# Controller_Mainboard.net
KiCad netlist of a schematic drawn in Altium Designer
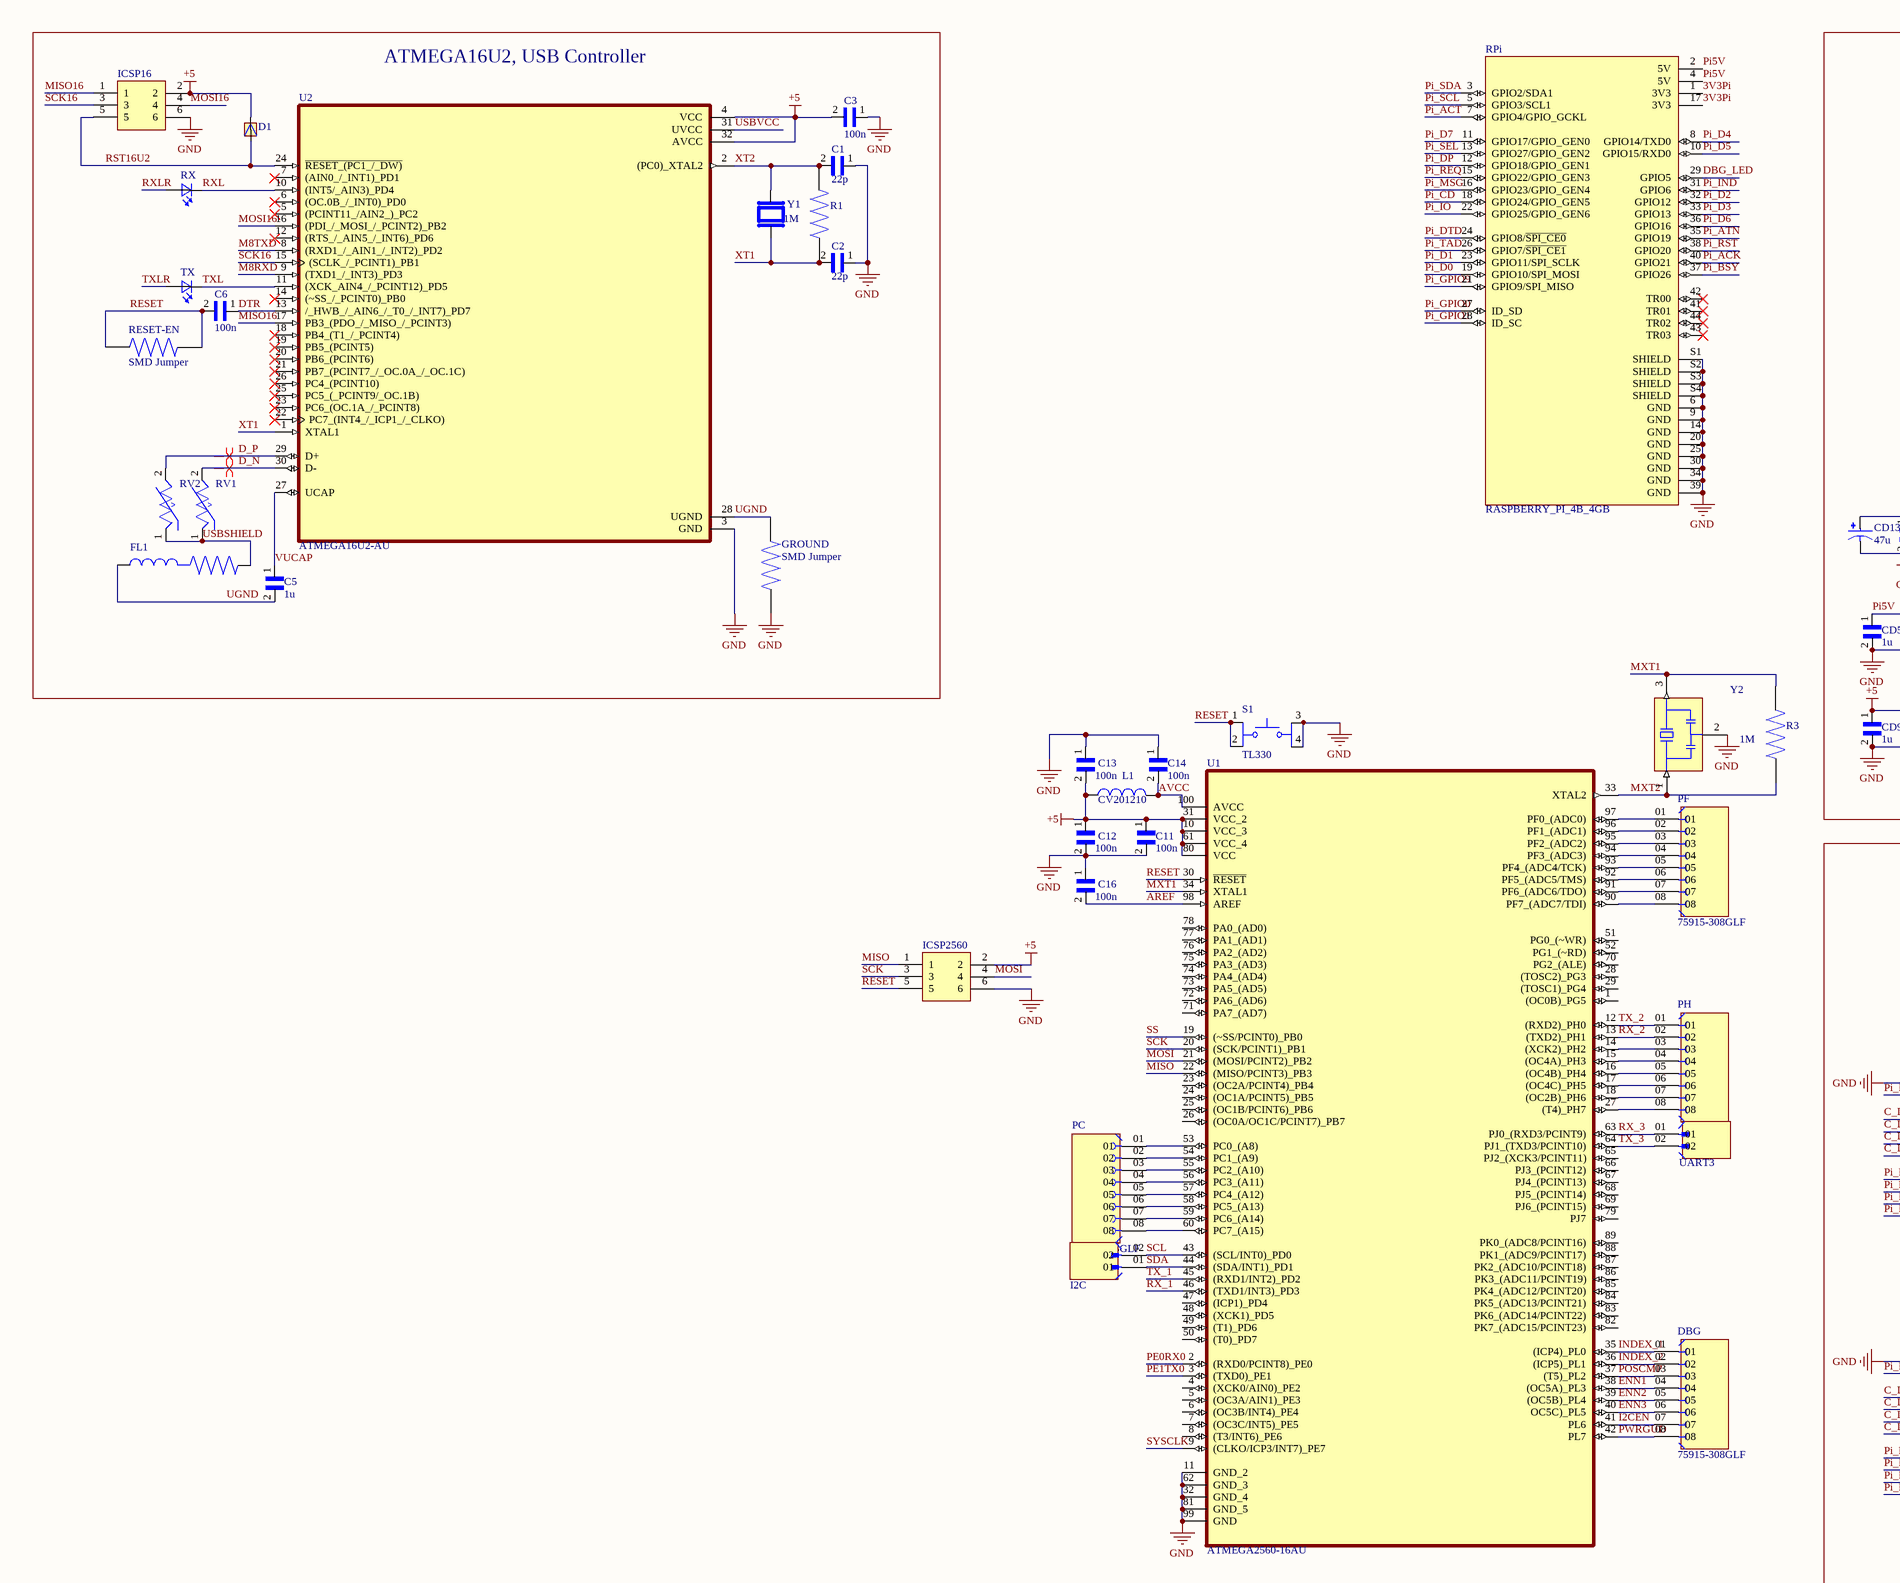
[diagram p0: Controller Mainboard.SchDoc, top left]
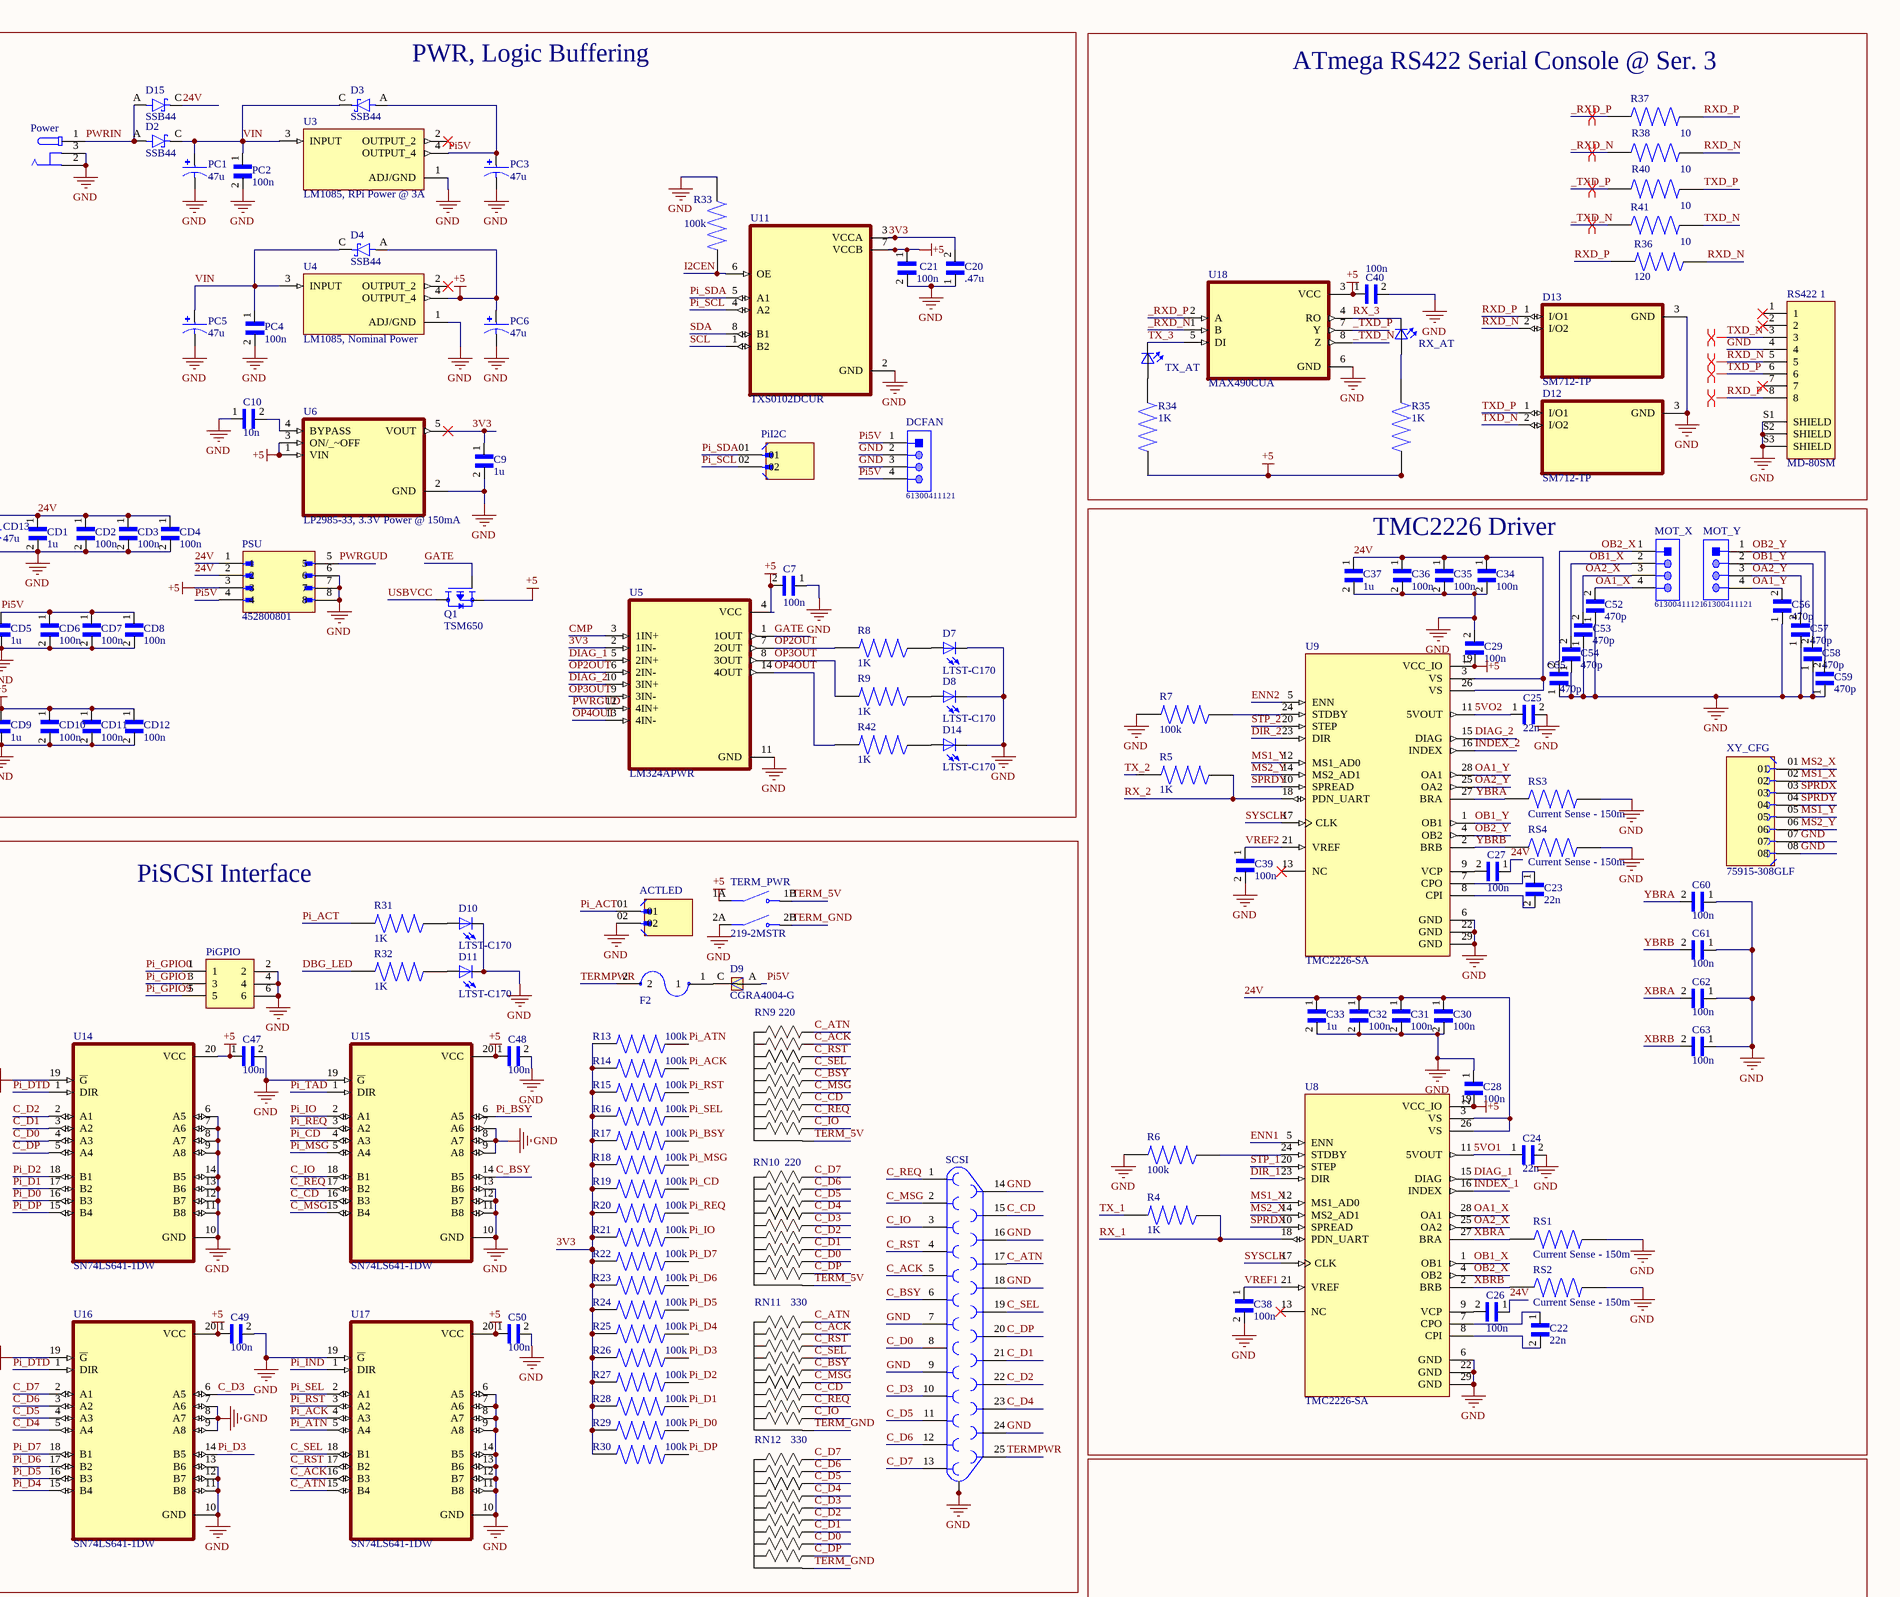
[diagram p1: Controller Mainboard.SchDoc, top right]
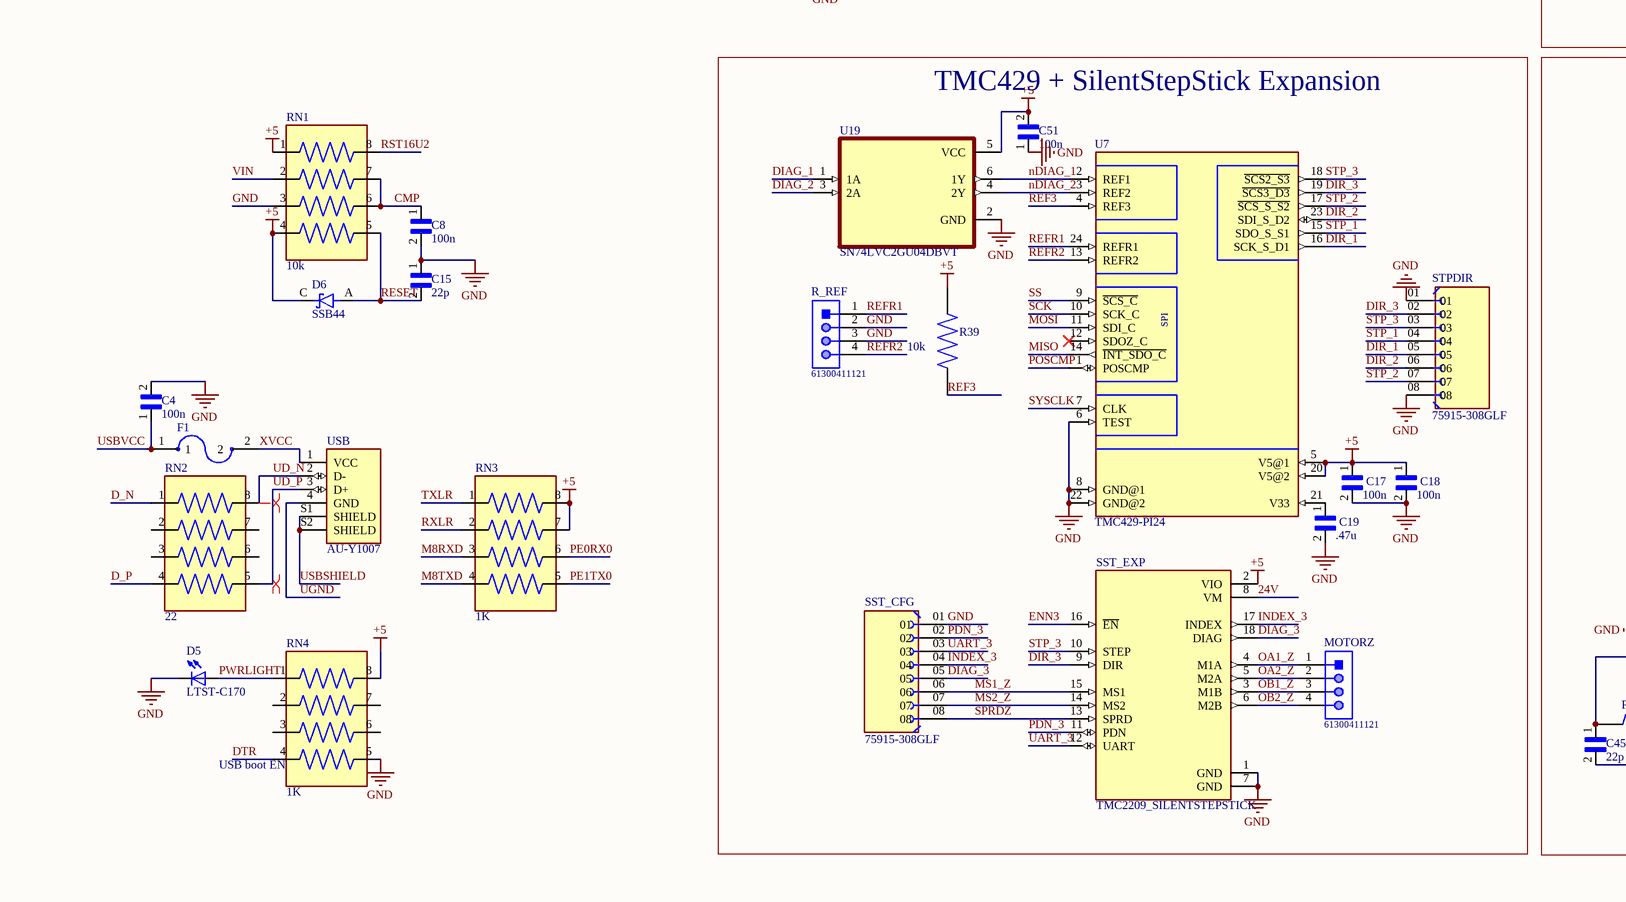
[diagram p2: Controller Mainboard.SchDoc, bottom left]
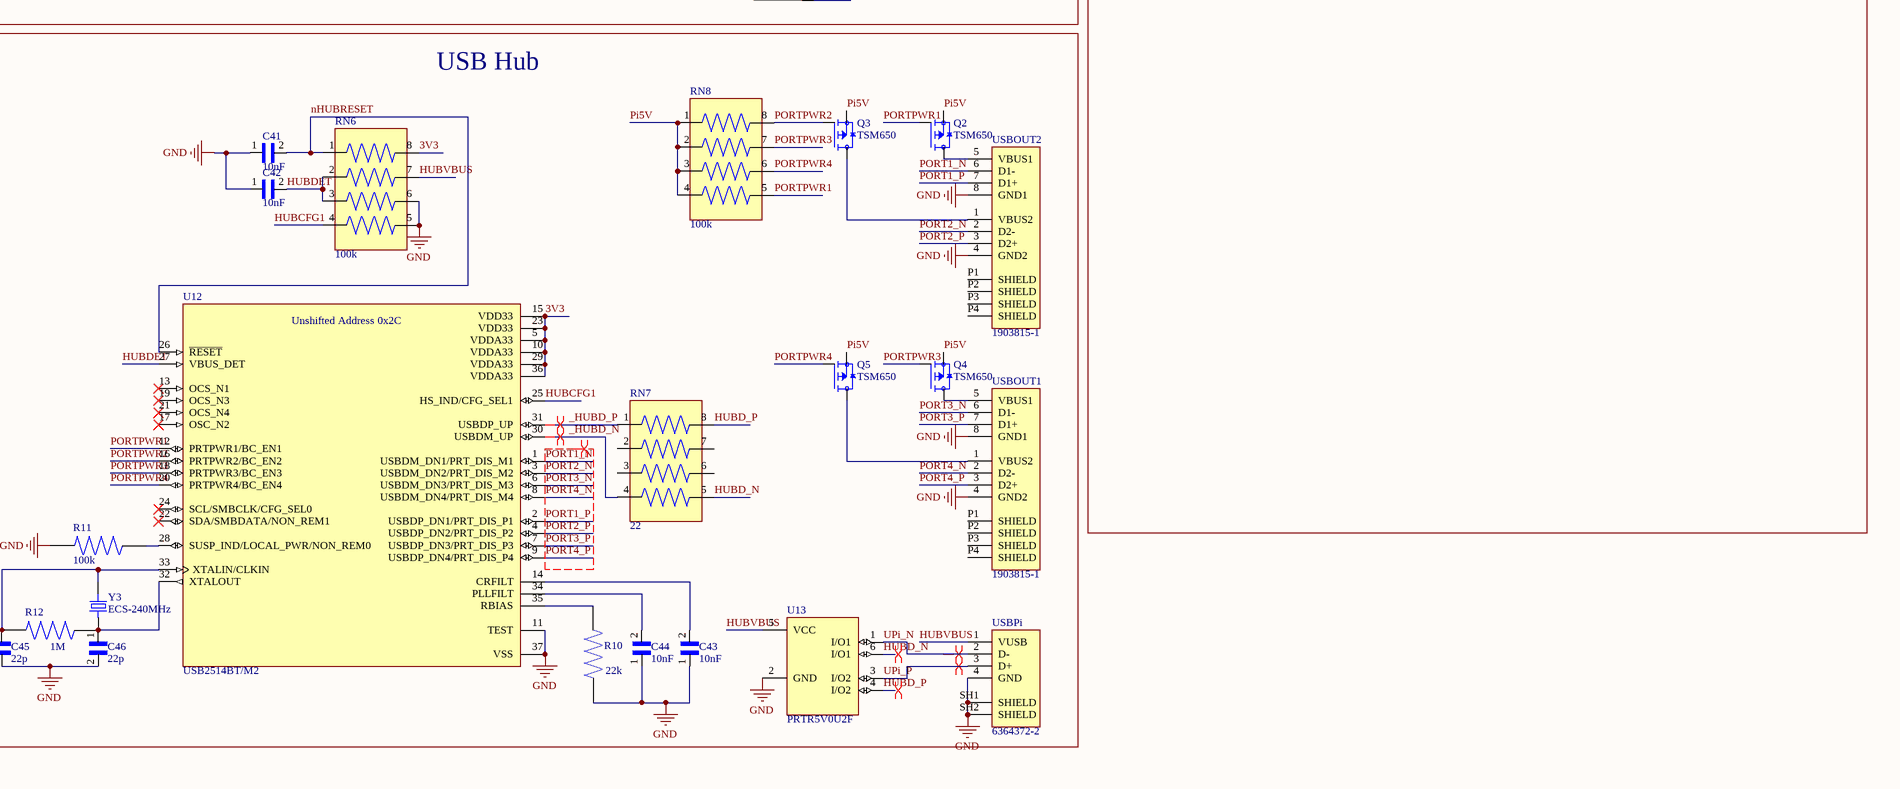
[diagram p3: Controller Mainboard.SchDoc, bottom right]

(export (version "E")
  (design (tool "Eeschema 10.0.6"))
  (components
    (comp (ref "ACTLED")
      (value "77311-118-02LF")
      (footprint "AMPHENOL_77311-118-02LF")
      (fields (field (name "MF") "{'manufacturer': u'Amphenol ICC'}"))
      (libsource (lib "Stepper_Controller") (part "77311-118-02LF"))
    )
    (comp (ref "C1")
      (value "22p")
      (footprint "CAPC1608X90")
      (description "Cap Ceramic 0.0022uF 4V X7R 10% SMD 0603 125Â°C T/R")
      (fields (field (name "MP") "LD034C222KAB2A") (field (name "MF") "{'manufacturer': u'AVX'}"))
      (libsource (lib "") (part "LD034C222KAB2A_3"))
    )
    (comp (ref "C2")
      (value "22p")
      (footprint "CAPC1608X90")
      (description "Cap Ceramic 0.0022uF 4V X7R 10% SMD 0603 125Â°C T/R")
      (fields (field (name "MP") "LD034C222KAB2A") (field (name "MF") "{'manufacturer': u'AVX'}"))
      (libsource (lib "") (part "LD034C222KAB2A_3"))
    )
    (comp (ref "C3")
      (value "100n")
      (footprint "CAPC1608X90")
      (description "Cap Ceramic 0.0022uF 4V X7R 10% SMD 0603 125Â°C T/R")
      (fields (field (name "MP") "LD034C222KAB2A") (field (name "MF") "{'manufacturer': u'AVX'}"))
      (libsource (lib "") (part "LD034C222KAB2A_3"))
    )
    (comp (ref "C4")
      (value "100n")
      (footprint "CAPC1608X90")
      (description "Cap Ceramic 0.0022uF 4V X7R 10% SMD 0603 125Â°C T/R")
      (fields (field (name "MP") "LD034C222KAB2A") (field (name "MF") "{'manufacturer': u'AVX'}"))
      (libsource (lib "") (part "LD034C222KAB2A_2"))
    )
    (comp (ref "C5")
      (value "1u")
      (footprint "CAPC1608X90")
      (description "Cap Ceramic 0.0022uF 4V X7R 10% SMD 0603 125Â°C T/R")
      (fields (field (name "MP") "LD034C222KAB2A") (field (name "MF") "{'manufacturer': u'AVX'}"))
      (libsource (lib "Stepper_Controller") (part "LD034C222KAB2A"))
    )
    (comp (ref "C6")
      (value "100n")
      (footprint "CAPC1608X90")
      (description "Cap Ceramic 0.0022uF 4V X7R 10% SMD 0603 125Â°C T/R")
      (fields (field (name "MP") "LD034C222KAB2A") (field (name "MF") "{'manufacturer': u'AVX'}"))
      (libsource (lib "") (part "LD034C222KAB2A_3"))
    )
    (comp (ref "C7")
      (value "100n")
      (footprint "CAPC1608X90")
      (description "Cap Ceramic 0.0022uF 4V X7R 10% SMD 0603 125Â°C T/R")
      (fields (field (name "MP") "LD034C222KAB2A") (field (name "MF") "{'manufacturer': u'AVX'}"))
      (libsource (lib "") (part "LD034C222KAB2A_3"))
    )
    (comp (ref "C8")
      (value "100n")
      (footprint "CAPC1608X90")
      (description "Cap Ceramic 0.0022uF 4V X7R 10% SMD 0603 125Â°C T/R")
      (fields (field (name "MP") "LD034C222KAB2A") (field (name "MF") "{'manufacturer': u'AVX'}"))
      (libsource (lib "Stepper_Controller") (part "LD034C222KAB2A"))
    )
    (comp (ref "C9")
      (value "1u")
      (footprint "CAPC1608X90")
      (description "Cap Ceramic 0.0022uF 4V X7R 10% SMD 0603 125Â°C T/R")
      (fields (field (name "MP") "LD034C222KAB2A") (field (name "MF") "{'manufacturer': u'AVX'}"))
      (libsource (lib "Stepper_Controller") (part "LD034C222KAB2A"))
    )
    (comp (ref "C10")
      (value "10n")
      (footprint "CAPC1608X90")
      (description "Cap Ceramic 0.0022uF 4V X7R 10% SMD 0603 125Â°C T/R")
      (fields (field (name "MP") "LD034C222KAB2A") (field (name "MF") "{'manufacturer': u'AVX'}"))
      (libsource (lib "") (part "LD034C222KAB2A_1"))
    )
    (comp (ref "C11")
      (value "100n")
      (footprint "CAPC1608X90")
      (description "Cap Ceramic 0.0022uF 4V X7R 10% SMD 0603 125Â°C T/R")
      (fields (field (name "MP") "LD034C222KAB2A") (field (name "MF") "{'manufacturer': u'AVX'}"))
      (libsource (lib "Stepper_Controller") (part "LD034C222KAB2A"))
    )
    (comp (ref "C12")
      (value "100n")
      (footprint "CAPC1608X90")
      (description "Cap Ceramic 0.0022uF 4V X7R 10% SMD 0603 125Â°C T/R")
      (fields (field (name "MP") "LD034C222KAB2A") (field (name "MF") "{'manufacturer': u'AVX'}"))
      (libsource (lib "Stepper_Controller") (part "LD034C222KAB2A"))
    )
    (comp (ref "C13")
      (value "100n")
      (footprint "CAPC1608X90")
      (description "Cap Ceramic 0.0022uF 4V X7R 10% SMD 0603 125Â°C T/R")
      (fields (field (name "MP") "LD034C222KAB2A") (field (name "MF") "{'manufacturer': u'AVX'}"))
      (libsource (lib "Stepper_Controller") (part "LD034C222KAB2A"))
    )
    (comp (ref "C14")
      (value "100n")
      (footprint "CAPC1608X90")
      (description "Cap Ceramic 0.0022uF 4V X7R 10% SMD 0603 125Â°C T/R")
      (fields (field (name "MP") "LD034C222KAB2A") (field (name "MF") "{'manufacturer': u'AVX'}"))
      (libsource (lib "Stepper_Controller") (part "LD034C222KAB2A"))
    )
    (comp (ref "C15")
      (value "22p")
      (footprint "CAPC1608X90")
      (description "Cap Ceramic 0.0022uF 4V X7R 10% SMD 0603 125Â°C T/R")
      (fields (field (name "MP") "LD034C222KAB2A") (field (name "MF") "{'manufacturer': u'AVX'}"))
      (libsource (lib "Stepper_Controller") (part "LD034C222KAB2A"))
    )
    (comp (ref "C16")
      (value "100n")
      (footprint "CAPC1608X90")
      (description "Cap Ceramic 0.0022uF 4V X7R 10% SMD 0603 125Â°C T/R")
      (fields (field (name "MP") "LD034C222KAB2A") (field (name "MF") "{'manufacturer': u'AVX'}"))
      (libsource (lib "Stepper_Controller") (part "LD034C222KAB2A"))
    )
    (comp (ref "C17")
      (value "100n")
      (footprint "CAPC1608X90")
      (description "Cap Ceramic 0.0022uF 4V X7R 10% SMD 0603 125Â°C T/R")
      (fields (field (name "MP") "LD034C222KAB2A") (field (name "MF") "{'manufacturer': u'AVX'}"))
      (libsource (lib "Stepper_Controller") (part "LD034C222KAB2A"))
    )
    (comp (ref "C18")
      (value "100n")
      (footprint "CAPC1608X90")
      (description "Cap Ceramic 0.0022uF 4V X7R 10% SMD 0603 125Â°C T/R")
      (fields (field (name "MP") "LD034C222KAB2A") (field (name "MF") "{'manufacturer': u'AVX'}"))
      (libsource (lib "Stepper_Controller") (part "LD034C222KAB2A"))
    )
    (comp (ref "C19")
      (value ".47u")
      (footprint "CAPC1608X90")
      (description "Cap Ceramic 0.0022uF 4V X7R 10% SMD 0603 125Â°C T/R")
      (fields (field (name "MP") "LD034C222KAB2A") (field (name "MF") "{'manufacturer': u'AVX'}"))
      (libsource (lib "Stepper_Controller") (part "LD034C222KAB2A"))
    )
    (comp (ref "C20")
      (value ".47u")
      (footprint "CAPC1608X90")
      (description "Cap Ceramic 0.0022uF 4V X7R 10% SMD 0603 125Â°C T/R")
      (fields (field (name "MP") "LD034C222KAB2A") (field (name "MF") "{'manufacturer': u'AVX'}"))
      (libsource (lib "") (part "LD034C222KAB2A_2"))
    )
    (comp (ref "C21")
      (value "100n")
      (footprint "CAPC1608X90")
      (description "Cap Ceramic 0.0022uF 4V X7R 10% SMD 0603 125Â°C T/R")
      (fields (field (name "MP") "LD034C222KAB2A") (field (name "MF") "{'manufacturer': u'AVX'}"))
      (libsource (lib "Stepper_Controller") (part "LD034C222KAB2A"))
    )
    (comp (ref "C22")
      (value "22n")
      (footprint "CAPC1608X90")
      (description "Cap Ceramic 0.0022uF 4V X7R 10% SMD 0603 125Â°C T/R")
      (fields (field (name "MP") "LD034C222KAB2A") (field (name "MF") "{'manufacturer': u'AVX'}"))
      (libsource (lib "Stepper_Controller") (part "LD034C222KAB2A"))
    )
    (comp (ref "C23")
      (value "22n")
      (footprint "CAPC1608X90")
      (description "Cap Ceramic 0.0022uF 4V X7R 10% SMD 0603 125Â°C T/R")
      (fields (field (name "MP") "LD034C222KAB2A") (field (name "MF") "{'manufacturer': u'AVX'}"))
      (libsource (lib "Stepper_Controller") (part "LD034C222KAB2A"))
    )
    (comp (ref "C24")
      (value "22n")
      (footprint "CAPC1608X90")
      (description "Cap Ceramic 0.0022uF 4V X7R 10% SMD 0603 125Â°C T/R")
      (fields (field (name "MP") "LD034C222KAB2A") (field (name "MF") "{'manufacturer': u'AVX'}"))
      (libsource (lib "") (part "LD034C222KAB2A_1"))
    )
    (comp (ref "C25")
      (value "22n")
      (footprint "CAPC1608X90")
      (description "Cap Ceramic 0.0022uF 4V X7R 10% SMD 0603 125Â°C T/R")
      (fields (field (name "MP") "LD034C222KAB2A") (field (name "MF") "{'manufacturer': u'AVX'}"))
      (libsource (lib "") (part "LD034C222KAB2A_1"))
    )
    (comp (ref "C26")
      (value "100n")
      (footprint "CAPC1608X90")
      (description "Cap Ceramic 0.0022uF 4V X7R 10% SMD 0603 125Â°C T/R")
      (fields (field (name "MP") "LD034C222KAB2A") (field (name "MF") "{'manufacturer': u'AVX'}"))
      (libsource (lib "") (part "LD034C222KAB2A_3"))
    )
    (comp (ref "C27")
      (value "100n")
      (footprint "CAPC1608X90")
      (description "Cap Ceramic 0.0022uF 4V X7R 10% SMD 0603 125Â°C T/R")
      (fields (field (name "MP") "LD034C222KAB2A") (field (name "MF") "{'manufacturer': u'AVX'}"))
      (libsource (lib "") (part "LD034C222KAB2A_3"))
    )
    (comp (ref "C28")
      (value "100n")
      (footprint "CAPC1608X90")
      (description "Cap Ceramic 0.0022uF 4V X7R 10% SMD 0603 125Â°C T/R")
      (fields (field (name "MP") "LD034C222KAB2A") (field (name "MF") "{'manufacturer': u'AVX'}"))
      (libsource (lib "Stepper_Controller") (part "LD034C222KAB2A"))
    )
    (comp (ref "C29")
      (value "100n")
      (footprint "CAPC1608X90")
      (description "Cap Ceramic 0.0022uF 4V X7R 10% SMD 0603 125Â°C T/R")
      (fields (field (name "MP") "LD034C222KAB2A") (field (name "MF") "{'manufacturer': u'AVX'}"))
      (libsource (lib "") (part "LD034C222KAB2A_2"))
    )
    (comp (ref "C30")
      (value "100n")
      (footprint "CAPC1608X90")
      (description "Cap Ceramic 0.0022uF 4V X7R 10% SMD 0603 125Â°C T/R")
      (fields (field (name "MP") "LD034C222KAB2A") (field (name "MF") "{'manufacturer': u'AVX'}"))
      (libsource (lib "Stepper_Controller") (part "LD034C222KAB2A"))
    )
    (comp (ref "C31")
      (value "100n")
      (footprint "CAPC1608X90")
      (description "Cap Ceramic 0.0022uF 4V X7R 10% SMD 0603 125Â°C T/R")
      (fields (field (name "MP") "LD034C222KAB2A") (field (name "MF") "{'manufacturer': u'AVX'}"))
      (libsource (lib "Stepper_Controller") (part "LD034C222KAB2A"))
    )
    (comp (ref "C32")
      (value "100n")
      (footprint "CAPC1608X90")
      (description "Cap Ceramic 0.0022uF 4V X7R 10% SMD 0603 125Â°C T/R")
      (fields (field (name "MP") "LD034C222KAB2A") (field (name "MF") "{'manufacturer': u'AVX'}"))
      (libsource (lib "Stepper_Controller") (part "LD034C222KAB2A"))
    )
    (comp (ref "C33")
      (value "1u")
      (footprint "CAPC1608X90")
      (description "Cap Ceramic 0.0022uF 4V X7R 10% SMD 0603 125Â°C T/R")
      (fields (field (name "MP") "LD034C222KAB2A") (field (name "MF") "{'manufacturer': u'AVX'}"))
      (libsource (lib "Stepper_Controller") (part "LD034C222KAB2A"))
    )
    (comp (ref "C34")
      (value "100n")
      (footprint "CAPC1608X90")
      (description "Cap Ceramic 0.0022uF 4V X7R 10% SMD 0603 125Â°C T/R")
      (fields (field (name "MP") "LD034C222KAB2A") (field (name "MF") "{'manufacturer': u'AVX'}"))
      (libsource (lib "Stepper_Controller") (part "LD034C222KAB2A"))
    )
    (comp (ref "C35")
      (value "100n")
      (footprint "CAPC1608X90")
      (description "Cap Ceramic 0.0022uF 4V X7R 10% SMD 0603 125Â°C T/R")
      (fields (field (name "MP") "LD034C222KAB2A") (field (name "MF") "{'manufacturer': u'AVX'}"))
      (libsource (lib "Stepper_Controller") (part "LD034C222KAB2A"))
    )
    (comp (ref "C36")
      (value "100n")
      (footprint "CAPC1608X90")
      (description "Cap Ceramic 0.0022uF 4V X7R 10% SMD 0603 125Â°C T/R")
      (fields (field (name "MP") "LD034C222KAB2A") (field (name "MF") "{'manufacturer': u'AVX'}"))
      (libsource (lib "Stepper_Controller") (part "LD034C222KAB2A"))
    )
    (comp (ref "C37")
      (value "1u")
      (footprint "CAPC1608X90")
      (description "Cap Ceramic 0.0022uF 4V X7R 10% SMD 0603 125Â°C T/R")
      (fields (field (name "MP") "LD034C222KAB2A") (field (name "MF") "{'manufacturer': u'AVX'}"))
      (libsource (lib "Stepper_Controller") (part "LD034C222KAB2A"))
    )
    (comp (ref "C38")
      (value "100n")
      (footprint "CAPC1608X90")
      (description "Cap Ceramic 0.0022uF 4V X7R 10% SMD 0603 125Â°C T/R")
      (fields (field (name "MP") "LD034C222KAB2A") (field (name "MF") "{'manufacturer': u'AVX'}"))
      (libsource (lib "Stepper_Controller") (part "LD034C222KAB2A"))
    )
    (comp (ref "C39")
      (value "100n")
      (footprint "CAPC1608X90")
      (description "Cap Ceramic 0.0022uF 4V X7R 10% SMD 0603 125Â°C T/R")
      (fields (field (name "MP") "LD034C222KAB2A") (field (name "MF") "{'manufacturer': u'AVX'}"))
      (libsource (lib "Stepper_Controller") (part "LD034C222KAB2A"))
    )
    (comp (ref "C40")
      (value "100n")
      (footprint "CAPC1608X90")
      (description "Cap Ceramic 0.0022uF 4V X7R 10% SMD 0603 125Â°C T/R")
      (fields (field (name "MP") "LD034C222KAB2A") (field (name "MF") "{'manufacturer': u'AVX'}"))
      (libsource (lib "") (part "LD034C222KAB2A_1"))
    )
    (comp (ref "C41")
      (value "10nF")
      (footprint "CAPC1608X90")
      (description "Cap Ceramic 0.0022uF 4V X7R 10% SMD 0603 125Â°C T/R")
      (fields (field (name "MP") "LD034C222KAB2A") (field (name "MF") "{'manufacturer': u'AVX'}"))
      (libsource (lib "") (part "LD034C222KAB2A_1"))
    )
    (comp (ref "C42")
      (value "10nF")
      (footprint "CAPC1608X90")
      (description "Cap Ceramic 0.0022uF 4V X7R 10% SMD 0603 125Â°C T/R")
      (fields (field (name "MP") "LD034C222KAB2A") (field (name "MF") "{'manufacturer': u'AVX'}"))
      (libsource (lib "") (part "LD034C222KAB2A_1"))
    )
    (comp (ref "C43")
      (value "10nF")
      (footprint "CAPC1608X90")
      (description "Cap Ceramic 0.0022uF 4V X7R 10% SMD 0603 125Â°C T/R")
      (fields (field (name "MP") "LD034C222KAB2A") (field (name "MF") "{'manufacturer': u'AVX'}"))
      (libsource (lib "") (part "LD034C222KAB2A_2"))
    )
    (comp (ref "C44")
      (value "10nF")
      (footprint "CAPC1608X90")
      (description "Cap Ceramic 0.0022uF 4V X7R 10% SMD 0603 125Â°C T/R")
      (fields (field (name "MP") "LD034C222KAB2A") (field (name "MF") "{'manufacturer': u'AVX'}"))
      (libsource (lib "") (part "LD034C222KAB2A_2"))
    )
    (comp (ref "C45")
      (value "22p")
      (footprint "CAPC1608X90")
      (description "Cap Ceramic 0.0022uF 4V X7R 10% SMD 0603 125Â°C T/R")
      (fields (field (name "MP") "LD034C222KAB2A") (field (name "MF") "{'manufacturer': u'AVX'}"))
      (libsource (lib "Stepper_Controller") (part "LD034C222KAB2A"))
    )
    (comp (ref "C46")
      (value "22p")
      (footprint "CAPC1608X90")
      (description "Cap Ceramic 0.0022uF 4V X7R 10% SMD 0603 125Â°C T/R")
      (fields (field (name "MP") "LD034C222KAB2A") (field (name "MF") "{'manufacturer': u'AVX'}"))
      (libsource (lib "Stepper_Controller") (part "LD034C222KAB2A"))
    )
    (comp (ref "C47")
      (value "100n")
      (footprint "CAPC1608X90")
      (description "Cap Ceramic 0.0022uF 4V X7R 10% SMD 0603 125Â°C T/R")
      (fields (field (name "MP") "LD034C222KAB2A") (field (name "MF") "{'manufacturer': u'AVX'}"))
      (libsource (lib "") (part "LD034C222KAB2A_1"))
    )
    (comp (ref "C48")
      (value "100n")
      (footprint "CAPC1608X90")
      (description "Cap Ceramic 0.0022uF 4V X7R 10% SMD 0603 125Â°C T/R")
      (fields (field (name "MP") "LD034C222KAB2A") (field (name "MF") "{'manufacturer': u'AVX'}"))
      (libsource (lib "") (part "LD034C222KAB2A_1"))
    )
    (comp (ref "C49")
      (value "100n")
      (footprint "CAPC1608X90")
      (description "Cap Ceramic 0.0022uF 4V X7R 10% SMD 0603 125Â°C T/R")
      (fields (field (name "MP") "LD034C222KAB2A") (field (name "MF") "{'manufacturer': u'AVX'}"))
      (libsource (lib "") (part "LD034C222KAB2A_1"))
    )
    (comp (ref "C50")
      (value "100n")
      (footprint "CAPC1608X90")
      (description "Cap Ceramic 0.0022uF 4V X7R 10% SMD 0603 125Â°C T/R")
      (fields (field (name "MP") "LD034C222KAB2A") (field (name "MF") "{'manufacturer': u'AVX'}"))
      (libsource (lib "") (part "LD034C222KAB2A_1"))
    )
    (comp (ref "C51")
      (value "100n")
      (footprint "CAPC1608X90")
      (description "Cap Ceramic 0.0022uF 4V X7R 10% SMD 0603 125Â°C T/R")
      (fields (field (name "MP") "LD034C222KAB2A") (field (name "MF") "{'manufacturer': u'AVX'}"))
      (libsource (lib "") (part "LD034C222KAB2A_2"))
    )
    (comp (ref "C52")
      (value "470p")
      (footprint "CAPC1608X90")
      (description "Cap Ceramic 0.0022uF 4V X7R 10% SMD 0603 125Â°C T/R")
      (fields (field (name "MP") "LD034C222KAB2A") (field (name "MF") "{'manufacturer': u'AVX'}"))
      (libsource (lib "") (part "LD034C222KAB2A_2"))
    )
    (comp (ref "C53")
      (value "470p")
      (footprint "CAPC1608X90")
      (description "Cap Ceramic 0.0022uF 4V X7R 10% SMD 0603 125Â°C T/R")
      (fields (field (name "MP") "LD034C222KAB2A") (field (name "MF") "{'manufacturer': u'AVX'}"))
      (libsource (lib "") (part "LD034C222KAB2A_2"))
    )
    (comp (ref "C54")
      (value "470p")
      (footprint "CAPC1608X90")
      (description "Cap Ceramic 0.0022uF 4V X7R 10% SMD 0603 125Â°C T/R")
      (fields (field (name "MP") "LD034C222KAB2A") (field (name "MF") "{'manufacturer': u'AVX'}"))
      (libsource (lib "") (part "LD034C222KAB2A_2"))
    )
    (comp (ref "C55")
      (value "470p")
      (footprint "CAPC1608X90")
      (description "Cap Ceramic 0.0022uF 4V X7R 10% SMD 0603 125Â°C T/R")
      (fields (field (name "MP") "LD034C222KAB2A") (field (name "MF") "{'manufacturer': u'AVX'}"))
      (libsource (lib "") (part "LD034C222KAB2A_2"))
    )
    (comp (ref "C56")
      (value "470p")
      (footprint "CAPC1608X90")
      (description "Cap Ceramic 0.0022uF 4V X7R 10% SMD 0603 125Â°C T/R")
      (fields (field (name "MP") "LD034C222KAB2A") (field (name "MF") "{'manufacturer': u'AVX'}"))
      (libsource (lib "") (part "LD034C222KAB2A_2"))
    )
    (comp (ref "C57")
      (value "470p")
      (footprint "CAPC1608X90")
      (description "Cap Ceramic 0.0022uF 4V X7R 10% SMD 0603 125Â°C T/R")
      (fields (field (name "MP") "LD034C222KAB2A") (field (name "MF") "{'manufacturer': u'AVX'}"))
      (libsource (lib "") (part "LD034C222KAB2A_2"))
    )
    (comp (ref "C58")
      (value "470p")
      (footprint "CAPC1608X90")
      (description "Cap Ceramic 0.0022uF 4V X7R 10% SMD 0603 125Â°C T/R")
      (fields (field (name "MP") "LD034C222KAB2A") (field (name "MF") "{'manufacturer': u'AVX'}"))
      (libsource (lib "") (part "LD034C222KAB2A_2"))
    )
    (comp (ref "C59")
      (value "470p")
      (footprint "CAPC1608X90")
      (description "Cap Ceramic 0.0022uF 4V X7R 10% SMD 0603 125Â°C T/R")
      (fields (field (name "MP") "LD034C222KAB2A") (field (name "MF") "{'manufacturer': u'AVX'}"))
      (libsource (lib "") (part "LD034C222KAB2A_2"))
    )
    (comp (ref "C60")
      (value "100n")
      (footprint "CAPC1608X90")
      (description "Cap Ceramic 0.0022uF 4V X7R 10% SMD 0603 125Â°C T/R")
      (fields (field (name "MP") "LD034C222KAB2A") (field (name "MF") "{'manufacturer': u'AVX'}"))
      (libsource (lib "") (part "LD034C222KAB2A_3"))
    )
    (comp (ref "C61")
      (value "100n")
      (footprint "CAPC1608X90")
      (description "Cap Ceramic 0.0022uF 4V X7R 10% SMD 0603 125Â°C T/R")
      (fields (field (name "MP") "LD034C222KAB2A") (field (name "MF") "{'manufacturer': u'AVX'}"))
      (libsource (lib "") (part "LD034C222KAB2A_3"))
    )
    (comp (ref "C62")
      (value "100n")
      (footprint "CAPC1608X90")
      (description "Cap Ceramic 0.0022uF 4V X7R 10% SMD 0603 125Â°C T/R")
      (fields (field (name "MP") "LD034C222KAB2A") (field (name "MF") "{'manufacturer': u'AVX'}"))
      (libsource (lib "") (part "LD034C222KAB2A_3"))
    )
    (comp (ref "C63")
      (value "100n")
      (footprint "CAPC1608X90")
      (description "Cap Ceramic 0.0022uF 4V X7R 10% SMD 0603 125Â°C T/R")
      (fields (field (name "MP") "LD034C222KAB2A") (field (name "MF") "{'manufacturer': u'AVX'}"))
      (libsource (lib "") (part "LD034C222KAB2A_3"))
    )
    (comp (ref "CD1")
      (value "1u")
      (footprint "CAPC1608X90")
      (description "Cap Ceramic 0.0022uF 4V X7R 10% SMD 0603 125Â°C T/R")
      (fields (field (name "MP") "LD034C222KAB2A") (field (name "MF") "{'manufacturer': u'AVX'}"))
      (libsource (lib "Stepper_Controller") (part "LD034C222KAB2A"))
    )
    (comp (ref "CD2")
      (value "100n")
      (footprint "CAPC1608X90")
      (description "Cap Ceramic 0.0022uF 4V X7R 10% SMD 0603 125Â°C T/R")
      (fields (field (name "MP") "LD034C222KAB2A") (field (name "MF") "{'manufacturer': u'AVX'}"))
      (libsource (lib "Stepper_Controller") (part "LD034C222KAB2A"))
    )
    (comp (ref "CD3")
      (value "100n")
      (footprint "CAPC1608X90")
      (description "Cap Ceramic 0.0022uF 4V X7R 10% SMD 0603 125Â°C T/R")
      (fields (field (name "MP") "LD034C222KAB2A") (field (name "MF") "{'manufacturer': u'AVX'}"))
      (libsource (lib "Stepper_Controller") (part "LD034C222KAB2A"))
    )
    (comp (ref "CD4")
      (value "100n")
      (footprint "CAPC1608X90")
      (description "Cap Ceramic 0.0022uF 4V X7R 10% SMD 0603 125Â°C T/R")
      (fields (field (name "MP") "LD034C222KAB2A") (field (name "MF") "{'manufacturer': u'AVX'}"))
      (libsource (lib "Stepper_Controller") (part "LD034C222KAB2A"))
    )
    (comp (ref "CD5")
      (value "1u")
      (footprint "CAPC1608X90")
      (description "Cap Ceramic 0.0022uF 4V X7R 10% SMD 0603 125Â°C T/R")
      (fields (field (name "MP") "LD034C222KAB2A") (field (name "MF") "{'manufacturer': u'AVX'}"))
      (libsource (lib "Stepper_Controller") (part "LD034C222KAB2A"))
    )
    (comp (ref "CD6")
      (value "100n")
      (footprint "CAPC1608X90")
      (description "Cap Ceramic 0.0022uF 4V X7R 10% SMD 0603 125Â°C T/R")
      (fields (field (name "MP") "LD034C222KAB2A") (field (name "MF") "{'manufacturer': u'AVX'}"))
      (libsource (lib "Stepper_Controller") (part "LD034C222KAB2A"))
    )
    (comp (ref "CD7")
      (value "100n")
      (footprint "CAPC1608X90")
      (description "Cap Ceramic 0.0022uF 4V X7R 10% SMD 0603 125Â°C T/R")
      (fields (field (name "MP") "LD034C222KAB2A") (field (name "MF") "{'manufacturer': u'AVX'}"))
      (libsource (lib "Stepper_Controller") (part "LD034C222KAB2A"))
    )
    (comp (ref "CD8")
      (value "100n")
      (footprint "CAPC1608X90")
      (description "Cap Ceramic 0.0022uF 4V X7R 10% SMD 0603 125Â°C T/R")
      (fields (field (name "MP") "LD034C222KAB2A") (field (name "MF") "{'manufacturer': u'AVX'}"))
      (libsource (lib "Stepper_Controller") (part "LD034C222KAB2A"))
    )
    (comp (ref "CD9")
      (value "1u")
      (footprint "CAPC1608X90")
      (description "Cap Ceramic 0.0022uF 4V X7R 10% SMD 0603 125Â°C T/R")
      (fields (field (name "MP") "LD034C222KAB2A") (field (name "MF") "{'manufacturer': u'AVX'}"))
      (libsource (lib "Stepper_Controller") (part "LD034C222KAB2A"))
    )
    (comp (ref "CD10")
      (value "100n")
      (footprint "CAPC1608X90")
      (description "Cap Ceramic 0.0022uF 4V X7R 10% SMD 0603 125Â°C T/R")
      (fields (field (name "MP") "LD034C222KAB2A") (field (name "MF") "{'manufacturer': u'AVX'}"))
      (libsource (lib "Stepper_Controller") (part "LD034C222KAB2A"))
    )
    (comp (ref "CD11")
      (value "100n")
      (footprint "CAPC1608X90")
      (description "Cap Ceramic 0.0022uF 4V X7R 10% SMD 0603 125Â°C T/R")
      (fields (field (name "MP") "LD034C222KAB2A") (field (name "MF") "{'manufacturer': u'AVX'}"))
      (libsource (lib "Stepper_Controller") (part "LD034C222KAB2A"))
    )
    (comp (ref "CD12")
      (value "100n")
      (footprint "CAPC1608X90")
      (description "Cap Ceramic 0.0022uF 4V X7R 10% SMD 0603 125Â°C T/R")
      (fields (field (name "MP") "LD034C222KAB2A") (field (name "MF") "{'manufacturer': u'AVX'}"))
      (libsource (lib "Stepper_Controller") (part "LD034C222KAB2A"))
    )
    (comp (ref "CD13")
      (value "47u")
      (footprint "CAP_EEHZA1V470P")
      (fields
        (field (name "MF") "{'manufacturer': u'Panasonic Electronic'}")
        (field (name "MP") "EEHZA1V470P")
      )
      (libsource (lib "Stepper_Controller") (part "EEHZA1V470P"))
    )
    (comp (ref "D1")
      (value "CD1206-S01575")
      (footprint "1206(DIODE)")
      (description "Diode, Io=150mA, Vr=75V")
      (fields (field (name "MF") "{'manufacturer': u'Bourns'}"))
      (libsource (lib "Stepper_Controller") (part "CD1206-S01575"))
    )
    (comp (ref "D2")
      (value "SSB44")
      (footprint "DIOM5336X265N")
      (description "Diode Schottky 40V 2A Surface Mount DO-214AA (SMB)")
      (fields (field (name "MP") "SS24") (field (name "MF") "{'manufacturer': u'ON Semiconductor'}"))
      (libsource (lib "Stepper_Controller") (part "SS24"))
    )
    (comp (ref "D3")
      (value "SSB44")
      (footprint "DIOM5336X265N")
      (description "Diode Schottky 40V 2A Surface Mount DO-214AA (SMB)")
      (fields (field (name "MP") "SS24") (field (name "MF") "{'manufacturer': u'ON Semiconductor'}"))
      (libsource (lib "Stepper_Controller") (part "SS24"))
    )
    (comp (ref "D4")
      (value "SSB44")
      (footprint "DIOM5336X265N")
      (description "Diode Schottky 40V 2A Surface Mount DO-214AA (SMB)")
      (fields (field (name "MP") "SS24") (field (name "MF") "{'manufacturer': u'ON Semiconductor'}"))
      (libsource (lib "Stepper_Controller") (part "SS24"))
    )
    (comp (ref "D5")
      (value "LTST-C170")
      (footprint "DIOC200X125X110")
      (description "Green 2 x 1.25 x 1.1 mm 130Â° Water Clear 35 mcd 2 V Surface Mount LED")
      (fields (field (name "MP") "LTST-C170KGKT") (field (name "MF") "{'manufacturer': u'Lite-On Inc.'}"))
      (libsource (lib "Stepper_Controller") (part "LTST-C170KGKT"))
    )
    (comp (ref "D6")
      (value "SSB44")
      (footprint "DIOM5336X265N")
      (description "Diode Schottky 40V 2A Surface Mount DO-214AA (SMB)")
      (fields (field (name "MP") "SS24") (field (name "MF") "{'manufacturer': u'ON Semiconductor'}"))
      (libsource (lib "Stepper_Controller") (part "SS24"))
    )
    (comp (ref "D7")
      (value "LTST-C170")
      (footprint "DIOC200X125X110")
      (description "Green 2 x 1.25 x 1.1 mm 130Â° Water Clear 35 mcd 2 V Surface Mount LED")
      (fields (field (name "MP") "LTST-C170KGKT") (field (name "MF") "{'manufacturer': u'Lite-On Inc.'}"))
      (libsource (lib "Stepper_Controller") (part "LTST-C170KGKT"))
    )
    (comp (ref "D8")
      (value "LTST-C170")
      (footprint "DIOC200X125X110")
      (description "Green 2 x 1.25 x 1.1 mm 130Â° Water Clear 35 mcd 2 V Surface Mount LED")
      (fields (field (name "MP") "LTST-C170KGKT") (field (name "MF") "{'manufacturer': u'Lite-On Inc.'}"))
      (libsource (lib "Stepper_Controller") (part "LTST-C170KGKT"))
    )
    (comp (ref "D9")
      (value "CGRA4004-G")
      (footprint "DIOM5127X229N")
      (description "Comchip Cgra4004-g / Diode Gen Purpose 400v 1a Sma Comchip")
      (fields (field (name "MF") "{'manufacturer': u'Comchip Technology'}"))
      (libsource (lib "Stepper_Controller") (part "CGRA4004-G"))
    )
    (comp (ref "D10")
      (value "LTST-C170")
      (footprint "DIOC200X125X110")
      (description "Green 2 x 1.25 x 1.1 mm 130Â° Water Clear 35 mcd 2 V Surface Mount LED")
      (fields (field (name "MP") "LTST-C170KGKT") (field (name "MF") "{'manufacturer': u'Lite-On Inc.'}"))
      (libsource (lib "Stepper_Controller") (part "LTST-C170KGKT"))
    )
    (comp (ref "D11")
      (value "LTST-C170")
      (footprint "DIOC200X125X110")
      (description "Green 2 x 1.25 x 1.1 mm 130Â° Water Clear 35 mcd 2 V Surface Mount LED")
      (fields (field (name "MP") "LTST-C170KGKT") (field (name "MF") "{'manufacturer': u'Lite-On Inc.'}"))
      (libsource (lib "Stepper_Controller") (part "LTST-C170KGKT"))
    )
    (comp (ref "D12")
      (value "SM712-TP")
      (footprint "SOT23-3P96_237X112L42X44")
      (fields (field (name "MF") "{'manufacturer': u'Micro Commercial'}"))
      (libsource (lib "Stepper_Controller") (part "SM712-TP"))
    )
    (comp (ref "D13")
      (value "SM712-TP")
      (footprint "SOT23-3P96_237X112L42X44")
      (fields (field (name "MF") "{'manufacturer': u'Micro Commercial'}"))
      (libsource (lib "Stepper_Controller") (part "SM712-TP"))
    )
    (comp (ref "D14")
      (value "LTST-C170")
      (footprint "DIOC200X125X110")
      (description "Green 2 x 1.25 x 1.1 mm 130Â° Water Clear 35 mcd 2 V Surface Mount LED")
      (fields (field (name "MP") "LTST-C170KGKT") (field (name "MF") "{'manufacturer': u'Lite-On Inc.'}"))
      (libsource (lib "Stepper_Controller") (part "LTST-C170KGKT"))
    )
    (comp (ref "D15")
      (value "SSB44")
      (footprint "DIOM5336X265N")
      (description "Diode Schottky 40V 2A Surface Mount DO-214AA (SMB)")
      (fields (field (name "MP") "SS24") (field (name "MF") "{'manufacturer': u'ON Semiconductor'}"))
      (libsource (lib "Stepper_Controller") (part "SS24"))
    )
    (comp (ref "DBG")
      (value "75915-308GLF")
      (footprint "AMPHENOL_75915-308GLF")
      (fields (field (name "MF") "{'manufacturer': u'Amphenol ICC (FCI)'}"))
      (libsource (lib "Stepper_Controller") (part "75915-308GLF"))
    )
    (comp (ref "DCFAN")
      (value "61300411121")
      (footprint "61300411121")
      (description "THT Vertical Pin Header WR-PHD, Pitch 2.54 mm, Single Row, 4 pins")
      (fields (field (name "MANUFACTURER") "Wurth Elektronik") (field (name "PUBLISHER") "WurthElektronik"))
      (libsource (lib "Altium Content Vault") (part "WE-CN-1P-M-R4"))
    )
    (comp (ref "F1")
      (value "MF-MSMF050-2")
      (footprint "FUSM4632X85")
      (description "PTC Resettable Fuse 0.5A(hold) 1A(trip) 15V 100A 0.8W 0.15s 0.15Ohm SMD Solder Pad 1812 T/R")
      (fields (field (name "MF") "{'manufacturer': u'Bourns'}"))
      (libsource (lib "Stepper_Controller") (part "MF-MSMF050-2"))
    )
    (comp (ref "F2")
      (value "MF-MSMF050-2")
      (footprint "FUSM4632X85")
      (description "PTC Resettable Fuse 0.5A(hold) 1A(trip) 15V 100A 0.8W 0.15s 0.15Ohm SMD Solder Pad 1812 T/R")
      (fields (field (name "MF") "{'manufacturer': u'Bourns'}"))
      (libsource (lib "Stepper_Controller") (part "MF-MSMF050-2"))
    )
    (comp (ref "FL1")
      (value "BLM21PG300SN1D")
      (footprint "BEADC2012X105N")
      (description "Ferrite Beads Multi-Layer 30Ohm 100MHz 4A 14mOhm DCR 0805 T/R")
      (fields (field (name "MF") "{'manufacturer': u'Murata'}"))
      (libsource (lib "Stepper_Controller") (part "BLM21PG300SN1D"))
    )
    (comp (ref "GROUND")
      (value "SMD Jumper")
      (footprint "RESC1608X60N")
      (fields (field (name "MF") "{'manufacturer': u'Yageo'}") (field (name "MP") "PA0603-R-070RL"))
      (libsource (lib "Stepper_Controller") (part "PA0603-R-070RL"))
    )
    (comp (ref "I2C")
      (value "77311-118-02LF")
      (footprint "AMPHENOL_77311-118-02LF")
      (fields (field (name "MF") "{'manufacturer': u'Amphenol ICC'}"))
      (libsource (lib "") (part "77311-118-02LF_1"))
    )
    (comp (ref "ICSP16")
      (value "67997-206HLF")
      (footprint "FRAMATOME_67997-206HLF")
      (description "Conn; Rect; UnshroudedHdr; 6Cnts; ThruHole; BergStik; 2.54mmPin-Spng; Vert; DblRow")
      (fields (field (name "MF") "{'manufacturer': u'Amphenol ICC'}"))
      (libsource (lib "Stepper_Controller") (part "67997-206HLF"))
    )
    (comp (ref "ICSP2560")
      (value "67997-206HLF")
      (footprint "FRAMATOME_67997-206HLF")
      (description "Conn; Rect; UnshroudedHdr; 6Cnts; ThruHole; BergStik; 2.54mmPin-Spng; Vert; DblRow")
      (fields (field (name "MF") "{'manufacturer': u'Amphenol ICC'}"))
      (libsource (lib "Stepper_Controller") (part "67997-206HLF"))
    )
    (comp (ref "L1")
      (value "CV201210")
      (footprint "INDC2012X145N")
      (description "Ind Chip Shielded Multi-Layer 10uH 10% 2MHz 45Q-Factor Ferrite 15mA 2.0 x 1.2 mm T/R")
      (fields (field (name "MP") "CV201210-100K") (field (name "MF") "{'manufacturer': u'Bourns'}"))
      (libsource (lib "Stepper_Controller") (part "CV201210-100K"))
    )
    (comp (ref "MOTORZ")
      (value "61300411121")
      (footprint "61300411121")
      (description "THT Vertical Pin Header WR-PHD, Pitch 2.54 mm, Single Row, 4 pins")
      (fields (field (name "MANUFACTURER") "Wurth Elektronik") (field (name "PUBLISHER") "WurthElektronik"))
      (libsource (lib "Altium Content Vault") (part "WE-CN-1P-M-R4"))
    )
    (comp (ref "MOT_X")
      (value "61300411121")
      (footprint "61300411121")
      (description "THT Vertical Pin Header WR-PHD, Pitch 2.54 mm, Single Row, 4 pins")
      (fields (field (name "MANUFACTURER") "Wurth Elektronik") (field (name "PUBLISHER") "WurthElektronik"))
      (libsource (lib "Altium Content Vault") (part "WE-CN-1P-M-R4"))
    )
    (comp (ref "MOT_Y")
      (value "61300411121")
      (footprint "61300411121")
      (description "THT Vertical Pin Header WR-PHD, Pitch 2.54 mm, Single Row, 4 pins")
      (fields (field (name "MANUFACTURER") "Wurth Elektronik") (field (name "PUBLISHER") "WurthElektronik"))
      (libsource (lib "") (part "WE-CN-1P-M-R4_1"))
    )
    (comp (ref "PC")
      (value "75915-308GLF")
      (footprint "AMPHENOL_75915-308GLF")
      (fields (field (name "MF") "{'manufacturer': u'Amphenol ICC (FCI)'}"))
      (libsource (lib "") (part "75915-308GLF_1"))
    )
    (comp (ref "PC1")
      (value "47u")
      (footprint "CAP_EEHZA1V470P")
      (fields
        (field (name "MF") "{'manufacturer': u'Panasonic Electronic'}")
        (field (name "MP") "EEHZA1V470P")
      )
      (libsource (lib "Stepper_Controller") (part "EEHZA1V470P"))
    )
    (comp (ref "PC2")
      (value "100n")
      (footprint "CAPC1608X90")
      (description "Cap Ceramic 0.0022uF 4V X7R 10% SMD 0603 125Â°C T/R")
      (fields (field (name "MP") "LD034C222KAB2A") (field (name "MF") "{'manufacturer': u'AVX'}"))
      (libsource (lib "Stepper_Controller") (part "LD034C222KAB2A"))
    )
    (comp (ref "PC3")
      (value "47u")
      (footprint "CAP_EEHZA1V470P")
      (fields
        (field (name "MF") "{'manufacturer': u'Panasonic Electronic'}")
        (field (name "MP") "EEHZA1V470P")
      )
      (libsource (lib "Stepper_Controller") (part "EEHZA1V470P"))
    )
    (comp (ref "PC4")
      (value "100n")
      (footprint "CAPC1608X90")
      (description "Cap Ceramic 0.0022uF 4V X7R 10% SMD 0603 125Â°C T/R")
      (fields (field (name "MP") "LD034C222KAB2A") (field (name "MF") "{'manufacturer': u'AVX'}"))
      (libsource (lib "Stepper_Controller") (part "LD034C222KAB2A"))
    )
    (comp (ref "PC5")
      (value "47u")
      (footprint "CAP_EEHZA1V470P")
      (fields
        (field (name "MF") "{'manufacturer': u'Panasonic Electronic'}")
        (field (name "MP") "EEHZA1V470P")
      )
      (libsource (lib "Stepper_Controller") (part "EEHZA1V470P"))
    )
    (comp (ref "PC6")
      (value "47u")
      (footprint "CAP_EEHZA1V470P")
      (fields
        (field (name "MF") "{'manufacturer': u'Panasonic Electronic'}")
        (field (name "MP") "EEHZA1V470P")
      )
      (libsource (lib "Stepper_Controller") (part "EEHZA1V470P"))
    )
    (comp (ref "PF")
      (value "75915-308GLF")
      (footprint "AMPHENOL_75915-308GLF")
      (fields (field (name "MF") "{'manufacturer': u'Amphenol ICC (FCI)'}"))
      (libsource (lib "Stepper_Controller") (part "75915-308GLF"))
    )
    (comp (ref "PH")
      (value "75915-308GLF")
      (footprint "AMPHENOL_75915-308GLF")
      (fields (field (name "MF") "{'manufacturer': u'Amphenol ICC (FCI)'}"))
      (libsource (lib "Stepper_Controller") (part "75915-308GLF"))
    )
    (comp (ref "PiGPIO")
      (value "67997-206HLF")
      (footprint "FRAMATOME_67997-206HLF")
      (description "Conn; Rect; UnshroudedHdr; 6Cnts; ThruHole; BergStik; 2.54mmPin-Spng; Vert; DblRow")
      (fields (field (name "MF") "{'manufacturer': u'Amphenol ICC'}"))
      (libsource (lib "Stepper_Controller") (part "67997-206HLF"))
    )
    (comp (ref "PiI2C")
      (value "77311-118-02LF")
      (footprint "AMPHENOL_77311-118-02LF")
      (fields (field (name "MF") "{'manufacturer': u'Amphenol ICC'}"))
      (libsource (lib "") (part "77311-118-02LF_2"))
    )
    (comp (ref "Power")
      (value "EJ508A")
      (footprint "MPD_EJ508A")
      (description "DC JACK - PCB MOUNTING 2.1 ID X 5.5 OD")
      (fields (field (name "MF") "{'manufacturer': u'MPD (Memory Protection Devices)'}"))
      (libsource (lib "Stepper_Controller") (part "EJ508A"))
    )
    (comp (ref "PSU")
      (value "452800801")
      (footprint "MOLEX_452800801")
      (fields (field (name "MF") "{'manufacturer': u'Molex'}"))
      (libsource (lib "Stepper_Controller") (part "452800801"))
    )
    (comp (ref "Q1")
      (value "TSM650")
      (footprint "TRANS_TSM650P02CX_RFG")
      (fields
        (field (name "MF") "{'manufacturer': u'Taiwan Semiconductor Corporation'}")
        (field (name "MP") "TSM650P02CX_RFG")
      )
      (libsource (lib "Stepper_Controller") (part "TSM650P02CX_RFG"))
    )
    (comp (ref "Q2")
      (value "TSM650")
      (footprint "TRANS_TSM650P02CX_RFG")
      (fields
        (field (name "MF") "{'manufacturer': u'Taiwan Semiconductor Corporation'}")
        (field (name "MP") "TSM650P02CX_RFG")
      )
      (libsource (lib "Stepper_Controller") (part "TSM650P02CX_RFG"))
    )
    (comp (ref "Q3")
      (value "TSM650")
      (footprint "TRANS_TSM650P02CX_RFG")
      (fields
        (field (name "MF") "{'manufacturer': u'Taiwan Semiconductor Corporation'}")
        (field (name "MP") "TSM650P02CX_RFG")
      )
      (libsource (lib "Stepper_Controller") (part "TSM650P02CX_RFG"))
    )
    (comp (ref "Q4")
      (value "TSM650")
      (footprint "TRANS_TSM650P02CX_RFG")
      (fields
        (field (name "MF") "{'manufacturer': u'Taiwan Semiconductor Corporation'}")
        (field (name "MP") "TSM650P02CX_RFG")
      )
      (libsource (lib "Stepper_Controller") (part "TSM650P02CX_RFG"))
    )
    (comp (ref "Q5")
      (value "TSM650")
      (footprint "TRANS_TSM650P02CX_RFG")
      (fields
        (field (name "MF") "{'manufacturer': u'Taiwan Semiconductor Corporation'}")
        (field (name "MP") "TSM650P02CX_RFG")
      )
      (libsource (lib "Stepper_Controller") (part "TSM650P02CX_RFG"))
    )
    (comp (ref "R1")
      (value "1M")
      (footprint "RESC1608X55N")
      (fields (field (name "MP") "CRCW06031M00JNEAC") (field (name "MF") "{'manufacturer': u'Vishay'}"))
      (libsource (lib "Stepper_Controller") (part "CRCW06031M00JNEAC"))
    )
    (comp (ref "R3")
      (value "1M")
      (footprint "RESC1608X55N")
      (fields (field (name "MP") "CRCW06031M00JNEAC") (field (name "MF") "{'manufacturer': u'Vishay'}"))
      (libsource (lib "Stepper_Controller") (part "CRCW06031M00JNEAC"))
    )
    (comp (ref "R4")
      (value "1K")
      (footprint "RESC1608X55N")
      (fields (field (name "MP") "CRCW06031M00JNEAC") (field (name "MF") "{'manufacturer': u'Vishay'}"))
      (libsource (lib "Stepper_Controller") (part "CRCW06031M00JNEAC"))
    )
    (comp (ref "R5")
      (value "1K")
      (footprint "RESC1608X55N")
      (fields (field (name "MP") "CRCW06031M00JNEAC") (field (name "MF") "{'manufacturer': u'Vishay'}"))
      (libsource (lib "Stepper_Controller") (part "CRCW06031M00JNEAC"))
    )
    (comp (ref "R6")
      (value "100k")
      (footprint "RESC1608X55N")
      (fields (field (name "MP") "CRCW06031M00JNEAC") (field (name "MF") "{'manufacturer': u'Vishay'}"))
      (libsource (lib "Stepper_Controller") (part "CRCW06031M00JNEAC"))
    )
    (comp (ref "R7")
      (value "100k")
      (footprint "RESC1608X55N")
      (fields (field (name "MP") "CRCW06031M00JNEAC") (field (name "MF") "{'manufacturer': u'Vishay'}"))
      (libsource (lib "Stepper_Controller") (part "CRCW06031M00JNEAC"))
    )
    (comp (ref "R8")
      (value "1K")
      (footprint "RESC1608X55N")
      (fields (field (name "MP") "CRCW06031M00JNEAC") (field (name "MF") "{'manufacturer': u'Vishay'}"))
      (libsource (lib "Stepper_Controller") (part "CRCW06031M00JNEAC"))
    )
    (comp (ref "R9")
      (value "1K")
      (footprint "RESC1608X55N")
      (fields (field (name "MP") "CRCW06031M00JNEAC") (field (name "MF") "{'manufacturer': u'Vishay'}"))
      (libsource (lib "Stepper_Controller") (part "CRCW06031M00JNEAC"))
    )
    (comp (ref "R10")
      (value "22k")
      (footprint "RESC1608X55N")
      (fields (field (name "MP") "CRCW06031M00JNEAC") (field (name "MF") "{'manufacturer': u'Vishay'}"))
      (libsource (lib "Stepper_Controller") (part "CRCW06031M00JNEAC"))
    )
    (comp (ref "R11")
      (value "100k")
      (footprint "RESC1608X55N")
      (fields (field (name "MP") "CRCW06031M00JNEAC") (field (name "MF") "{'manufacturer': u'Vishay'}"))
      (libsource (lib "Stepper_Controller") (part "CRCW06031M00JNEAC"))
    )
    (comp (ref "R12")
      (value "1M")
      (footprint "RESC1608X55N")
      (fields (field (name "MP") "CRCW06031M00JNEAC") (field (name "MF") "{'manufacturer': u'Vishay'}"))
      (libsource (lib "Stepper_Controller") (part "CRCW06031M00JNEAC"))
    )
    (comp (ref "R13")
      (value "100k")
      (footprint "RESC1608X55N")
      (fields (field (name "MP") "CRCW06031M00JNEAC") (field (name "MF") "{'manufacturer': u'Vishay'}"))
      (libsource (lib "Stepper_Controller") (part "CRCW06031M00JNEAC"))
    )
    (comp (ref "R14")
      (value "100k")
      (footprint "RESC1608X55N")
      (fields (field (name "MP") "CRCW06031M00JNEAC") (field (name "MF") "{'manufacturer': u'Vishay'}"))
      (libsource (lib "Stepper_Controller") (part "CRCW06031M00JNEAC"))
    )
    (comp (ref "R15")
      (value "100k")
      (footprint "RESC1608X55N")
      (fields (field (name "MP") "CRCW06031M00JNEAC") (field (name "MF") "{'manufacturer': u'Vishay'}"))
      (libsource (lib "Stepper_Controller") (part "CRCW06031M00JNEAC"))
    )
    (comp (ref "R16")
      (value "100k")
      (footprint "RESC1608X55N")
      (fields (field (name "MP") "CRCW06031M00JNEAC") (field (name "MF") "{'manufacturer': u'Vishay'}"))
      (libsource (lib "Stepper_Controller") (part "CRCW06031M00JNEAC"))
    )
    (comp (ref "R17")
      (value "100k")
      (footprint "RESC1608X55N")
      (fields (field (name "MP") "CRCW06031M00JNEAC") (field (name "MF") "{'manufacturer': u'Vishay'}"))
      (libsource (lib "Stepper_Controller") (part "CRCW06031M00JNEAC"))
    )
    (comp (ref "R18")
      (value "100k")
      (footprint "RESC1608X55N")
      (fields (field (name "MP") "CRCW06031M00JNEAC") (field (name "MF") "{'manufacturer': u'Vishay'}"))
      (libsource (lib "Stepper_Controller") (part "CRCW06031M00JNEAC"))
    )
    (comp (ref "R19")
      (value "100k")
      (footprint "RESC1608X55N")
      (fields (field (name "MP") "CRCW06031M00JNEAC") (field (name "MF") "{'manufacturer': u'Vishay'}"))
      (libsource (lib "Stepper_Controller") (part "CRCW06031M00JNEAC"))
    )
    (comp (ref "R20")
      (value "100k")
      (footprint "RESC1608X55N")
      (fields (field (name "MP") "CRCW06031M00JNEAC") (field (name "MF") "{'manufacturer': u'Vishay'}"))
      (libsource (lib "Stepper_Controller") (part "CRCW06031M00JNEAC"))
    )
    (comp (ref "R21")
      (value "100k")
      (footprint "RESC1608X55N")
      (fields (field (name "MP") "CRCW06031M00JNEAC") (field (name "MF") "{'manufacturer': u'Vishay'}"))
      (libsource (lib "Stepper_Controller") (part "CRCW06031M00JNEAC"))
    )
    (comp (ref "R22")
      (value "100k")
      (footprint "RESC1608X55N")
      (fields (field (name "MP") "CRCW06031M00JNEAC") (field (name "MF") "{'manufacturer': u'Vishay'}"))
      (libsource (lib "Stepper_Controller") (part "CRCW06031M00JNEAC"))
    )
    (comp (ref "R23")
      (value "100k")
      (footprint "RESC1608X55N")
      (fields (field (name "MP") "CRCW06031M00JNEAC") (field (name "MF") "{'manufacturer': u'Vishay'}"))
      (libsource (lib "Stepper_Controller") (part "CRCW06031M00JNEAC"))
    )
    (comp (ref "R24")
      (value "100k")
      (footprint "RESC1608X55N")
      (fields (field (name "MP") "CRCW06031M00JNEAC") (field (name "MF") "{'manufacturer': u'Vishay'}"))
      (libsource (lib "Stepper_Controller") (part "CRCW06031M00JNEAC"))
    )
    (comp (ref "R25")
      (value "100k")
      (footprint "RESC1608X55N")
      (fields (field (name "MP") "CRCW06031M00JNEAC") (field (name "MF") "{'manufacturer': u'Vishay'}"))
      (libsource (lib "Stepper_Controller") (part "CRCW06031M00JNEAC"))
    )
    (comp (ref "R26")
      (value "100k")
      (footprint "RESC1608X55N")
      (fields (field (name "MP") "CRCW06031M00JNEAC") (field (name "MF") "{'manufacturer': u'Vishay'}"))
      (libsource (lib "Stepper_Controller") (part "CRCW06031M00JNEAC"))
    )
    (comp (ref "R27")
      (value "100k")
      (footprint "RESC1608X55N")
      (fields (field (name "MP") "CRCW06031M00JNEAC") (field (name "MF") "{'manufacturer': u'Vishay'}"))
      (libsource (lib "Stepper_Controller") (part "CRCW06031M00JNEAC"))
    )
    (comp (ref "R28")
      (value "100k")
      (footprint "RESC1608X55N")
      (fields (field (name "MP") "CRCW06031M00JNEAC") (field (name "MF") "{'manufacturer': u'Vishay'}"))
      (libsource (lib "Stepper_Controller") (part "CRCW06031M00JNEAC"))
    )
    (comp (ref "R29")
      (value "100k")
      (footprint "RESC1608X55N")
      (fields (field (name "MP") "CRCW06031M00JNEAC") (field (name "MF") "{'manufacturer': u'Vishay'}"))
      (libsource (lib "Stepper_Controller") (part "CRCW06031M00JNEAC"))
    )
    (comp (ref "R30")
      (value "100k")
      (footprint "RESC1608X55N")
      (fields (field (name "MP") "CRCW06031M00JNEAC") (field (name "MF") "{'manufacturer': u'Vishay'}"))
      (libsource (lib "Stepper_Controller") (part "CRCW06031M00JNEAC"))
    )
    (comp (ref "R31")
      (value "1K")
      (footprint "RESC1608X55N")
      (fields (field (name "MP") "CRCW06031M00JNEAC") (field (name "MF") "{'manufacturer': u'Vishay'}"))
      (libsource (lib "Stepper_Controller") (part "CRCW06031M00JNEAC"))
    )
    (comp (ref "R32")
      (value "1K")
      (footprint "RESC1608X55N")
      (fields (field (name "MP") "CRCW06031M00JNEAC") (field (name "MF") "{'manufacturer': u'Vishay'}"))
      (libsource (lib "Stepper_Controller") (part "CRCW06031M00JNEAC"))
    )
    (comp (ref "R33")
      (value "100k")
      (footprint "RESC1608X55N")
      (fields (field (name "MP") "CRCW06031M00JNEAC") (field (name "MF") "{'manufacturer': u'Vishay'}"))
      (libsource (lib "Stepper_Controller") (part "CRCW06031M00JNEAC"))
    )
    (comp (ref "R34")
      (value "1K")
      (footprint "RESC1608X55N")
      (fields (field (name "MP") "CRCW06031M00JNEAC") (field (name "MF") "{'manufacturer': u'Vishay'}"))
      (libsource (lib "Stepper_Controller") (part "CRCW06031M00JNEAC"))
    )
    (comp (ref "R35")
      (value "1K")
      (footprint "RESC1608X55N")
      (fields (field (name "MP") "CRCW06031M00JNEAC") (field (name "MF") "{'manufacturer': u'Vishay'}"))
      (libsource (lib "Stepper_Controller") (part "CRCW06031M00JNEAC"))
    )
    (comp (ref "R36")
      (value "120")
      (footprint "RESC1608X55N")
      (fields (field (name "MP") "CRCW06031M00JNEAC") (field (name "MF") "{'manufacturer': u'Vishay'}"))
      (libsource (lib "Stepper_Controller") (part "CRCW06031M00JNEAC"))
    )
    (comp (ref "R37")
      (value "10")
      (footprint "RESC1608X55N")
      (fields (field (name "MP") "CRCW06031M00JNEAC") (field (name "MF") "{'manufacturer': u'Vishay'}"))
      (libsource (lib "Stepper_Controller") (part "CRCW06031M00JNEAC"))
    )
    (comp (ref "R38")
      (value "10")
      (footprint "RESC1608X55N")
      (fields (field (name "MP") "CRCW06031M00JNEAC") (field (name "MF") "{'manufacturer': u'Vishay'}"))
      (libsource (lib "Stepper_Controller") (part "CRCW06031M00JNEAC"))
    )
    (comp (ref "R39")
      (value "10k")
      (footprint "RESC1608X55N")
      (fields (field (name "MP") "CRCW06031M00JNEAC") (field (name "MF") "{'manufacturer': u'Vishay'}"))
      (libsource (lib "Stepper_Controller") (part "CRCW06031M00JNEAC"))
    )
    (comp (ref "R40")
      (value "10")
      (footprint "RESC1608X55N")
      (fields (field (name "MP") "CRCW06031M00JNEAC") (field (name "MF") "{'manufacturer': u'Vishay'}"))
      (libsource (lib "Stepper_Controller") (part "CRCW06031M00JNEAC"))
    )
    (comp (ref "R41")
      (value "10")
      (footprint "RESC1608X55N")
      (fields (field (name "MP") "CRCW06031M00JNEAC") (field (name "MF") "{'manufacturer': u'Vishay'}"))
      (libsource (lib "Stepper_Controller") (part "CRCW06031M00JNEAC"))
    )
    (comp (ref "R42")
      (value "1K")
      (footprint "RESC1608X55N")
      (fields (field (name "MP") "CRCW06031M00JNEAC") (field (name "MF") "{'manufacturer': u'Vishay'}"))
      (libsource (lib "Stepper_Controller") (part "CRCW06031M00JNEAC"))
    )
    (comp (ref "RESET-EN")
      (value "SMD Jumper")
      (footprint "RESC1608X60N")
      (fields (field (name "MF") "{'manufacturer': u'Yageo'}") (field (name "MP") "PA0603-R-070RL"))
      (libsource (lib "Stepper_Controller") (part "PA0603-R-070RL"))
    )
    (comp (ref "RN1")
      (value "10k")
      (footprint "RESCAF80P320X160X60-8N")
      (fields (field (name "MP") "CAY16-220J4LF") (field (name "MF") "{'manufacturer': u'Bourns'}"))
      (libsource (lib "Stepper_Controller") (part "CAY16-220J4LF"))
    )
    (comp (ref "RN2")
      (value "22")
      (footprint "RESCAF80P320X160X60-8N")
      (fields (field (name "MP") "CAY16-220J4LF") (field (name "MF") "{'manufacturer': u'Bourns'}"))
      (libsource (lib "Stepper_Controller") (part "CAY16-220J4LF"))
    )
    (comp (ref "RN3")
      (value "1K")
      (footprint "RESCAF80P320X160X60-8N")
      (fields (field (name "MF") "{'manufacturer': u'Bourns'}") (field (name "MP") "CAY16-102J4LF"))
      (libsource (lib "Stepper_Controller") (part "CAY16-102J4LF"))
    )
    (comp (ref "RN4")
      (value "1K")
      (footprint "RESCAF80P320X160X60-8N")
      (fields (field (name "MF") "{'manufacturer': u'Bourns'}") (field (name "MP") "CAY16-102J4LF"))
      (libsource (lib "Stepper_Controller") (part "CAY16-102J4LF"))
    )
    (comp (ref "RN6")
      (value "100k")
      (footprint "RESCAF80P320X160X60-8N")
      (fields (field (name "MP") "CAY16-220J4LF") (field (name "MF") "{'manufacturer': u'Bourns'}"))
      (libsource (lib "Stepper_Controller") (part "CAY16-220J4LF"))
    )
    (comp (ref "RN7")
      (value "22")
      (footprint "RESCAF80P320X160X60-8N")
      (fields (field (name "MP") "CAY16-220J4LF") (field (name "MF") "{'manufacturer': u'Bourns'}"))
      (libsource (lib "Stepper_Controller") (part "CAY16-220J4LF"))
    )
    (comp (ref "RN8")
      (value "100k")
      (footprint "RESCAF80P320X160X60-8N")
      (fields (field (name "MP") "CAY16-220J4LF") (field (name "MF") "{'manufacturer': u'Bourns'}"))
      (libsource (lib "Stepper_Controller") (part "CAY16-220J4LF"))
    )
    (comp (ref "RN9")
      (value "220")
      (footprint "10SIP Res Array")
      (libsource (lib "Custom Library") (part "10SIP Res Array"))
    )
    (comp (ref "RN10")
      (value "220")
      (footprint "10SIP Res Array")
      (libsource (lib "Custom Library") (part "10SIP Res Array"))
    )
    (comp (ref "RN11")
      (value "330")
      (footprint "10SIP Res Array")
      (libsource (lib "Custom Library") (part "10SIP Res Array"))
    )
    (comp (ref "RN12")
      (value "330")
      (footprint "10SIP Res Array")
      (libsource (lib "Custom Library") (part "10SIP Res Array"))
    )
    (comp (ref "RPi")
      (value "RASPBERRY_PI_4B_4GB")
      (footprint "MODULE_RASPBERRY_PI_4B_4GB")
      (fields (field (name "MF") "{'manufacturer': u'Raspberry Pi'}"))
      (libsource (lib "Stepper_Controller") (part "RASPBERRY_PI_4B_4GB"))
    )
    (comp (ref "RS1")
      (value "Current Sense - 150m")
      (footprint "RESC6331X70N")
      (fields
        (field (name "MF") "{'manufacturer': u'Stackpole Electronics Inc'}")
        (field (name "MP") "CSRN2512FKR150")
      )
      (libsource (lib "Stepper_Controller") (part "CSRN2512FKR150"))
    )
    (comp (ref "RS2")
      (value "Current Sense - 150m")
      (footprint "RESC6331X70N")
      (fields
        (field (name "MF") "{'manufacturer': u'Stackpole Electronics Inc'}")
        (field (name "MP") "CSRN2512FKR150")
      )
      (libsource (lib "Stepper_Controller") (part "CSRN2512FKR150"))
    )
    (comp (ref "RS3")
      (value "Current Sense - 150m")
      (footprint "RESC6331X70N")
      (fields
        (field (name "MF") "{'manufacturer': u'Stackpole Electronics Inc'}")
        (field (name "MP") "CSRN2512FKR150")
      )
      (libsource (lib "Stepper_Controller") (part "CSRN2512FKR150"))
    )
    (comp (ref "RS4")
      (value "Current Sense - 150m")
      (footprint "RESC6331X70N")
      (fields
        (field (name "MF") "{'manufacturer': u'Stackpole Electronics Inc'}")
        (field (name "MP") "CSRN2512FKR150")
      )
      (libsource (lib "Stepper_Controller") (part "CSRN2512FKR150"))
    )
    (comp (ref "RS422 1")
      (value "MD-80SM")
      (footprint "CUI_MD-80SM")
      (fields (field (name "MF") "{'manufacturer': u'CUI Devices'}"))
      (libsource (lib "Stepper_Controller") (part "MD-80SM"))
    )
    (comp (ref "RV1")
      (value "CG0603MLC-05E")
      (footprint "VARC1608X56N")
      (description "Varistor 1 Circuit Surface Mount, MLCV 0603 (1608 Metric)")
      (fields (field (name "MF") "{'manufacturer': u'Bourns'}"))
      (libsource (lib "Stepper_Controller") (part "CG0603MLC-05E"))
    )
    (comp (ref "RV2")
      (value "CG0603MLC-05E")
      (footprint "VARC1608X56N")
      (description "Varistor 1 Circuit Surface Mount, MLCV 0603 (1608 Metric)")
      (fields (field (name "MF") "{'manufacturer': u'Bourns'}"))
      (libsource (lib "Stepper_Controller") (part "CG0603MLC-05E"))
    )
    (comp (ref "RX")
      (value "HSMA-C191")
      (footprint "0603")
      (description "http://octopart.com/hsma-c190-avago-550878")
      (fields (field (name "MF") "{'manufacturer': u'Broadcom Limited'}"))
      (libsource (lib "Stepper_Controller") (part "HSMA-C191"))
    )
    (comp (ref "RX_AT")
      (value "HSMA-C191")
      (footprint "0603")
      (description "http://octopart.com/hsma-c190-avago-550878")
      (fields (field (name "MF") "{'manufacturer': u'Broadcom Limited'}"))
      (libsource (lib "Stepper_Controller") (part "HSMA-C191"))
    )
    (comp (ref "R_REF")
      (value "61300411121")
      (footprint "61300411121")
      (description "THT Vertical Pin Header WR-PHD, Pitch 2.54 mm, Single Row, 4 pins")
      (fields (field (name "MANUFACTURER") "Wurth Elektronik") (field (name "PUBLISHER") "WurthElektronik"))
      (libsource (lib "") (part "WE-CN-1P-M-R4_1"))
    )
    (comp (ref "S1")
      (value "TL330")
      (footprint "SW_TL3301NF260QG")
      (fields (field (name "MP") "TL3301NF260QG") (field (name "MF") "{'manufacturer': u'E-Switch'}"))
      (libsource (lib "Stepper_Controller") (part "TL3301NF260QG"))
    )
    (comp (ref "SCSI")
      (value "10090099-S254VLF")
      (footprint "10090099-S254VLF")
      (description "<b>FCI 10090099-S254[VLX]LF DB-25 female connector, right angle PCB mount</b>")
      (fields (field (name "MF") "{'manufacturer': u'Amphenol ICC'}"))
      (libsource (lib "Stepper_Controller") (part "10090099-S254VLF"))
    )
    (comp (ref "SST_CFG")
      (value "75915-308GLF")
      (footprint "AMPHENOL_75915-308GLF")
      (fields (field (name "MF") "{'manufacturer': u'Amphenol ICC (FCI)'}"))
      (libsource (lib "") (part "75915-308GLF_1"))
    )
    (comp (ref "SST_EXP")
      (value "TMC2209_SILENTSTEPSTICK")
      (footprint "MODULE_TMC2209_SILENTSTEPSTICK")
      (fields (field (name "MF") "{'manufacturer': u'Trinamic Motion Control GmbH'}"))
      (libsource (lib "Stepper_Controller") (part "TMC2209_SILENTSTEPSTICK"))
    )
    (comp (ref "STPDIR")
      (value "75915-308GLF")
      (footprint "AMPHENOL_75915-308GLF")
      (fields (field (name "MF") "{'manufacturer': u'Amphenol ICC (FCI)'}"))
      (libsource (lib "Stepper_Controller") (part "75915-308GLF"))
    )
    (comp (ref "TERM_PWR")
      (value "219-2MSTR")
      (footprint "SW_219-2MSTR")
      (description "Dip Switch SPST 2 Position Surface Mount Slide (Standard) Actuator 100mA 20VDC")
      (fields (field (name "MF") "{'manufacturer': u'CTS CORP'}"))
      (libsource (lib "Stepper_Controller") (part "219-2MSTR"))
    )
    (comp (ref "TX")
      (value "HSMA-C191")
      (footprint "0603")
      (description "http://octopart.com/hsma-c190-avago-550878")
      (fields (field (name "MF") "{'manufacturer': u'Broadcom Limited'}"))
      (libsource (lib "Stepper_Controller") (part "HSMA-C191"))
    )
    (comp (ref "TX_AT")
      (value "HSMA-C191")
      (footprint "0603")
      (description "http://octopart.com/hsma-c190-avago-550878")
      (fields (field (name "MF") "{'manufacturer': u'Broadcom Limited'}"))
      (libsource (lib "Stepper_Controller") (part "HSMA-C191"))
    )
    (comp (ref "U1")
      (value "ATMEGA2560-16AU")
      (footprint "QFP50P1600X1600X120-100N")
      (fields (field (name "MF") "{'manufacturer': u'Microchip'}"))
      (libsource (lib "Stepper_Controller") (part "ATMEGA2560-16AU"))
    )
    (comp (ref "U2")
      (value "ATMEGA16U2-AU")
      (footprint "QFP80P900X900X120-32N")
      (fields (field (name "MF") "{'manufacturer': u'Microchip'}"))
      (libsource (lib "Stepper_Controller") (part "ATMEGA16U2-AU"))
    )
    (comp (ref "U3")
      (value "LM1085, RPi Power @ 3A")
      (footprint "TO254P1435X464-4N")
      (description "3A Fixed / Adjustable Output Linear Regulator")
      (fields
        (field (name "MF") "{'manufacturer': u'Texas Instruments'}")
        (field (name "MP") "LM1085ISX-5.0/NOPB")
      )
      (libsource (lib "Stepper_Controller") (part "LM1085ISX-5.0/NOPB"))
    )
    (comp (ref "U4")
      (value "LM1085, Nominal Power")
      (footprint "TO254P1435X464-4N")
      (description "3A Fixed / Adjustable Output Linear Regulator")
      (fields
        (field (name "MF") "{'manufacturer': u'Texas Instruments'}")
        (field (name "MP") "LM1085ISX-5.0/NOPB")
      )
      (libsource (lib "Stepper_Controller") (part "LM1085ISX-5.0/NOPB"))
    )
    (comp (ref "U5")
      (value "LM324APWR")
      (footprint "SOP65P640X120-14N")
      (fields (field (name "MF") "{'manufacturer': u'Texas Instruments'}"))
      (libsource (lib "Stepper_Controller") (part "LM324APWR"))
    )
    (comp (ref "U6")
      (value "LP2985-33, 3.3V Power @ 150mA")
      (footprint "SOT95P280X145-5N")
      (fields
        (field (name "MF") "{'manufacturer': u'Texas Instruments'}")
        (field (name "MP") "LP2985-33DBVRE4")
      )
      (libsource (lib "Stepper_Controller") (part "LP2985-33DBVRE4"))
    )
    (comp (ref "U7")
      (value "TMC429-PI24")
      (footprint "SOP24")
      (fields (field (name "MF") "{'manufacturer': u'Trinamic Motion'}"))
      (libsource (lib "Stepper_Controller") (part "TMC429-PI24"))
    )
    (comp (ref "U8")
      (value "TMC2226-SA")
      (footprint "SOP65P640X120-29N")
      (fields (field (name "MF") "{'manufacturer': u'Trinamic Motion Control GmbH'}"))
      (libsource (lib "Stepper_Controller") (part "TMC2226-SA"))
    )
    (comp (ref "U9")
      (value "TMC2226-SA")
      (footprint "SOP65P640X120-29N")
      (fields (field (name "MF") "{'manufacturer': u'Trinamic Motion Control GmbH'}"))
      (libsource (lib "Stepper_Controller") (part "TMC2226-SA"))
    )
    (comp (ref "U11")
      (value "TXS0102DCUR")
      (footprint "SOP50P310X90-8N")
      (fields (field (name "MF") "{'manufacturer': u'Texas Instruments'}"))
      (libsource (lib "Stepper_Controller") (part "TXS0102DCUR"))
    )
    (comp (ref "U12")
      (value "USB2514BT/M2")
      (footprint "QFN50P600X600X100-37N")
      (description "USB Hub Controller USB Interface 36-SQFN (6x6)")
      (fields (field (name "MF") "{'manufacturer': u'Microchip'}"))
      (libsource (lib "Stepper_Controller") (part "USB2514BT/M2"))
    )
    (comp (ref "U13")
      (value "PRTR5V0U2F")
      (footprint "PSON50P145X100X90-6N")
      (description "Clamp Ipp Tvs Diode Surface Mount 6-XSON, SOT886 (1.45x1)")
      (fields (field (name "MF") "{'manufacturer': u'Nexperia USA'}"))
      (libsource (lib "Stepper_Controller") (part "PRTR5V0U2F"))
    )
    (comp (ref "U14")
      (value "SN74LS641-1DW")
      (footprint "SOIC127P1030X265-20N")
      (fields (field (name "MF") "{'manufacturer': u'Texas Instruments'}"))
      (libsource (lib "Stepper_Controller") (part "SN74LS641-1DW"))
    )
    (comp (ref "U15")
      (value "SN74LS641-1DW")
      (footprint "SOIC127P1030X265-20N")
      (fields (field (name "MF") "{'manufacturer': u'Texas Instruments'}"))
      (libsource (lib "Stepper_Controller") (part "SN74LS641-1DW"))
    )
    (comp (ref "U16")
      (value "SN74LS641-1DW")
      (footprint "SOIC127P1030X265-20N")
      (fields (field (name "MF") "{'manufacturer': u'Texas Instruments'}"))
      (libsource (lib "Stepper_Controller") (part "SN74LS641-1DW"))
    )
    (comp (ref "U17")
      (value "SN74LS641-1DW")
      (footprint "SOIC127P1030X265-20N")
      (fields (field (name "MF") "{'manufacturer': u'Texas Instruments'}"))
      (libsource (lib "Stepper_Controller") (part "SN74LS641-1DW"))
    )
    (comp (ref "U18")
      (value "MAX490CUA")
      (footprint "SOP65P490X110-8N")
      (fields (field (name "MF") "{'manufacturer': u'Maxim Integrated'}"))
      (libsource (lib "Stepper_Controller") (part "MAX490CUA"))
    )
    (comp (ref "U19")
      (value "SN74LVC2GU04DBVT")
      (footprint "SOT95P280X145-6N")
      (fields (field (name "MF") "{'manufacturer': u'Texas Instruments'}"))
      (libsource (lib "Stepper_Controller") (part "SN74LVC2GU04DBVT"))
    )
    (comp (ref "UART3")
      (value "77311-118-02LF")
      (footprint "AMPHENOL_77311-118-02LF")
      (fields (field (name "MF") "{'manufacturer': u'Amphenol ICC'}"))
      (libsource (lib "") (part "77311-118-02LF_2"))
    )
    (comp (ref "USB")
      (value "AU-Y1007")
      (footprint "ASSMANN_AU-Y1007")
      (description "Conn Usb Rtang Female Type b Pcb")
      (fields (field (name "MF") "{'manufacturer': u'Assmann WSW'}"))
      (libsource (lib "Stepper_Controller") (part "AU-Y1007"))
    )
    (comp (ref "USBOUT1")
      (value "1903815-1")
      (footprint "TE_1903815-1")
      (description "Conn USB 2.0 Type A RCP 4/4 POS 2.5mm Solder RA Thru-Hole 8 Terminal 2 Port Tray")
      (fields (field (name "MF") "{'manufacturer': u'TE Connectivity'}"))
      (libsource (lib "Stepper_Controller") (part "1903815-1"))
    )
    (comp (ref "USBOUT2")
      (value "1903815-1")
      (footprint "TE_1903815-1")
      (description "Conn USB 2.0 Type A RCP 4/4 POS 2.5mm Solder RA Thru-Hole 8 Terminal 2 Port Tray")
      (fields (field (name "MF") "{'manufacturer': u'TE Connectivity'}"))
      (libsource (lib "Stepper_Controller") (part "1903815-1"))
    )
    (comp (ref "USBPi")
      (value "6364372-2")
      (footprint "TE_6364372-2")
      (description "Conn USB 2.0 Type A RCP 4 POS Solder RA Thru-Hole 4 Terminal 1 Port Box/Tube")
      (fields (field (name "MF") "{'manufacturer': u'TE Connectivity'}"))
      (libsource (lib "Stepper_Controller") (part "6364372-2"))
    )
    (comp (ref "XY_CFG")
      (value "75915-308GLF")
      (footprint "AMPHENOL_75915-308GLF")
      (fields (field (name "MF") "{'manufacturer': u'Amphenol ICC (FCI)'}"))
      (libsource (lib "") (part "75915-308GLF_1"))
    )
    (comp (ref "Y1")
      (value "ABLS-16.000MHZ-20-B-4-Y-T")
      (footprint "XTAL_ABLS-16.000MHZ-20-B-4-Y-T")
      (fields (field (name "MF") "{'manufacturer': u'Abracon LLC'}"))
      (libsource (lib "Stepper_Controller") (part "ABLS-16.000MHZ-20-B-4-Y-T"))
    )
    (comp (ref "Y2")
      (value "CSTNE16M0V530000R0")
      (footprint "OSC_CSTNE16M0V530000R0")
      (description "16MHz Ceramic Resonator Built in Capacitor 15pF Â±0.15% 40 Ohms -40Â°C ~ 125Â°C Surface Mount")
      (fields (field (name "MF") "{'manufacturer': u'Murata Electronics'}"))
      (libsource (lib "Stepper_Controller") (part "CSTNE16M0V530000R0"))
    )
    (comp (ref "Y3")
      (value "ECS-240MHz")
      (footprint "XTAL_ECS-240-18-5PXEN-TR")
      (description "CRYSTAL SMD")
      (fields (field (name "MF") "{'manufacturer': u'ECS Inc.'}") (field (name "MP") "ECS-240-18-5PXEN-TR"))
      (libsource (lib "Stepper_Controller") (part "ECS-240-18-5PXEN-TR"))
    )
  )
  (nets
    (net (code "1") (name "+5") (class "Default")
      (node (ref "C11") (pin "1") (pinfunction "1_1") (pintype "passive"))
      (node (ref "C12") (pin "1") (pinfunction "1_1") (pintype "passive"))
      (node (ref "C13") (pin "2") (pinfunction "2_2") (pintype "passive"))
      (node (ref "C17") (pin "1") (pinfunction "1_1") (pintype "passive"))
      (node (ref "C18") (pin "1") (pinfunction "1_1") (pintype "passive"))
      (node (ref "C21") (pin "1") (pinfunction "1_1") (pintype "passive"))
      (node (ref "C28") (pin "2") (pinfunction "2_2") (pintype "passive"))
      (node (ref "C29") (pin "1") (pinfunction "1_1") (pintype "passive"))
      (node (ref "C3") (pin "2") (pinfunction "2_2") (pintype "passive"))
      (node (ref "C40") (pin "1") (pinfunction "1_1") (pintype "passive"))
      (node (ref "C47") (pin "1") (pinfunction "1_1") (pintype "passive"))
      (node (ref "C48") (pin "1") (pinfunction "1_1") (pintype "passive"))
      (node (ref "C49") (pin "1") (pinfunction "1_1") (pintype "passive"))
      (node (ref "C50") (pin "1") (pinfunction "1_1") (pintype "passive"))
      (node (ref "C51") (pin "2") (pinfunction "2_2") (pintype "passive"))
      (node (ref "C7") (pin "2") (pinfunction "2_2") (pintype "passive"))
      (node (ref "CD10") (pin "1") (pinfunction "1_1") (pintype "passive"))
      (node (ref "CD11") (pin "1") (pinfunction "1_1") (pintype "passive"))
      (node (ref "CD12") (pin "1") (pinfunction "1_1") (pintype "passive"))
      (node (ref "CD9") (pin "1") (pinfunction "1_1") (pintype "passive"))
      (node (ref "D1") (pin "C") (pinfunction "C_C") (pintype "passive"))
      (node (ref "D4") (pin "A") (pinfunction "A_A") (pintype "passive"))
      (node (ref "D6") (pin "C") (pinfunction "K_C") (pintype "passive"))
      (node (ref "ICSP16") (pin "2") (pinfunction "2_2") (pintype "passive"))
      (node (ref "ICSP2560") (pin "2") (pinfunction "2_2") (pintype "passive"))
      (node (ref "L1") (pin "1") (pinfunction "1_1") (pintype "passive"))
      (node (ref "PC6") (pin "1") (pinfunction "1_1") (pintype "passive"))
      (node (ref "PSU") (pin "3") (pinfunction "3_3") (pintype "passive"))
      (node (ref "Q1") (pin "2") (pinfunction "S_2") (pintype "passive"))
      (node (ref "R34") (pin "2") (pinfunction "2_2") (pintype "passive"))
      (node (ref "R35") (pin "2") (pinfunction "2_2") (pintype "passive"))
      (node (ref "R39") (pin "2") (pinfunction "2_2") (pintype "passive"))
      (node (ref "RN1") (pin "1") (pinfunction "1_1") (pintype "passive"))
      (node (ref "RN1") (pin "4") (pinfunction "4_4") (pintype "passive"))
      (node (ref "RN3") (pin "7") (pinfunction "7_7") (pintype "passive"))
      (node (ref "RN3") (pin "8") (pinfunction "8_8") (pintype "passive"))
      (node (ref "RN4") (pin "8") (pinfunction "8_8") (pintype "passive"))
      (node (ref "SST_EXP") (pin "2") (pinfunction "VIO_2") (pintype "power_in"))
      (node (ref "TERM_PWR") (pin "1A") (pinfunction "COM1_1A") (pintype "passive"))
      (node (ref "U1") (pin "10") (pinfunction "VCC_3_10") (pintype "power_in"))
      (node (ref "U1") (pin "31") (pinfunction "VCC_2_31") (pintype "power_in"))
      (node (ref "U1") (pin "61") (pinfunction "VCC_4_61") (pintype "power_in"))
      (node (ref "U1") (pin "80") (pinfunction "VCC_80") (pintype "power_in"))
      (node (ref "U11") (pin "7") (pinfunction "VCCB_7") (pintype "power_in"))
      (node (ref "U14") (pin "20") (pinfunction "VCC_20") (pintype "power_in"))
      (node (ref "U15") (pin "20") (pinfunction "VCC_20") (pintype "power_in"))
      (node (ref "U16") (pin "20") (pinfunction "VCC_20") (pintype "power_in"))
      (node (ref "U17") (pin "20") (pinfunction "VCC_20") (pintype "power_in"))
      (node (ref "U18") (pin "3") (pinfunction "VCC_3") (pintype "power_in"))
      (node (ref "U19") (pin "5") (pinfunction "VCC_5") (pintype "power_in"))
      (node (ref "U2") (pin "32") (pinfunction "AVCC_32") (pintype "power_in"))
      (node (ref "U2") (pin "4") (pinfunction "VCC_4") (pintype "power_in"))
      (node (ref "U4") (pin "4") (pinfunction "OUTPUT_4_4") (pintype "output"))
      (node (ref "U5") (pin "4") (pinfunction "VCC_4") (pintype "power_in"))
      (node (ref "U6") (pin "1") (pinfunction "VIN_1") (pintype "input"))
      (node (ref "U6") (pin "3") (pinfunction "ON/_~OFF_3") (pintype "input"))
      (node (ref "U7") (pin "20") (pinfunction "V5@2_20") (pintype "input"))
      (node (ref "U7") (pin "5") (pinfunction "V5@1_5") (pintype "input"))
      (node (ref "U8") (pin "19") (pinfunction "VCC_IO_19") (pintype "power_in"))
      (node (ref "U9") (pin "19") (pinfunction "VCC_IO_19") (pintype "power_in"))
    )
    (net (code "2") (name "/3V3") (class "Default")
      (node (ref "C20") (pin "2") (pinfunction "2_2") (pintype "passive"))
      (node (ref "C9") (pin "1") (pinfunction "1_1") (pintype "passive"))
      (node (ref "R13") (pin "2") (pinfunction "2_2") (pintype "passive"))
      (node (ref "R14") (pin "2") (pinfunction "2_2") (pintype "passive"))
      (node (ref "R15") (pin "2") (pinfunction "2_2") (pintype "passive"))
      (node (ref "R16") (pin "2") (pinfunction "2_2") (pintype "passive"))
      (node (ref "R17") (pin "2") (pinfunction "2_2") (pintype "passive"))
      (node (ref "R18") (pin "2") (pinfunction "2_2") (pintype "passive"))
      (node (ref "R19") (pin "2") (pinfunction "2_2") (pintype "passive"))
      (node (ref "R20") (pin "2") (pinfunction "2_2") (pintype "passive"))
      (node (ref "R21") (pin "2") (pinfunction "2_2") (pintype "passive"))
      (node (ref "R22") (pin "2") (pinfunction "2_2") (pintype "passive"))
      (node (ref "R23") (pin "2") (pinfunction "2_2") (pintype "passive"))
      (node (ref "R24") (pin "2") (pinfunction "2_2") (pintype "passive"))
      (node (ref "R25") (pin "2") (pinfunction "2_2") (pintype "passive"))
      (node (ref "R26") (pin "2") (pinfunction "2_2") (pintype "passive"))
      (node (ref "R27") (pin "2") (pinfunction "2_2") (pintype "passive"))
      (node (ref "R28") (pin "2") (pinfunction "2_2") (pintype "passive"))
      (node (ref "R29") (pin "2") (pinfunction "2_2") (pintype "passive"))
      (node (ref "R30") (pin "2") (pinfunction "2_2") (pintype "passive"))
      (node (ref "RN6") (pin "8") (pinfunction "8_8") (pintype "passive"))
      (node (ref "U11") (pin "3") (pinfunction "VCCA_3") (pintype "power_in"))
      (node (ref "U12") (pin "10") (pinfunction "VDDA33_10") (pintype "power_in"))
      (node (ref "U12") (pin "15") (pinfunction "VDD33_15") (pintype "power_in"))
      (node (ref "U12") (pin "23") (pinfunction "VDD33_23") (pintype "power_in"))
      (node (ref "U12") (pin "29") (pinfunction "VDDA33_29") (pintype "power_in"))
      (node (ref "U12") (pin "36") (pinfunction "VDDA33_36") (pintype "power_in"))
      (node (ref "U12") (pin "5") (pinfunction "VDDA33_5") (pintype "power_in"))
      (node (ref "U5") (pin "2") (pinfunction "1IN-_2") (pintype "input"))
      (node (ref "U6") (pin "5") (pinfunction "VOUT_5") (pintype "output"))
    )
    (net (code "3") (name "/3V3Pi") (class "Default")
      (node (ref "RPi") (pin "1") (pinfunction "3V3_1") (pintype "power_in"))
      (node (ref "RPi") (pin "17") (pinfunction "3V3_17") (pintype "power_in"))
    )
    (net (code "4") (name "/5VO1") (class "Default")
      (node (ref "C24") (pin "1") (pinfunction "1_1") (pintype "passive"))
      (node (ref "U8") (pin "11") (pinfunction "5VOUT_11") (pintype "output"))
    )
    (net (code "5") (name "/5VO2") (class "Default")
      (node (ref "C25") (pin "1") (pinfunction "1_1") (pintype "passive"))
      (node (ref "U9") (pin "11") (pinfunction "5VOUT_11") (pintype "output"))
    )
    (net (code "6") (name "/24V") (class "Default")
      (node (ref "C26") (pin "1") (pinfunction "1_1") (pintype "passive"))
      (node (ref "C27") (pin "1") (pinfunction "1_1") (pintype "passive"))
      (node (ref "C30") (pin "1") (pinfunction "1_1") (pintype "passive"))
      (node (ref "C31") (pin "1") (pinfunction "1_1") (pintype "passive"))
      (node (ref "C32") (pin "1") (pinfunction "1_1") (pintype "passive"))
      (node (ref "C33") (pin "1") (pinfunction "1_1") (pintype "passive"))
      (node (ref "C34") (pin "1") (pinfunction "1_1") (pintype "passive"))
      (node (ref "C35") (pin "1") (pinfunction "1_1") (pintype "passive"))
      (node (ref "C36") (pin "1") (pinfunction "1_1") (pintype "passive"))
      (node (ref "C37") (pin "1") (pinfunction "1_1") (pintype "passive"))
      (node (ref "CD1") (pin "1") (pinfunction "1_1") (pintype "passive"))
      (node (ref "CD13") (pin "1") (pinfunction "1_1") (pintype "passive"))
      (node (ref "CD2") (pin "1") (pinfunction "1_1") (pintype "passive"))
      (node (ref "CD3") (pin "1") (pinfunction "1_1") (pintype "passive"))
      (node (ref "CD4") (pin "1") (pinfunction "1_1") (pintype "passive"))
      (node (ref "D15") (pin "C") (pinfunction "K_C") (pintype "passive"))
      (node (ref "PSU") (pin "1") (pinfunction "1_1") (pintype "passive"))
      (node (ref "PSU") (pin "2") (pinfunction "2_2") (pintype "passive"))
      (node (ref "SST_EXP") (pin "8") (pinfunction "VM_8") (pintype "power_in"))
      (node (ref "U8") (pin "26") (pinfunction "VS_26") (pintype "power_in"))
      (node (ref "U8") (pin "3") (pinfunction "VS_3") (pintype "power_in"))
      (node (ref "U9") (pin "26") (pinfunction "VS_26") (pintype "power_in"))
      (node (ref "U9") (pin "3") (pinfunction "VS_3") (pintype "power_in"))
    )
    (net (code "7") (name "/AREF") (class "Default")
      (node (ref "C16") (pin "2") (pinfunction "2_2") (pintype "passive"))
      (node (ref "U1") (pin "98") (pinfunction "AREF_98") (pintype "input"))
    )
    (net (code "8") (name "/AVCC") (class "Default")
      (node (ref "C14") (pin "2") (pinfunction "2_2") (pintype "passive"))
      (node (ref "L1") (pin "2") (pinfunction "2_2") (pintype "passive"))
      (node (ref "U1") (pin "100") (pinfunction "AVCC_100") (pintype "power_in"))
    )
    (net (code "9") (name "/CMP") (class "Default")
      (node (ref "C8") (pin "1") (pinfunction "1_1") (pintype "passive"))
      (node (ref "RN1") (pin "6") (pinfunction "6_6") (pintype "passive"))
      (node (ref "RN1") (pin "7") (pinfunction "7_7") (pintype "passive"))
      (node (ref "U5") (pin "3") (pinfunction "1IN+_3") (pintype "input"))
    )
    (net (code "10") (name "/C_ACK") (class "Default")
      (node (ref "RN11") (pin "9") (pinfunction "9_9") (pintype "passive"))
      (node (ref "RN9") (pin "9") (pinfunction "9_9") (pintype "passive"))
      (node (ref "SCSI") (pin "5") (pinfunction "5_5") (pintype "passive"))
      (node (ref "U17") (pin "16") (pinfunction "B3_16") (pintype "bidirectional"))
    )
    (net (code "11") (name "/C_ATN") (class "Default")
      (node (ref "RN11") (pin "10") (pinfunction "10_10") (pintype "passive"))
      (node (ref "RN9") (pin "10") (pinfunction "10_10") (pintype "passive"))
      (node (ref "SCSI") (pin "17") (pinfunction "17_17") (pintype "passive"))
      (node (ref "U17") (pin "15") (pinfunction "B4_15") (pintype "bidirectional"))
    )
    (net (code "12") (name "/C_BSY") (class "Default")
      (node (ref "RN11") (pin "6") (pinfunction "6_6") (pintype "passive"))
      (node (ref "RN9") (pin "6") (pinfunction "6_6") (pintype "passive"))
      (node (ref "SCSI") (pin "6") (pinfunction "6_6") (pintype "passive"))
      (node (ref "U15") (pin "14") (pinfunction "B5_14") (pintype "bidirectional"))
    )
    (net (code "13") (name "/C_CD") (class "Default")
      (node (ref "RN11") (pin "4") (pinfunction "4_4") (pintype "passive"))
      (node (ref "RN9") (pin "4") (pinfunction "4_4") (pintype "passive"))
      (node (ref "SCSI") (pin "15") (pinfunction "15_15") (pintype "passive"))
      (node (ref "U15") (pin "16") (pinfunction "B3_16") (pintype "bidirectional"))
    )
    (net (code "14") (name "/C_D0") (class "Default")
      (node (ref "RN10") (pin "3") (pinfunction "3_3") (pintype "passive"))
      (node (ref "RN12") (pin "3") (pinfunction "3_3") (pintype "passive"))
      (node (ref "SCSI") (pin "8") (pinfunction "8_8") (pintype "passive"))
      (node (ref "U14") (pin "4") (pinfunction "A3_4") (pintype "bidirectional"))
    )
    (net (code "15") (name "/C_D1") (class "Default")
      (node (ref "RN10") (pin "4") (pinfunction "4_4") (pintype "passive"))
      (node (ref "RN12") (pin "4") (pinfunction "4_4") (pintype "passive"))
      (node (ref "SCSI") (pin "21") (pinfunction "21_21") (pintype "passive"))
      (node (ref "U14") (pin "3") (pinfunction "A2_3") (pintype "bidirectional"))
    )
    (net (code "16") (name "/C_D2") (class "Default")
      (node (ref "RN10") (pin "5") (pinfunction "5_5") (pintype "passive"))
      (node (ref "RN12") (pin "5") (pinfunction "5_5") (pintype "passive"))
      (node (ref "SCSI") (pin "22") (pinfunction "22_22") (pintype "passive"))
      (node (ref "U14") (pin "2") (pinfunction "A1_2") (pintype "bidirectional"))
    )
    (net (code "17") (name "/C_D3") (class "Default")
      (node (ref "RN10") (pin "6") (pinfunction "6_6") (pintype "passive"))
      (node (ref "RN12") (pin "6") (pinfunction "6_6") (pintype "passive"))
      (node (ref "SCSI") (pin "10") (pinfunction "10_10") (pintype "passive"))
      (node (ref "U16") (pin "6") (pinfunction "A5_6") (pintype "bidirectional"))
    )
    (net (code "18") (name "/C_D4") (class "Default")
      (node (ref "RN10") (pin "7") (pinfunction "7_7") (pintype "passive"))
      (node (ref "RN12") (pin "7") (pinfunction "7_7") (pintype "passive"))
      (node (ref "SCSI") (pin "23") (pinfunction "23_23") (pintype "passive"))
      (node (ref "U16") (pin "5") (pinfunction "A4_5") (pintype "bidirectional"))
    )
    (net (code "19") (name "/C_D5") (class "Default")
      (node (ref "RN10") (pin "8") (pinfunction "8_8") (pintype "passive"))
      (node (ref "RN12") (pin "8") (pinfunction "8_8") (pintype "passive"))
      (node (ref "SCSI") (pin "11") (pinfunction "11_11") (pintype "passive"))
      (node (ref "U16") (pin "4") (pinfunction "A3_4") (pintype "bidirectional"))
    )
    (net (code "20") (name "/C_D6") (class "Default")
      (node (ref "RN10") (pin "9") (pinfunction "9_9") (pintype "passive"))
      (node (ref "RN12") (pin "9") (pinfunction "9_9") (pintype "passive"))
      (node (ref "SCSI") (pin "12") (pinfunction "12_12") (pintype "passive"))
      (node (ref "U16") (pin "3") (pinfunction "A2_3") (pintype "bidirectional"))
    )
    (net (code "21") (name "/C_D7") (class "Default")
      (node (ref "RN10") (pin "10") (pinfunction "10_10") (pintype "passive"))
      (node (ref "RN12") (pin "10") (pinfunction "10_10") (pintype "passive"))
      (node (ref "SCSI") (pin "13") (pinfunction "13_13") (pintype "passive"))
      (node (ref "U16") (pin "2") (pinfunction "A1_2") (pintype "bidirectional"))
    )
    (net (code "22") (name "/C_DP") (class "Default")
      (node (ref "RN10") (pin "2") (pinfunction "2_2") (pintype "passive"))
      (node (ref "RN12") (pin "2") (pinfunction "2_2") (pintype "passive"))
      (node (ref "SCSI") (pin "20") (pinfunction "20_20") (pintype "passive"))
      (node (ref "U14") (pin "5") (pinfunction "A4_5") (pintype "bidirectional"))
    )
    (net (code "23") (name "/C_IO") (class "Default")
      (node (ref "RN11") (pin "2") (pinfunction "2_2") (pintype "passive"))
      (node (ref "RN9") (pin "2") (pinfunction "2_2") (pintype "passive"))
      (node (ref "SCSI") (pin "3") (pinfunction "3_3") (pintype "passive"))
      (node (ref "U15") (pin "18") (pinfunction "B1_18") (pintype "bidirectional"))
    )
    (net (code "24") (name "/C_MSG") (class "Default")
      (node (ref "RN11") (pin "5") (pinfunction "5_5") (pintype "passive"))
      (node (ref "RN9") (pin "5") (pinfunction "5_5") (pintype "passive"))
      (node (ref "SCSI") (pin "2") (pinfunction "2_2") (pintype "passive"))
      (node (ref "U15") (pin "15") (pinfunction "B4_15") (pintype "bidirectional"))
    )
    (net (code "25") (name "/C_REQ") (class "Default")
      (node (ref "RN11") (pin "3") (pinfunction "3_3") (pintype "passive"))
      (node (ref "RN9") (pin "3") (pinfunction "3_3") (pintype "passive"))
      (node (ref "SCSI") (pin "1") (pinfunction "1_1") (pintype "passive"))
      (node (ref "U15") (pin "17") (pinfunction "B2_17") (pintype "bidirectional"))
    )
    (net (code "26") (name "/C_RST") (class "Default")
      (node (ref "RN11") (pin "8") (pinfunction "8_8") (pintype "passive"))
      (node (ref "RN9") (pin "8") (pinfunction "8_8") (pintype "passive"))
      (node (ref "SCSI") (pin "4") (pinfunction "4_4") (pintype "passive"))
      (node (ref "U17") (pin "17") (pinfunction "B2_17") (pintype "bidirectional"))
    )
    (net (code "27") (name "/C_SEL") (class "Default")
      (node (ref "RN11") (pin "7") (pinfunction "7_7") (pintype "passive"))
      (node (ref "RN9") (pin "7") (pinfunction "7_7") (pintype "passive"))
      (node (ref "SCSI") (pin "19") (pinfunction "19_19") (pintype "passive"))
      (node (ref "U17") (pin "18") (pinfunction "B1_18") (pintype "bidirectional"))
    )
    (net (code "28") (name "/DBG_LED") (class "Default")
      (node (ref "R32") (pin "2") (pinfunction "2_2") (pintype "passive"))
      (node (ref "RPi") (pin "29") (pinfunction "GPIO5_29") (pintype "bidirectional"))
    )
    (net (code "29") (name "/DIAG_1") (class "Default")
      (node (ref "U19") (pin "1") (pinfunction "1A_1") (pintype "input"))
      (node (ref "U5") (pin "5") (pinfunction "2IN+_5") (pintype "input"))
      (node (ref "U8") (pin "15") (pinfunction "DIAG_15") (pintype "output"))
    )
    (net (code "30") (name "/DIAG_2") (class "Default")
      (node (ref "U19") (pin "3") (pinfunction "2A_3") (pintype "input"))
      (node (ref "U5") (pin "10") (pinfunction "3IN+_10") (pintype "input"))
      (node (ref "U9") (pin "15") (pinfunction "DIAG_15") (pintype "output"))
    )
    (net (code "31") (name "/DIAG_3") (class "Default")
      (node (ref "SST_CFG") (pin "05") (pinfunction "05_05") (pintype "passive"))
      (node (ref "SST_EXP") (pin "18") (pinfunction "DIAG_18") (pintype "output"))
    )
    (net (code "32") (name "/DIR_1") (class "Default")
      (node (ref "STPDIR") (pin "05") (pinfunction "05_05") (pintype "passive"))
      (node (ref "U7") (pin "16") (pinfunction "SCK_S_D1_16") (pintype "output"))
      (node (ref "U8") (pin "23") (pinfunction "DIR_23") (pintype "input"))
    )
    (net (code "33") (name "/DIR_2") (class "Default")
      (node (ref "STPDIR") (pin "06") (pinfunction "06_06") (pintype "passive"))
      (node (ref "U7") (pin "23") (pinfunction "SDI_S_D2_23") (pintype "bidirectional"))
      (node (ref "U9") (pin "23") (pinfunction "DIR_23") (pintype "input"))
    )
    (net (code "34") (name "/DIR_3") (class "Default")
      (node (ref "SST_EXP") (pin "9") (pinfunction "DIR_9") (pintype "input"))
      (node (ref "STPDIR") (pin "02") (pinfunction "02_02") (pintype "passive"))
      (node (ref "U7") (pin "19") (pinfunction "~{SCS3_D3}_19") (pintype "output"))
    )
    (net (code "35") (name "/DTR") (class "Default")
      (node (ref "C6") (pin "1") (pinfunction "1_1") (pintype "passive"))
      (node (ref "RN4") (pin "4") (pinfunction "4_4") (pintype "passive"))
      (node (ref "U2") (pin "13") (pinfunction "/_HWB_/_AIN6_/_T0_/_INT7)_PD7_13") (pintype "input"))
    )
    (net (code "36") (name "/D_N") (class "Default")
      (node (ref "RN2") (pin "1") (pinfunction "1_1") (pintype "passive"))
      (node (ref "RV1") (pin "2") (pinfunction "2_2") (pintype "passive"))
      (node (ref "U2") (pin "30") (pinfunction "D-_30") (pintype "bidirectional"))
    )
    (net (code "37") (name "/D_P") (class "Default")
      (node (ref "RN2") (pin "4") (pinfunction "4_4") (pintype "passive"))
      (node (ref "RV2") (pin "2") (pinfunction "2_2") (pintype "passive"))
      (node (ref "U2") (pin "29") (pinfunction "D+_29") (pintype "bidirectional"))
    )
    (net (code "38") (name "/ENN1") (class "Default")
      (node (ref "DBG") (pin "04") (pinfunction "04_04") (pintype "passive"))
      (node (ref "U1") (pin "38") (pinfunction "(OC5A)_PL3_38") (pintype "bidirectional"))
      (node (ref "U8") (pin "5") (pinfunction "ENN_5") (pintype "input"))
    )
    (net (code "39") (name "/ENN2") (class "Default")
      (node (ref "DBG") (pin "05") (pinfunction "05_05") (pintype "passive"))
      (node (ref "U1") (pin "39") (pinfunction "(OC5B)_PL4_39") (pintype "bidirectional"))
      (node (ref "U9") (pin "5") (pinfunction "ENN_5") (pintype "input"))
    )
    (net (code "40") (name "/ENN3") (class "Default")
      (node (ref "DBG") (pin "06") (pinfunction "06_06") (pintype "passive"))
      (node (ref "SST_EXP") (pin "16") (pinfunction "~{EN}_16") (pintype "input"))
      (node (ref "U1") (pin "40") (pinfunction "OC5C)_PL5_40") (pintype "bidirectional"))
    )
    (net (code "41") (name "/GATE") (class "Default")
      (node (ref "Q1") (pin "1") (pinfunction "G_1") (pintype "passive"))
      (node (ref "U5") (pin "1") (pinfunction "1OUT_1") (pintype "output"))
    )
    (net (code "42") (name "/HUBCFG1") (class "Default")
      (node (ref "RN6") (pin "4") (pinfunction "4_4") (pintype "passive"))
      (node (ref "U12") (pin "25") (pinfunction "HS_IND/CFG_SEL1_25") (pintype "bidirectional"))
    )
    (net (code "43") (name "/HUBDET") (class "Default")
      (node (ref "C42") (pin "2") (pinfunction "2_2") (pintype "passive"))
      (node (ref "RN6") (pin "2") (pinfunction "2_2") (pintype "passive"))
      (node (ref "RN6") (pin "3") (pinfunction "3_3") (pintype "passive"))
      (node (ref "U12") (pin "27") (pinfunction "VBUS_DET_27") (pintype "input"))
    )
    (net (code "44") (name "/HUBD_N") (class "Default")
      (node (ref "RN7") (pin "5") (pinfunction "5_5") (pintype "passive"))
      (node (ref "U13") (pin "6") (pinfunction "I/O1_6") (pintype "bidirectional"))
    )
    (net (code "45") (name "/HUBD_P") (class "Default")
      (node (ref "RN7") (pin "8") (pinfunction "8_8") (pintype "passive"))
      (node (ref "U13") (pin "4") (pinfunction "I/O2_4") (pintype "bidirectional"))
    )
    (net (code "46") (name "/HUBVBUS") (class "Default")
      (node (ref "RN6") (pin "7") (pinfunction "7_7") (pintype "passive"))
      (node (ref "U13") (pin "5") (pinfunction "VCC_5") (pintype "power_in"))
      (node (ref "USBPi") (pin "1") (pinfunction "VUSB_1") (pintype "passive"))
    )
    (net (code "47") (name "/I2CEN") (class "Default")
      (node (ref "DBG") (pin "07") (pinfunction "07_07") (pintype "passive"))
      (node (ref "R33") (pin "2") (pinfunction "2_2") (pintype "passive"))
      (node (ref "U1") (pin "41") (pinfunction "PL6_41") (pintype "bidirectional"))
      (node (ref "U11") (pin "6") (pinfunction "OE_6") (pintype "input"))
    )
    (net (code "48") (name "/INDEX_1") (class "Default")
      (node (ref "DBG") (pin "01") (pinfunction "01_01") (pintype "passive"))
      (node (ref "U1") (pin "35") (pinfunction "(ICP4)_PL0_35") (pintype "bidirectional"))
      (node (ref "U8") (pin "16") (pinfunction "INDEX_16") (pintype "output"))
    )
    (net (code "49") (name "/INDEX_2") (class "Default")
      (node (ref "DBG") (pin "02") (pinfunction "02_02") (pintype "passive"))
      (node (ref "U1") (pin "36") (pinfunction "(ICP5)_PL1_36") (pintype "bidirectional"))
      (node (ref "U9") (pin "16") (pinfunction "INDEX_16") (pintype "output"))
    )
    (net (code "50") (name "/INDEX_3") (class "Default")
      (node (ref "SST_CFG") (pin "04") (pinfunction "04_04") (pintype "passive"))
      (node (ref "SST_EXP") (pin "17") (pinfunction "INDEX_17") (pintype "output"))
    )
    (net (code "51") (name "/M8RXD") (class "Default")
      (node (ref "RN3") (pin "3") (pinfunction "3_3") (pintype "passive"))
      (node (ref "U2") (pin "9") (pinfunction "(TXD1_/_INT3)_PD3_9") (pintype "input"))
    )
    (net (code "52") (name "/M8TXD") (class "Default")
      (node (ref "RN3") (pin "4") (pinfunction "4_4") (pintype "passive"))
      (node (ref "U2") (pin "8") (pinfunction "(RXD1_/_AIN1_/_INT2)_PD2_8") (pintype "input"))
    )
    (net (code "53") (name "/MISO") (class "Default")
      (node (ref "ICSP2560") (pin "1") (pinfunction "1_1") (pintype "passive"))
      (node (ref "U1") (pin "22") (pinfunction "(MISO/PCINT3)_PB3_22") (pintype "bidirectional"))
      (node (ref "U7") (pin "14") (pinfunction "~{INT_SDO_C}_14") (pintype "output"))
    )
    (net (code "54") (name "/MISO16") (class "Default")
      (node (ref "ICSP16") (pin "1") (pinfunction "1_1") (pintype "passive"))
      (node (ref "U2") (pin "17") (pinfunction "PB3_(PDO_/_MISO_/_PCINT3)_17") (pintype "input"))
    )
    (net (code "55") (name "/MOSI") (class "Default")
      (node (ref "ICSP2560") (pin "4") (pinfunction "4_4") (pintype "passive"))
      (node (ref "U1") (pin "21") (pinfunction "(MOSI/PCINT2)_PB2_21") (pintype "bidirectional"))
      (node (ref "U7") (pin "11") (pinfunction "SDI_C_11") (pintype "input"))
    )
    (net (code "56") (name "/MOSI16") (class "Default")
      (node (ref "ICSP16") (pin "4") (pinfunction "4_4") (pintype "passive"))
      (node (ref "U2") (pin "16") (pinfunction "(PDI_/_MOSI_/_PCINT2)_PB2_16") (pintype "input"))
    )
    (net (code "57") (name "/MS1_X") (class "Default")
      (node (ref "U8") (pin "12") (pinfunction "MS1_AD0_12") (pintype "input"))
      (node (ref "XY_CFG") (pin "02") (pinfunction "02_02") (pintype "passive"))
    )
    (net (code "58") (name "/MS1_Y") (class "Default")
      (node (ref "U9") (pin "12") (pinfunction "MS1_AD0_12") (pintype "input"))
      (node (ref "XY_CFG") (pin "05") (pinfunction "05_05") (pintype "passive"))
    )
    (net (code "59") (name "/MS1_Z") (class "Default")
      (node (ref "SST_CFG") (pin "06") (pinfunction "06_06") (pintype "passive"))
      (node (ref "SST_EXP") (pin "15") (pinfunction "MS1_15") (pintype "input"))
    )
    (net (code "60") (name "/MS2_X") (class "Default")
      (node (ref "U8") (pin "14") (pinfunction "MS2_AD1_14") (pintype "input"))
      (node (ref "XY_CFG") (pin "01") (pinfunction "01_01") (pintype "passive"))
    )
    (net (code "61") (name "/MS2_Y") (class "Default")
      (node (ref "U9") (pin "14") (pinfunction "MS2_AD1_14") (pintype "input"))
      (node (ref "XY_CFG") (pin "06") (pinfunction "06_06") (pintype "passive"))
    )
    (net (code "62") (name "/MS2_Z") (class "Default")
      (node (ref "SST_CFG") (pin "07") (pinfunction "07_07") (pintype "passive"))
      (node (ref "SST_EXP") (pin "14") (pinfunction "MS2_14") (pintype "input"))
    )
    (net (code "63") (name "/MXT1") (class "Default")
      (node (ref "R3") (pin "2") (pinfunction "2_2") (pintype "passive"))
      (node (ref "U1") (pin "34") (pinfunction "XTAL1_34") (pintype "input"))
      (node (ref "Y2") (pin "3") (pinfunction "OUT_3") (pintype "output"))
    )
    (net (code "64") (name "/MXT2") (class "Default")
      (node (ref "R3") (pin "1") (pinfunction "1_1") (pintype "passive"))
      (node (ref "U1") (pin "33") (pinfunction "XTAL2_33") (pintype "output"))
      (node (ref "Y2") (pin "1") (pinfunction "IN_1") (pintype "input"))
    )
    (net (code "65") (name "/OA1_X") (class "Default")
      (node (ref "C52") (pin "2") (pinfunction "2_2") (pintype "passive"))
      (node (ref "MOT_X") (pin "4") (pinfunction "4_4") (pintype "passive"))
      (node (ref "U8") (pin "28") (pinfunction "OA1_28") (pintype "output"))
    )
    (net (code "66") (name "/OA1_Y") (class "Default")
      (node (ref "C56") (pin "2") (pinfunction "2_2") (pintype "passive"))
      (node (ref "MOT_Y") (pin "4") (pinfunction "4_4") (pintype "passive"))
      (node (ref "U9") (pin "28") (pinfunction "OA1_28") (pintype "output"))
    )
    (net (code "67") (name "/OA1_Z") (class "Default")
      (node (ref "MOTORZ") (pin "1") (pinfunction "1_1") (pintype "passive"))
      (node (ref "SST_EXP") (pin "4") (pinfunction "M1A_4") (pintype "output"))
    )
    (net (code "68") (name "/OA2_X") (class "Default")
      (node (ref "C53") (pin "2") (pinfunction "2_2") (pintype "passive"))
      (node (ref "MOT_X") (pin "3") (pinfunction "3_3") (pintype "passive"))
      (node (ref "U8") (pin "25") (pinfunction "OA2_25") (pintype "output"))
    )
    (net (code "69") (name "/OA2_Y") (class "Default")
      (node (ref "C57") (pin "2") (pinfunction "2_2") (pintype "passive"))
      (node (ref "MOT_Y") (pin "3") (pinfunction "3_3") (pintype "passive"))
      (node (ref "U9") (pin "25") (pinfunction "OA2_25") (pintype "output"))
    )
    (net (code "70") (name "/OA2_Z") (class "Default")
      (node (ref "MOTORZ") (pin "2") (pinfunction "2_2") (pintype "passive"))
      (node (ref "SST_EXP") (pin "5") (pinfunction "M2A_5") (pintype "output"))
    )
    (net (code "71") (name "/OB1_X") (class "Default")
      (node (ref "C54") (pin "2") (pinfunction "2_2") (pintype "passive"))
      (node (ref "MOT_X") (pin "2") (pinfunction "2_2") (pintype "passive"))
      (node (ref "U8") (pin "1") (pinfunction "OB1_1") (pintype "output"))
    )
    (net (code "72") (name "/OB1_Y") (class "Default")
      (node (ref "C58") (pin "2") (pinfunction "2_2") (pintype "passive"))
      (node (ref "MOT_Y") (pin "2") (pinfunction "2_2") (pintype "passive"))
      (node (ref "U9") (pin "1") (pinfunction "OB1_1") (pintype "output"))
    )
    (net (code "73") (name "/OB1_Z") (class "Default")
      (node (ref "MOTORZ") (pin "3") (pinfunction "3_3") (pintype "passive"))
      (node (ref "SST_EXP") (pin "3") (pinfunction "M1B_3") (pintype "output"))
    )
    (net (code "74") (name "/OB2_X") (class "Default")
      (node (ref "C55") (pin "2") (pinfunction "2_2") (pintype "passive"))
      (node (ref "MOT_X") (pin "1") (pinfunction "1_1") (pintype "passive"))
      (node (ref "U8") (pin "4") (pinfunction "OB2_4") (pintype "output"))
    )
    (net (code "75") (name "/OB2_Y") (class "Default")
      (node (ref "C59") (pin "2") (pinfunction "2_2") (pintype "passive"))
      (node (ref "MOT_Y") (pin "1") (pinfunction "1_1") (pintype "passive"))
      (node (ref "U9") (pin "4") (pinfunction "OB2_4") (pintype "output"))
    )
    (net (code "76") (name "/OB2_Z") (class "Default")
      (node (ref "MOTORZ") (pin "4") (pinfunction "4_4") (pintype "passive"))
      (node (ref "SST_EXP") (pin "6") (pinfunction "M2B_6") (pintype "output"))
    )
    (net (code "77") (name "/OP2OUT") (class "Default")
      (node (ref "R8") (pin "2") (pinfunction "2_2") (pintype "passive"))
      (node (ref "U5") (pin "6") (pinfunction "2IN-_6") (pintype "input"))
      (node (ref "U5") (pin "7") (pinfunction "2OUT_7") (pintype "output"))
    )
    (net (code "78") (name "/OP3OUT") (class "Default")
      (node (ref "R9") (pin "2") (pinfunction "2_2") (pintype "passive"))
      (node (ref "U5") (pin "8") (pinfunction "3OUT_8") (pintype "output"))
      (node (ref "U5") (pin "9") (pinfunction "3IN-_9") (pintype "input"))
    )
    (net (code "79") (name "/OP4OUT") (class "Default")
      (node (ref "R42") (pin "2") (pinfunction "2_2") (pintype "passive"))
      (node (ref "U5") (pin "13") (pinfunction "4IN-_13") (pintype "input"))
      (node (ref "U5") (pin "14") (pinfunction "4OUT_14") (pintype "output"))
    )
    (net (code "80") (name "/PDN_3") (class "Default")
      (node (ref "SST_CFG") (pin "02") (pinfunction "02_02") (pintype "passive"))
      (node (ref "SST_EXP") (pin "11") (pinfunction "PDN_11") (pintype "bidirectional"))
    )
    (net (code "81") (name "/PE0RX0") (class "Default")
      (node (ref "RN3") (pin "6") (pinfunction "6_6") (pintype "passive"))
      (node (ref "U1") (pin "2") (pinfunction "(RXD0/PCINT8)_PE0_2") (pintype "bidirectional"))
    )
    (net (code "82") (name "/PE1TX0") (class "Default")
      (node (ref "RN3") (pin "5") (pinfunction "5_5") (pintype "passive"))
      (node (ref "U1") (pin "3") (pinfunction "(TXD0)_PE1_3") (pintype "bidirectional"))
    )
    (net (code "83") (name "/PORT1_N") (class "Default")
      (node (ref "U12") (pin "1") (pinfunction "USBDM_DN1/PRT_DIS_M1_1") (pintype "bidirectional"))
      (node (ref "USBOUT2") (pin "6") (pinfunction "D1-_6") (pintype "passive"))
    )
    (net (code "84") (name "/PORT1_P") (class "Default")
      (node (ref "U12") (pin "2") (pinfunction "USBDP_DN1/PRT_DIS_P1_2") (pintype "bidirectional"))
      (node (ref "USBOUT2") (pin "7") (pinfunction "D1+_7") (pintype "passive"))
    )
    (net (code "85") (name "/PORT2_N") (class "Default")
      (node (ref "U12") (pin "3") (pinfunction "USBDM_DN2/PRT_DIS_M2_3") (pintype "bidirectional"))
      (node (ref "USBOUT2") (pin "2") (pinfunction "D2-_2") (pintype "passive"))
    )
    (net (code "86") (name "/PORT2_P") (class "Default")
      (node (ref "U12") (pin "4") (pinfunction "USBDP_DN2/PRT_DIS_P2_4") (pintype "bidirectional"))
      (node (ref "USBOUT2") (pin "3") (pinfunction "D2+_3") (pintype "passive"))
    )
    (net (code "87") (name "/PORT3_N") (class "Default")
      (node (ref "U12") (pin "6") (pinfunction "USBDM_DN3/PRT_DIS_M3_6") (pintype "bidirectional"))
      (node (ref "USBOUT1") (pin "6") (pinfunction "D1-_6") (pintype "passive"))
    )
    (net (code "88") (name "/PORT3_P") (class "Default")
      (node (ref "U12") (pin "7") (pinfunction "USBDP_DN3/PRT_DIS_P3_7") (pintype "bidirectional"))
      (node (ref "USBOUT1") (pin "7") (pinfunction "D1+_7") (pintype "passive"))
    )
    (net (code "89") (name "/PORT4_N") (class "Default")
      (node (ref "U12") (pin "8") (pinfunction "USBDM_DN4/PRT_DIS_M4_8") (pintype "bidirectional"))
      (node (ref "USBOUT1") (pin "2") (pinfunction "D2-_2") (pintype "passive"))
    )
    (net (code "90") (name "/PORT4_P") (class "Default")
      (node (ref "U12") (pin "9") (pinfunction "USBDP_DN4/PRT_DIS_P4_9") (pintype "bidirectional"))
      (node (ref "USBOUT1") (pin "3") (pinfunction "D2+_3") (pintype "passive"))
    )
    (net (code "91") (name "/PORTPWR1") (class "Default")
      (node (ref "Q2") (pin "1") (pinfunction "G_1") (pintype "passive"))
      (node (ref "RN8") (pin "5") (pinfunction "5_5") (pintype "passive"))
      (node (ref "U12") (pin "12") (pinfunction "PRTPWR1/BC_EN1_12") (pintype "bidirectional"))
    )
    (net (code "92") (name "/PORTPWR2") (class "Default")
      (node (ref "Q3") (pin "1") (pinfunction "G_1") (pintype "passive"))
      (node (ref "RN8") (pin "8") (pinfunction "8_8") (pintype "passive"))
      (node (ref "U12") (pin "16") (pinfunction "PRTPWR2/BC_EN2_16") (pintype "bidirectional"))
    )
    (net (code "93") (name "/PORTPWR3") (class "Default")
      (node (ref "Q4") (pin "1") (pinfunction "G_1") (pintype "passive"))
      (node (ref "RN8") (pin "7") (pinfunction "7_7") (pintype "passive"))
      (node (ref "U12") (pin "18") (pinfunction "PRTPWR3/BC_EN3_18") (pintype "bidirectional"))
    )
    (net (code "94") (name "/PORTPWR4") (class "Default")
      (node (ref "Q5") (pin "1") (pinfunction "G_1") (pintype "passive"))
      (node (ref "RN8") (pin "6") (pinfunction "6_6") (pintype "passive"))
      (node (ref "U12") (pin "20") (pinfunction "PRTPWR4/BC_EN4_20") (pintype "bidirectional"))
    )
    (net (code "95") (name "/POSCMP") (class "Default")
      (node (ref "DBG") (pin "03") (pinfunction "03_03") (pintype "passive"))
      (node (ref "U1") (pin "37") (pinfunction "(T5)_PL2_37") (pintype "bidirectional"))
      (node (ref "U7") (pin "1") (pinfunction "POSCMP_1") (pintype "bidirectional"))
    )
    (net (code "96") (name "/PWRGUD") (class "Default")
      (node (ref "DBG") (pin "08") (pinfunction "08_08") (pintype "passive"))
      (node (ref "PSU") (pin "5") (pinfunction "5_5") (pintype "passive"))
      (node (ref "U1") (pin "42") (pinfunction "PL7_42") (pintype "bidirectional"))
      (node (ref "U5") (pin "12") (pinfunction "4IN+_12") (pintype "input"))
    )
    (net (code "97") (name "/PWRIN") (class "Default")
      (node (ref "D15") (pin "A") (pinfunction "A_A") (pintype "passive"))
      (node (ref "D2") (pin "A") (pinfunction "A_A") (pintype "passive"))
      (node (ref "Power") (pin "1") (pinfunction "1_1") (pintype "passive"))
    )
    (net (code "98") (name "/PWRLIGHT") (class "Default")
      (node (ref "D5") (pin "POS") (pinfunction "POS_POS") (pintype "passive"))
      (node (ref "RN4") (pin "1") (pinfunction "1_1") (pintype "passive"))
    )
    (net (code "99") (name "/Pi5V") (class "Default")
      (node (ref "CD5") (pin "1") (pinfunction "1_1") (pintype "passive"))
      (node (ref "CD6") (pin "1") (pinfunction "1_1") (pintype "passive"))
      (node (ref "CD7") (pin "1") (pinfunction "1_1") (pintype "passive"))
      (node (ref "CD8") (pin "1") (pinfunction "1_1") (pintype "passive"))
      (node (ref "D3") (pin "A") (pinfunction "A_A") (pintype "passive"))
      (node (ref "D9") (pin "A") (pinfunction "A_A") (pintype "passive"))
      (node (ref "DCFAN") (pin "1") (pinfunction "1_1") (pintype "passive"))
      (node (ref "DCFAN") (pin "4") (pinfunction "4_4") (pintype "passive"))
      (node (ref "PC3") (pin "1") (pinfunction "1_1") (pintype "passive"))
      (node (ref "PSU") (pin "4") (pinfunction "4_4") (pintype "passive"))
      (node (ref "Q2") (pin "2") (pinfunction "S_2") (pintype "passive"))
      (node (ref "Q3") (pin "2") (pinfunction "S_2") (pintype "passive"))
      (node (ref "Q4") (pin "2") (pinfunction "S_2") (pintype "passive"))
      (node (ref "Q5") (pin "2") (pinfunction "S_2") (pintype "passive"))
      (node (ref "RN8") (pin "1") (pinfunction "1_1") (pintype "passive"))
      (node (ref "RN8") (pin "2") (pinfunction "2_2") (pintype "passive"))
      (node (ref "RN8") (pin "3") (pinfunction "3_3") (pintype "passive"))
      (node (ref "RN8") (pin "4") (pinfunction "4_4") (pintype "passive"))
      (node (ref "RPi") (pin "2") (pinfunction "5V_2") (pintype "power_in"))
      (node (ref "RPi") (pin "4") (pinfunction "5V_4") (pintype "power_in"))
      (node (ref "U3") (pin "4") (pinfunction "OUTPUT_4_4") (pintype "output"))
    )
    (net (code "100") (name "/Pi_ACK") (class "Default")
      (node (ref "R14") (pin "1") (pinfunction "1_1") (pintype "passive"))
      (node (ref "RPi") (pin "40") (pinfunction "GPIO21_40") (pintype "bidirectional"))
      (node (ref "U17") (pin "4") (pinfunction "A3_4") (pintype "bidirectional"))
    )
    (net (code "101") (name "/Pi_ACT") (class "Default")
      (node (ref "ACTLED") (pin "01") (pinfunction "01_01") (pintype "passive"))
      (node (ref "R31") (pin "2") (pinfunction "2_2") (pintype "passive"))
      (node (ref "RPi") (pin "7") (pinfunction "GPIO4/GPIO_GCKL_7") (pintype "bidirectional"))
    )
    (net (code "102") (name "/Pi_ATN") (class "Default")
      (node (ref "R13") (pin "1") (pinfunction "1_1") (pintype "passive"))
      (node (ref "RPi") (pin "35") (pinfunction "GPIO19_35") (pintype "bidirectional"))
      (node (ref "U17") (pin "5") (pinfunction "A4_5") (pintype "bidirectional"))
    )
    (net (code "103") (name "/Pi_BSY") (class "Default")
      (node (ref "R17") (pin "1") (pinfunction "1_1") (pintype "passive"))
      (node (ref "RPi") (pin "37") (pinfunction "GPIO26_37") (pintype "bidirectional"))
      (node (ref "U15") (pin "6") (pinfunction "A5_6") (pintype "bidirectional"))
    )
    (net (code "104") (name "/Pi_CD") (class "Default")
      (node (ref "R19") (pin "1") (pinfunction "1_1") (pintype "passive"))
      (node (ref "RPi") (pin "18") (pinfunction "GPIO24/GPIO_GEN5_18") (pintype "bidirectional"))
      (node (ref "U15") (pin "4") (pinfunction "A3_4") (pintype "bidirectional"))
    )
    (net (code "105") (name "/Pi_D0") (class "Default")
      (node (ref "R29") (pin "1") (pinfunction "1_1") (pintype "passive"))
      (node (ref "RPi") (pin "19") (pinfunction "GPIO10/SPI_MOSI_19") (pintype "bidirectional"))
      (node (ref "U14") (pin "16") (pinfunction "B3_16") (pintype "bidirectional"))
    )
    (net (code "106") (name "/Pi_D1") (class "Default")
      (node (ref "R28") (pin "1") (pinfunction "1_1") (pintype "passive"))
      (node (ref "RPi") (pin "23") (pinfunction "GPIO11/SPI_SCLK_23") (pintype "bidirectional"))
      (node (ref "U14") (pin "17") (pinfunction "B2_17") (pintype "bidirectional"))
    )
    (net (code "107") (name "/Pi_D2") (class "Default")
      (node (ref "R27") (pin "1") (pinfunction "1_1") (pintype "passive"))
      (node (ref "RPi") (pin "32") (pinfunction "GPIO12_32") (pintype "bidirectional"))
      (node (ref "U14") (pin "18") (pinfunction "B1_18") (pintype "bidirectional"))
    )
    (net (code "108") (name "/Pi_D3") (class "Default")
      (node (ref "R26") (pin "1") (pinfunction "1_1") (pintype "passive"))
      (node (ref "RPi") (pin "33") (pinfunction "GPIO13_33") (pintype "bidirectional"))
      (node (ref "U16") (pin "14") (pinfunction "B5_14") (pintype "bidirectional"))
    )
    (net (code "109") (name "/Pi_D4") (class "Default")
      (node (ref "R25") (pin "1") (pinfunction "1_1") (pintype "passive"))
      (node (ref "RPi") (pin "8") (pinfunction "GPIO14/TXD0_8") (pintype "bidirectional"))
      (node (ref "U16") (pin "15") (pinfunction "B4_15") (pintype "bidirectional"))
    )
    (net (code "110") (name "/Pi_D5") (class "Default")
      (node (ref "R24") (pin "1") (pinfunction "1_1") (pintype "passive"))
      (node (ref "RPi") (pin "10") (pinfunction "GPIO15/RXD0_10") (pintype "bidirectional"))
      (node (ref "U16") (pin "16") (pinfunction "B3_16") (pintype "bidirectional"))
    )
    (net (code "111") (name "/Pi_D6") (class "Default")
      (node (ref "R23") (pin "1") (pinfunction "1_1") (pintype "passive"))
      (node (ref "RPi") (pin "36") (pinfunction "GPIO16_36") (pintype "bidirectional"))
      (node (ref "U16") (pin "17") (pinfunction "B2_17") (pintype "bidirectional"))
    )
    (net (code "112") (name "/Pi_D7") (class "Default")
      (node (ref "R22") (pin "1") (pinfunction "1_1") (pintype "passive"))
      (node (ref "RPi") (pin "11") (pinfunction "GPIO17/GPIO_GEN0_11") (pintype "bidirectional"))
      (node (ref "U16") (pin "18") (pinfunction "B1_18") (pintype "bidirectional"))
    )
    (net (code "113") (name "/Pi_DP") (class "Default")
      (node (ref "R30") (pin "1") (pinfunction "1_1") (pintype "passive"))
      (node (ref "RPi") (pin "12") (pinfunction "GPIO18/GPIO_GEN1_12") (pintype "bidirectional"))
      (node (ref "U14") (pin "15") (pinfunction "B4_15") (pintype "bidirectional"))
    )
    (net (code "114") (name "/Pi_DTD") (class "Default")
      (node (ref "RPi") (pin "24") (pinfunction "GPIO8/~{SPI_CE0}_24") (pintype "bidirectional"))
      (node (ref "U14") (pin "1") (pinfunction "DIR_1") (pintype "input"))
      (node (ref "U16") (pin "1") (pinfunction "DIR_1") (pintype "input"))
    )
    (net (code "115") (name "/Pi_GPIO0") (class "Default")
      (node (ref "PiGPIO") (pin "1") (pinfunction "1_1") (pintype "passive"))
      (node (ref "RPi") (pin "27") (pinfunction "ID_SD_27") (pintype "bidirectional"))
    )
    (net (code "116") (name "/Pi_GPIO1") (class "Default")
      (node (ref "PiGPIO") (pin "3") (pinfunction "3_3") (pintype "passive"))
      (node (ref "RPi") (pin "28") (pinfunction "ID_SC_28") (pintype "bidirectional"))
    )
    (net (code "117") (name "/Pi_GPIO9") (class "Default")
      (node (ref "PiGPIO") (pin "5") (pinfunction "5_5") (pintype "passive"))
      (node (ref "RPi") (pin "21") (pinfunction "GPIO9/SPI_MISO_21") (pintype "bidirectional"))
    )
    (net (code "118") (name "/Pi_IND") (class "Default")
      (node (ref "RPi") (pin "31") (pinfunction "GPIO6_31") (pintype "bidirectional"))
      (node (ref "U17") (pin "1") (pinfunction "DIR_1") (pintype "input"))
    )
    (net (code "119") (name "/Pi_IO") (class "Default")
      (node (ref "R21") (pin "1") (pinfunction "1_1") (pintype "passive"))
      (node (ref "RPi") (pin "22") (pinfunction "GPIO25/GPIO_GEN6_22") (pintype "bidirectional"))
      (node (ref "U15") (pin "2") (pinfunction "A1_2") (pintype "bidirectional"))
    )
    (net (code "120") (name "/Pi_MSG") (class "Default")
      (node (ref "R18") (pin "1") (pinfunction "1_1") (pintype "passive"))
      (node (ref "RPi") (pin "16") (pinfunction "GPIO23/GPIO_GEN4_16") (pintype "bidirectional"))
      (node (ref "U15") (pin "5") (pinfunction "A4_5") (pintype "bidirectional"))
    )
    (net (code "121") (name "/Pi_REQ") (class "Default")
      (node (ref "R20") (pin "1") (pinfunction "1_1") (pintype "passive"))
      (node (ref "RPi") (pin "15") (pinfunction "GPIO22/GPIO_GEN3_15") (pintype "bidirectional"))
      (node (ref "U15") (pin "3") (pinfunction "A2_3") (pintype "bidirectional"))
    )
    (net (code "122") (name "/Pi_RST") (class "Default")
      (node (ref "R15") (pin "1") (pinfunction "1_1") (pintype "passive"))
      (node (ref "RPi") (pin "38") (pinfunction "GPIO20_38") (pintype "bidirectional"))
      (node (ref "U17") (pin "3") (pinfunction "A2_3") (pintype "bidirectional"))
    )
    (net (code "123") (name "/Pi_SCL") (class "Default")
      (node (ref "PiI2C") (pin "02") (pinfunction "02_02") (pintype "passive"))
      (node (ref "RPi") (pin "5") (pinfunction "GPIO3/SCL1_5") (pintype "bidirectional"))
      (node (ref "U11") (pin "4") (pinfunction "A2_4") (pintype "bidirectional"))
    )
    (net (code "124") (name "/Pi_SDA") (class "Default")
      (node (ref "PiI2C") (pin "01") (pinfunction "01_01") (pintype "passive"))
      (node (ref "RPi") (pin "3") (pinfunction "GPIO2/SDA1_3") (pintype "bidirectional"))
      (node (ref "U11") (pin "5") (pinfunction "A1_5") (pintype "bidirectional"))
    )
    (net (code "125") (name "/Pi_SEL") (class "Default")
      (node (ref "R16") (pin "1") (pinfunction "1_1") (pintype "passive"))
      (node (ref "RPi") (pin "13") (pinfunction "GPIO27/GPIO_GEN2_13") (pintype "bidirectional"))
      (node (ref "U17") (pin "2") (pinfunction "A1_2") (pintype "bidirectional"))
    )
    (net (code "126") (name "/Pi_TAD") (class "Default")
      (node (ref "RPi") (pin "26") (pinfunction "GPIO7/~{SPI_CE1}_26") (pintype "bidirectional"))
      (node (ref "U15") (pin "1") (pinfunction "DIR_1") (pintype "input"))
    )
    (net (code "127") (name "/REF3") (class "Default")
      (node (ref "R39") (pin "1") (pinfunction "1_1") (pintype "passive"))
      (node (ref "U7") (pin "4") (pinfunction "REF3_4") (pintype "input"))
    )
    (net (code "128") (name "/REFR1") (class "Default")
      (node (ref "R_REF") (pin "1") (pinfunction "1_1") (pintype "passive"))
      (node (ref "U7") (pin "24") (pinfunction "REFR1_24") (pintype "input"))
    )
    (net (code "129") (name "/REFR2") (class "Default")
      (node (ref "R_REF") (pin "4") (pinfunction "4_4") (pintype "passive"))
      (node (ref "U7") (pin "13") (pinfunction "REFR2_13") (pintype "input"))
    )
    (net (code "130") (name "/RESET") (class "Default")
      (node (ref "C15") (pin "2") (pinfunction "2_2") (pintype "passive"))
      (node (ref "C6") (pin "2") (pinfunction "2_2") (pintype "passive"))
      (node (ref "D6") (pin "A") (pinfunction "A_A") (pintype "passive"))
      (node (ref "ICSP2560") (pin "5") (pinfunction "5_5") (pintype "passive"))
      (node (ref "RESET-EN") (pin "1") (pinfunction "1_1") (pintype "passive"))
      (node (ref "RESET-EN") (pin "2") (pinfunction "2_2") (pintype "passive"))
      (node (ref "RN1") (pin "5") (pinfunction "5_5") (pintype "passive"))
      (node (ref "S1") (pin "1") (pinfunction "1_1") (pintype "passive"))
      (node (ref "S1") (pin "2") (pinfunction "2_2") (pintype "passive"))
      (node (ref "U1") (pin "30") (pinfunction "~{RESET}_30") (pintype "input"))
    )
    (net (code "131") (name "/RST16U2") (class "Default")
      (node (ref "D1") (pin "A") (pinfunction "A_A") (pintype "passive"))
      (node (ref "ICSP16") (pin "5") (pinfunction "5_5") (pintype "passive"))
      (node (ref "RN1") (pin "8") (pinfunction "8_8") (pintype "passive"))
      (node (ref "U2") (pin "24") (pinfunction "~{RESET_(PC1_/_DW)}_24") (pintype "input"))
    )
    (net (code "132") (name "/RXD_N") (class "Default")
      (node (ref "D13") (pin "2") (pinfunction "I/O2_2") (pintype "bidirectional"))
      (node (ref "R36") (pin "1") (pinfunction "1_1") (pintype "passive"))
      (node (ref "R38") (pin "2") (pinfunction "2_2") (pintype "passive"))
      (node (ref "RS422 1") (pin "5") (pinfunction "5_5") (pintype "passive"))
    )
    (net (code "133") (name "/RXD_P") (class "Default")
      (node (ref "D13") (pin "1") (pinfunction "I/O1_1") (pintype "bidirectional"))
      (node (ref "R36") (pin "2") (pinfunction "2_2") (pintype "passive"))
      (node (ref "R37") (pin "2") (pinfunction "2_2") (pintype "passive"))
      (node (ref "RS422 1") (pin "8") (pinfunction "8_8") (pintype "passive"))
    )
    (net (code "134") (name "/RXL") (class "Default")
      (node (ref "RX") (pin "1") (pinfunction "K2_1") (pintype "passive"))
      (node (ref "U2") (pin "10") (pinfunction "(INT5/_AIN3)_PD4_10") (pintype "input"))
    )
    (net (code "135") (name "/RXLR") (class "Default")
      (node (ref "RN3") (pin "2") (pinfunction "2_2") (pintype "passive"))
      (node (ref "RX") (pin "2") (pinfunction "A2_2") (pintype "passive"))
    )
    (net (code "136") (name "/RX_1") (class "Default")
      (node (ref "R4") (pin "1") (pinfunction "1_1") (pintype "passive"))
      (node (ref "U1") (pin "46") (pinfunction "(TXD1/INT3)_PD3_46") (pintype "bidirectional"))
      (node (ref "U8") (pin "18") (pinfunction "PDN_UART_18") (pintype "bidirectional"))
    )
    (net (code "137") (name "/RX_2") (class "Default")
      (node (ref "PH") (pin "02") (pinfunction "02_02") (pintype "passive"))
      (node (ref "R5") (pin "1") (pinfunction "1_1") (pintype "passive"))
      (node (ref "U1") (pin "13") (pinfunction "(TXD2)_PH1_13") (pintype "bidirectional"))
      (node (ref "U9") (pin "18") (pinfunction "PDN_UART_18") (pintype "bidirectional"))
    )
    (net (code "138") (name "/RX_3") (class "Default")
      (node (ref "RX_AT") (pin "1") (pinfunction "K2_1") (pintype "passive"))
      (node (ref "U1") (pin "63") (pinfunction "PJ0_(RXD3/PCINT9)_63") (pintype "bidirectional"))
      (node (ref "U18") (pin "4") (pinfunction "RO_4") (pintype "output"))
      (node (ref "UART3") (pin "01") (pinfunction "01_01") (pintype "passive"))
    )
    (net (code "139") (name "/SCK") (class "Default")
      (node (ref "ICSP2560") (pin "3") (pinfunction "3_3") (pintype "passive"))
      (node (ref "U1") (pin "20") (pinfunction "(SCK/PCINT1)_PB1_20") (pintype "bidirectional"))
      (node (ref "U7") (pin "10") (pinfunction "SCK_C_10") (pintype "input"))
    )
    (net (code "140") (name "/SCK16") (class "Default")
      (node (ref "ICSP16") (pin "3") (pinfunction "3_3") (pintype "passive"))
      (node (ref "U2") (pin "15") (pinfunction "(SCLK_/_PCINT1)_PB1_15") (pintype "input"))
    )
    (net (code "141") (name "/SCL") (class "Default")
      (node (ref "I2C") (pin "02") (pinfunction "02_02") (pintype "passive"))
      (node (ref "U1") (pin "43") (pinfunction "(SCL/INT0)_PD0_43") (pintype "bidirectional"))
      (node (ref "U11") (pin "1") (pinfunction "B2_1") (pintype "bidirectional"))
    )
    (net (code "142") (name "/SDA") (class "Default")
      (node (ref "I2C") (pin "01") (pinfunction "01_01") (pintype "passive"))
      (node (ref "U1") (pin "44") (pinfunction "(SDA/INT1)_PD1_44") (pintype "bidirectional"))
      (node (ref "U11") (pin "8") (pinfunction "B1_8") (pintype "bidirectional"))
    )
    (net (code "143") (name "/SPRDX") (class "Default")
      (node (ref "U8") (pin "10") (pinfunction "SPREAD_10") (pintype "input"))
      (node (ref "XY_CFG") (pin "03") (pinfunction "03_03") (pintype "passive"))
    )
    (net (code "144") (name "/SPRDY") (class "Default")
      (node (ref "U9") (pin "10") (pinfunction "SPREAD_10") (pintype "input"))
      (node (ref "XY_CFG") (pin "04") (pinfunction "04_04") (pintype "passive"))
    )
    (net (code "145") (name "/SPRDZ") (class "Default")
      (node (ref "SST_CFG") (pin "08") (pinfunction "08_08") (pintype "passive"))
      (node (ref "SST_EXP") (pin "13") (pinfunction "SPRD_13") (pintype "input"))
    )
    (net (code "146") (name "/SS") (class "Default")
      (node (ref "U1") (pin "19") (pinfunction "(~SS/PCINT0)_PB0_19") (pintype "bidirectional"))
      (node (ref "U7") (pin "9") (pinfunction "~{SCS_C}_9") (pintype "input"))
    )
    (net (code "147") (name "/STP_1") (class "Default")
      (node (ref "STPDIR") (pin "04") (pinfunction "04_04") (pintype "passive"))
      (node (ref "U7") (pin "15") (pinfunction "SDO_S_S1_15") (pintype "output"))
      (node (ref "U8") (pin "20") (pinfunction "STEP_20") (pintype "input"))
    )
    (net (code "148") (name "/STP_2") (class "Default")
      (node (ref "STPDIR") (pin "07") (pinfunction "07_07") (pintype "passive"))
      (node (ref "U7") (pin "17") (pinfunction "~{SCS_S_S2}_17") (pintype "output"))
      (node (ref "U9") (pin "20") (pinfunction "STEP_20") (pintype "input"))
    )
    (net (code "149") (name "/STP_3") (class "Default")
      (node (ref "SST_EXP") (pin "10") (pinfunction "STEP_10") (pintype "input"))
      (node (ref "STPDIR") (pin "03") (pinfunction "03_03") (pintype "passive"))
      (node (ref "U7") (pin "18") (pinfunction "~{SCS2_S3}_18") (pintype "output"))
    )
    (net (code "150") (name "/SYSCLK") (class "Default")
      (node (ref "U1") (pin "9") (pinfunction "(CLKO/ICP3/INT7)_PE7_9") (pintype "bidirectional"))
      (node (ref "U7") (pin "7") (pinfunction "CLK_7") (pintype "input"))
      (node (ref "U8") (pin "17") (pinfunction "CLK_17") (pintype "input"))
      (node (ref "U9") (pin "17") (pinfunction "CLK_17") (pintype "input"))
    )
    (net (code "151") (name "/TERMPWR") (class "Default")
      (node (ref "F2") (pin "2") (pinfunction "2_2") (pintype "passive"))
      (node (ref "SCSI") (pin "25") (pinfunction "25_25") (pintype "passive"))
    )
    (net (code "152") (name "/TERM_5V") (class "Default")
      (node (ref "RN10") (pin "1") (pinfunction "1_1") (pintype "passive"))
      (node (ref "RN9") (pin "1") (pinfunction "1_1") (pintype "passive"))
      (node (ref "TERM_PWR") (pin "1B") (pinfunction "NO1_1B") (pintype "passive"))
    )
    (net (code "153") (name "/TERM_GND") (class "Default")
      (node (ref "RN11") (pin "1") (pinfunction "1_1") (pintype "passive"))
      (node (ref "RN12") (pin "1") (pinfunction "1_1") (pintype "passive"))
      (node (ref "TERM_PWR") (pin "2B") (pinfunction "NO2_2B") (pintype "passive"))
    )
    (net (code "154") (name "/TXD_N") (class "Default")
      (node (ref "D12") (pin "2") (pinfunction "I/O2_2") (pintype "bidirectional"))
      (node (ref "R41") (pin "2") (pinfunction "2_2") (pintype "passive"))
      (node (ref "RS422 1") (pin "3") (pinfunction "3_3") (pintype "passive"))
    )
    (net (code "155") (name "/TXD_P") (class "Default")
      (node (ref "D12") (pin "1") (pinfunction "I/O1_1") (pintype "bidirectional"))
      (node (ref "R40") (pin "2") (pinfunction "2_2") (pintype "passive"))
      (node (ref "RS422 1") (pin "6") (pinfunction "6_6") (pintype "passive"))
    )
    (net (code "156") (name "/TXL") (class "Default")
      (node (ref "TX") (pin "1") (pinfunction "K2_1") (pintype "passive"))
      (node (ref "U2") (pin "11") (pinfunction "(XCK_AIN4_/_PCINT12)_PD5_11") (pintype "input"))
    )
    (net (code "157") (name "/TXLR") (class "Default")
      (node (ref "RN3") (pin "1") (pinfunction "1_1") (pintype "passive"))
      (node (ref "TX") (pin "2") (pinfunction "A2_2") (pintype "passive"))
    )
    (net (code "158") (name "/TX_1") (class "Default")
      (node (ref "R4") (pin "2") (pinfunction "2_2") (pintype "passive"))
      (node (ref "U1") (pin "45") (pinfunction "(RXD1/INT2)_PD2_45") (pintype "bidirectional"))
    )
    (net (code "159") (name "/TX_2") (class "Default")
      (node (ref "PH") (pin "01") (pinfunction "01_01") (pintype "passive"))
      (node (ref "R5") (pin "2") (pinfunction "2_2") (pintype "passive"))
      (node (ref "U1") (pin "12") (pinfunction "(RXD2)_PH0_12") (pintype "bidirectional"))
    )
    (net (code "160") (name "/TX_3") (class "Default")
      (node (ref "TX_AT") (pin "1") (pinfunction "K2_1") (pintype "passive"))
      (node (ref "U1") (pin "64") (pinfunction "PJ1_(TXD3/PCINT10)_64") (pintype "bidirectional"))
      (node (ref "U18") (pin "5") (pinfunction "DI_5") (pintype "input"))
      (node (ref "UART3") (pin "02") (pinfunction "02_02") (pintype "passive"))
    )
    (net (code "161") (name "/UART_3") (class "Default")
      (node (ref "SST_CFG") (pin "03") (pinfunction "03_03") (pintype "passive"))
      (node (ref "SST_EXP") (pin "12") (pinfunction "UART_12") (pintype "bidirectional"))
    )
    (net (code "162") (name "/UD_N") (class "Default")
      (node (ref "RN2") (pin "8") (pinfunction "8_8") (pintype "passive"))
      (node (ref "USB") (pin "2") (pinfunction "D-_2") (pintype "bidirectional"))
    )
    (net (code "163") (name "/UD_P") (class "Default")
      (node (ref "RN2") (pin "5") (pinfunction "5_5") (pintype "passive"))
      (node (ref "USB") (pin "3") (pinfunction "D+_3") (pintype "bidirectional"))
    )
    (net (code "164") (name "/UGND") (class "Default")
      (node (ref "C5") (pin "2") (pinfunction "2_2") (pintype "passive"))
      (node (ref "FL1") (pin "1") (pinfunction "1_1") (pintype "passive"))
      (node (ref "GROUND") (pin "1") (pinfunction "1_1") (pintype "passive"))
      (node (ref "U2") (pin "28") (pinfunction "UGND_28") (pintype "power_in"))
      (node (ref "USB") (pin "4") (pinfunction "GND_4") (pintype "power_in"))
    )
    (net (code "165") (name "/UPi_N") (class "Default")
      (node (ref "U13") (pin "1") (pinfunction "I/O1_1") (pintype "bidirectional"))
      (node (ref "USBPi") (pin "2") (pinfunction "D-_2") (pintype "passive"))
    )
    (net (code "166") (name "/UPi_P") (class "Default")
      (node (ref "U13") (pin "3") (pinfunction "I/O2_3") (pintype "bidirectional"))
      (node (ref "USBPi") (pin "3") (pinfunction "D+_3") (pintype "passive"))
    )
    (net (code "167") (name "/USBSHIELD") (class "Default")
      (node (ref "FL1") (pin "2") (pinfunction "2_2") (pintype "passive"))
      (node (ref "RV1") (pin "1") (pinfunction "1_1") (pintype "passive"))
      (node (ref "RV2") (pin "1") (pinfunction "1_1") (pintype "passive"))
      (node (ref "USB") (pin "S1") (pinfunction "SHIELD_S1") (pintype "power_in"))
      (node (ref "USB") (pin "S2") (pinfunction "SHIELD_S2") (pintype "power_in"))
    )
    (net (code "168") (name "/USBVCC") (class "Default")
      (node (ref "C4") (pin "1") (pinfunction "1_1") (pintype "passive"))
      (node (ref "F1") (pin "1") (pinfunction "1_1") (pintype "passive"))
      (node (ref "Q1") (pin "3") (pinfunction "D_3") (pintype "passive"))
      (node (ref "U2") (pin "31") (pinfunction "UVCC_31") (pintype "power_in"))
    )
    (net (code "169") (name "/VIN") (class "Default")
      (node (ref "D2") (pin "C") (pinfunction "K_C") (pintype "passive"))
      (node (ref "D3") (pin "C") (pinfunction "K_C") (pintype "passive"))
      (node (ref "D4") (pin "C") (pinfunction "K_C") (pintype "passive"))
      (node (ref "PC1") (pin "1") (pinfunction "1_1") (pintype "passive"))
      (node (ref "PC2") (pin "1") (pinfunction "1_1") (pintype "passive"))
      (node (ref "PC4") (pin "1") (pinfunction "1_1") (pintype "passive"))
      (node (ref "PC5") (pin "1") (pinfunction "1_1") (pintype "passive"))
      (node (ref "RN1") (pin "2") (pinfunction "2_2") (pintype "passive"))
      (node (ref "U3") (pin "3") (pinfunction "INPUT_3") (pintype "input"))
      (node (ref "U4") (pin "3") (pinfunction "INPUT_3") (pintype "input"))
    )
    (net (code "170") (name "/VREF1") (class "Default")
      (node (ref "C38") (pin "1") (pinfunction "1_1") (pintype "passive"))
      (node (ref "U8") (pin "21") (pinfunction "VREF_21") (pintype "input"))
    )
    (net (code "171") (name "/VREF2") (class "Default")
      (node (ref "C39") (pin "1") (pinfunction "1_1") (pintype "passive"))
      (node (ref "U9") (pin "21") (pinfunction "VREF_21") (pintype "input"))
    )
    (net (code "172") (name "/VUCAP") (class "Default")
      (node (ref "C5") (pin "1") (pinfunction "1_1") (pintype "passive"))
      (node (ref "U2") (pin "27") (pinfunction "UCAP_27") (pintype "bidirectional"))
    )
    (net (code "173") (name "/XBRA") (class "Default")
      (node (ref "C62") (pin "2") (pinfunction "2_2") (pintype "passive"))
      (node (ref "RS1") (pin "1") (pinfunction "1_1") (pintype "passive"))
      (node (ref "U8") (pin "27") (pinfunction "BRA_27") (pintype "passive"))
    )
    (net (code "174") (name "/XBRB") (class "Default")
      (node (ref "C63") (pin "2") (pinfunction "2_2") (pintype "passive"))
      (node (ref "RS2") (pin "1") (pinfunction "1_1") (pintype "passive"))
      (node (ref "U8") (pin "2") (pinfunction "BRB_2") (pintype "passive"))
    )
    (net (code "175") (name "/XT1") (class "Default")
      (node (ref "C2") (pin "2") (pinfunction "2_2") (pintype "passive"))
      (node (ref "R1") (pin "1") (pinfunction "1_1") (pintype "passive"))
      (node (ref "U2") (pin "1") (pinfunction "XTAL1_1") (pintype "input"))
      (node (ref "Y1") (pin "1") (pinfunction "1_1") (pintype "passive"))
    )
    (net (code "176") (name "/XT2") (class "Default")
      (node (ref "C1") (pin "2") (pinfunction "2_2") (pintype "passive"))
      (node (ref "R1") (pin "2") (pinfunction "2_2") (pintype "passive"))
      (node (ref "U2") (pin "2") (pinfunction "(PC0)_XTAL2_2") (pintype "output"))
      (node (ref "Y1") (pin "2") (pinfunction "2_2") (pintype "passive"))
    )
    (net (code "177") (name "/XVCC") (class "Default")
      (node (ref "F1") (pin "2") (pinfunction "2_2") (pintype "passive"))
      (node (ref "USB") (pin "1") (pinfunction "VCC_1") (pintype "power_in"))
    )
    (net (code "178") (name "/YBRA") (class "Default")
      (node (ref "C60") (pin "2") (pinfunction "2_2") (pintype "passive"))
      (node (ref "RS3") (pin "1") (pinfunction "1_1") (pintype "passive"))
      (node (ref "U9") (pin "27") (pinfunction "BRA_27") (pintype "passive"))
    )
    (net (code "179") (name "/YBRB") (class "Default")
      (node (ref "C61") (pin "2") (pinfunction "2_2") (pintype "passive"))
      (node (ref "RS4") (pin "1") (pinfunction "1_1") (pintype "passive"))
      (node (ref "U9") (pin "2") (pinfunction "BRB_2") (pintype "passive"))
    )
    (net (code "180") (name "/_HUBD_N") (class "Default")
      (node (ref "RN7") (pin "4") (pinfunction "4_4") (pintype "passive"))
      (node (ref "U12") (pin "30") (pinfunction "USBDM_UP_30") (pintype "bidirectional"))
    )
    (net (code "181") (name "/_HUBD_P") (class "Default")
      (node (ref "RN7") (pin "1") (pinfunction "1_1") (pintype "passive"))
      (node (ref "U12") (pin "31") (pinfunction "USBDP_UP_31") (pintype "bidirectional"))
    )
    (net (code "182") (name "/_RXD_N") (class "Default")
      (node (ref "R38") (pin "1") (pinfunction "1_1") (pintype "passive"))
      (node (ref "U18") (pin "1") (pinfunction "B_1") (pintype "input"))
    )
    (net (code "183") (name "/_RXD_P") (class "Default")
      (node (ref "R37") (pin "1") (pinfunction "1_1") (pintype "passive"))
      (node (ref "U18") (pin "2") (pinfunction "A_2") (pintype "input"))
    )
    (net (code "184") (name "/_TXD_N") (class "Default")
      (node (ref "R41") (pin "1") (pinfunction "1_1") (pintype "passive"))
      (node (ref "U18") (pin "8") (pinfunction "Z_8") (pintype "output"))
    )
    (net (code "185") (name "/_TXD_P") (class "Default")
      (node (ref "R40") (pin "1") (pinfunction "1_1") (pintype "passive"))
      (node (ref "U18") (pin "7") (pinfunction "Y_7") (pintype "output"))
    )
    (net (code "186") (name "/nDIAG_1") (class "Default")
      (node (ref "U19") (pin "6") (pinfunction "1Y_6") (pintype "output"))
      (node (ref "U7") (pin "2") (pinfunction "REF1_2") (pintype "input"))
    )
    (net (code "187") (name "/nDIAG_2") (class "Default")
      (node (ref "U19") (pin "4") (pinfunction "2Y_4") (pintype "output"))
      (node (ref "U7") (pin "3") (pinfunction "REF2_3") (pintype "input"))
    )
    (net (code "188") (name "/nHUBRESET") (class "Default")
      (node (ref "C41") (pin "2") (pinfunction "2_2") (pintype "passive"))
      (node (ref "RN6") (pin "1") (pinfunction "1_1") (pintype "passive"))
      (node (ref "U12") (pin "26") (pinfunction "~{RESET}_26") (pintype "input"))
    )
    (net (code "189") (name "GND") (class "Default")
      (node (ref "ACTLED") (pin "02") (pinfunction "02_02") (pintype "passive"))
      (node (ref "C1") (pin "1") (pinfunction "1_1") (pintype "passive"))
      (node (ref "C10") (pin "1") (pinfunction "1_1") (pintype "passive"))
      (node (ref "C11") (pin "2") (pinfunction "2_2") (pintype "passive"))
      (node (ref "C12") (pin "2") (pinfunction "2_2") (pintype "passive"))
      (node (ref "C13") (pin "1") (pinfunction "1_1") (pintype "passive"))
      (node (ref "C14") (pin "1") (pinfunction "1_1") (pintype "passive"))
      (node (ref "C15") (pin "1") (pinfunction "1_1") (pintype "passive"))
      (node (ref "C16") (pin "1") (pinfunction "1_1") (pintype "passive"))
      (node (ref "C17") (pin "2") (pinfunction "2_2") (pintype "passive"))
      (node (ref "C18") (pin "2") (pinfunction "2_2") (pintype "passive"))
      (node (ref "C19") (pin "2") (pinfunction "2_2") (pintype "passive"))
      (node (ref "C2") (pin "1") (pinfunction "1_1") (pintype "passive"))
      (node (ref "C20") (pin "1") (pinfunction "1_1") (pintype "passive"))
      (node (ref "C21") (pin "2") (pinfunction "2_2") (pintype "passive"))
      (node (ref "C24") (pin "2") (pinfunction "2_2") (pintype "passive"))
      (node (ref "C25") (pin "2") (pinfunction "2_2") (pintype "passive"))
      (node (ref "C28") (pin "1") (pinfunction "1_1") (pintype "passive"))
      (node (ref "C29") (pin "2") (pinfunction "2_2") (pintype "passive"))
      (node (ref "C3") (pin "1") (pinfunction "1_1") (pintype "passive"))
      (node (ref "C30") (pin "2") (pinfunction "2_2") (pintype "passive"))
      (node (ref "C31") (pin "2") (pinfunction "2_2") (pintype "passive"))
      (node (ref "C32") (pin "2") (pinfunction "2_2") (pintype "passive"))
      (node (ref "C33") (pin "2") (pinfunction "2_2") (pintype "passive"))
      (node (ref "C34") (pin "2") (pinfunction "2_2") (pintype "passive"))
      (node (ref "C35") (pin "2") (pinfunction "2_2") (pintype "passive"))
      (node (ref "C36") (pin "2") (pinfunction "2_2") (pintype "passive"))
      (node (ref "C37") (pin "2") (pinfunction "2_2") (pintype "passive"))
      (node (ref "C38") (pin "2") (pinfunction "2_2") (pintype "passive"))
      (node (ref "C39") (pin "2") (pinfunction "2_2") (pintype "passive"))
      (node (ref "C4") (pin "2") (pinfunction "2_2") (pintype "passive"))
      (node (ref "C40") (pin "2") (pinfunction "2_2") (pintype "passive"))
      (node (ref "C41") (pin "1") (pinfunction "1_1") (pintype "passive"))
      (node (ref "C42") (pin "1") (pinfunction "1_1") (pintype "passive"))
      (node (ref "C43") (pin "1") (pinfunction "1_1") (pintype "passive"))
      (node (ref "C44") (pin "1") (pinfunction "1_1") (pintype "passive"))
      (node (ref "C45") (pin "2") (pinfunction "2_2") (pintype "passive"))
      (node (ref "C46") (pin "2") (pinfunction "2_2") (pintype "passive"))
      (node (ref "C47") (pin "2") (pinfunction "2_2") (pintype "passive"))
      (node (ref "C48") (pin "2") (pinfunction "2_2") (pintype "passive"))
      (node (ref "C49") (pin "2") (pinfunction "2_2") (pintype "passive"))
      (node (ref "C50") (pin "2") (pinfunction "2_2") (pintype "passive"))
      (node (ref "C51") (pin "1") (pinfunction "1_1") (pintype "passive"))
      (node (ref "C52") (pin "1") (pinfunction "1_1") (pintype "passive"))
      (node (ref "C53") (pin "1") (pinfunction "1_1") (pintype "passive"))
      (node (ref "C54") (pin "1") (pinfunction "1_1") (pintype "passive"))
      (node (ref "C55") (pin "1") (pinfunction "1_1") (pintype "passive"))
      (node (ref "C56") (pin "1") (pinfunction "1_1") (pintype "passive"))
      (node (ref "C57") (pin "1") (pinfunction "1_1") (pintype "passive"))
      (node (ref "C58") (pin "1") (pinfunction "1_1") (pintype "passive"))
      (node (ref "C59") (pin "1") (pinfunction "1_1") (pintype "passive"))
      (node (ref "C60") (pin "1") (pinfunction "1_1") (pintype "passive"))
      (node (ref "C61") (pin "1") (pinfunction "1_1") (pintype "passive"))
      (node (ref "C62") (pin "1") (pinfunction "1_1") (pintype "passive"))
      (node (ref "C63") (pin "1") (pinfunction "1_1") (pintype "passive"))
      (node (ref "C7") (pin "1") (pinfunction "1_1") (pintype "passive"))
      (node (ref "C8") (pin "2") (pinfunction "2_2") (pintype "passive"))
      (node (ref "C9") (pin "2") (pinfunction "2_2") (pintype "passive"))
      (node (ref "CD1") (pin "2") (pinfunction "2_2") (pintype "passive"))
      (node (ref "CD10") (pin "2") (pinfunction "2_2") (pintype "passive"))
      (node (ref "CD11") (pin "2") (pinfunction "2_2") (pintype "passive"))
      (node (ref "CD12") (pin "2") (pinfunction "2_2") (pintype "passive"))
      (node (ref "CD13") (pin "2") (pinfunction "2_2") (pintype "passive"))
      (node (ref "CD2") (pin "2") (pinfunction "2_2") (pintype "passive"))
      (node (ref "CD3") (pin "2") (pinfunction "2_2") (pintype "passive"))
      (node (ref "CD4") (pin "2") (pinfunction "2_2") (pintype "passive"))
      (node (ref "CD5") (pin "2") (pinfunction "2_2") (pintype "passive"))
      (node (ref "CD6") (pin "2") (pinfunction "2_2") (pintype "passive"))
      (node (ref "CD7") (pin "2") (pinfunction "2_2") (pintype "passive"))
      (node (ref "CD8") (pin "2") (pinfunction "2_2") (pintype "passive"))
      (node (ref "CD9") (pin "2") (pinfunction "2_2") (pintype "passive"))
      (node (ref "D10") (pin "NEG") (pinfunction "NEG_NEG") (pintype "passive"))
      (node (ref "D11") (pin "NEG") (pinfunction "NEG_NEG") (pintype "passive"))
      (node (ref "D12") (pin "3") (pinfunction "GND_3") (pintype "power_in"))
      (node (ref "D13") (pin "3") (pinfunction "GND_3") (pintype "power_in"))
      (node (ref "D14") (pin "NEG") (pinfunction "NEG_NEG") (pintype "passive"))
      (node (ref "D5") (pin "NEG") (pinfunction "NEG_NEG") (pintype "passive"))
      (node (ref "D7") (pin "NEG") (pinfunction "NEG_NEG") (pintype "passive"))
      (node (ref "D8") (pin "NEG") (pinfunction "NEG_NEG") (pintype "passive"))
      (node (ref "DCFAN") (pin "2") (pinfunction "2_2") (pintype "passive"))
      (node (ref "DCFAN") (pin "3") (pinfunction "3_3") (pintype "passive"))
      (node (ref "GROUND") (pin "2") (pinfunction "2_2") (pintype "passive"))
      (node (ref "ICSP16") (pin "6") (pinfunction "6_6") (pintype "passive"))
      (node (ref "ICSP2560") (pin "6") (pinfunction "6_6") (pintype "passive"))
      (node (ref "PC1") (pin "2") (pinfunction "2_2") (pintype "passive"))
      (node (ref "PC2") (pin "2") (pinfunction "2_2") (pintype "passive"))
      (node (ref "PC3") (pin "2") (pinfunction "2_2") (pintype "passive"))
      (node (ref "PC4") (pin "2") (pinfunction "2_2") (pintype "passive"))
      (node (ref "PC5") (pin "2") (pinfunction "2_2") (pintype "passive"))
      (node (ref "PC6") (pin "2") (pinfunction "2_2") (pintype "passive"))
      (node (ref "PSU") (pin "6") (pinfunction "6_6") (pintype "passive"))
      (node (ref "PSU") (pin "7") (pinfunction "7_7") (pintype "passive"))
      (node (ref "PSU") (pin "8") (pinfunction "8_8") (pintype "passive"))
      (node (ref "PiGPIO") (pin "2") (pinfunction "2_2") (pintype "passive"))
      (node (ref "PiGPIO") (pin "4") (pinfunction "4_4") (pintype "passive"))
      (node (ref "PiGPIO") (pin "6") (pinfunction "6_6") (pintype "passive"))
      (node (ref "Power") (pin "2") (pinfunction "2_2") (pintype "passive"))
      (node (ref "Power") (pin "3") (pinfunction "3_3") (pintype "passive"))
      (node (ref "R10") (pin "1") (pinfunction "1_1") (pintype "passive"))
      (node (ref "R11") (pin "2") (pinfunction "2_2") (pintype "passive"))
      (node (ref "R33") (pin "1") (pinfunction "1_1") (pintype "passive"))
      (node (ref "R6") (pin "2") (pinfunction "2_2") (pintype "passive"))
      (node (ref "R7") (pin "2") (pinfunction "2_2") (pintype "passive"))
      (node (ref "RN1") (pin "3") (pinfunction "3_3") (pintype "passive"))
      (node (ref "RN4") (pin "5") (pinfunction "5_5") (pintype "passive"))
      (node (ref "RN6") (pin "5") (pinfunction "5_5") (pintype "passive"))
      (node (ref "RN6") (pin "6") (pinfunction "6_6") (pintype "passive"))
      (node (ref "RPi") (pin "14") (pinfunction "GND_14") (pintype "power_in"))
      (node (ref "RPi") (pin "20") (pinfunction "GND_20") (pintype "power_in"))
      (node (ref "RPi") (pin "25") (pinfunction "GND_25") (pintype "power_in"))
      (node (ref "RPi") (pin "30") (pinfunction "GND_30") (pintype "power_in"))
      (node (ref "RPi") (pin "34") (pinfunction "GND_34") (pintype "power_in"))
      (node (ref "RPi") (pin "39") (pinfunction "GND_39") (pintype "power_in"))
      (node (ref "RPi") (pin "6") (pinfunction "GND_6") (pintype "power_in"))
      (node (ref "RPi") (pin "9") (pinfunction "GND_9") (pintype "power_in"))
      (node (ref "RPi") (pin "S1") (pinfunction "SHIELD_S1") (pintype "power_in"))
      (node (ref "RPi") (pin "S2") (pinfunction "SHIELD_S2") (pintype "power_in"))
      (node (ref "RPi") (pin "S3") (pinfunction "SHIELD_S3") (pintype "power_in"))
      (node (ref "RPi") (pin "S4") (pinfunction "SHIELD_S4") (pintype "power_in"))
      (node (ref "RS1") (pin "2") (pinfunction "2_2") (pintype "passive"))
      (node (ref "RS2") (pin "2") (pinfunction "2_2") (pintype "passive"))
      (node (ref "RS3") (pin "2") (pinfunction "2_2") (pintype "passive"))
      (node (ref "RS4") (pin "2") (pinfunction "2_2") (pintype "passive"))
      (node (ref "RS422 1") (pin "4") (pinfunction "4_4") (pintype "passive"))
      (node (ref "RS422 1") (pin "S1") (pinfunction "SHIELD_S1") (pintype "passive"))
      (node (ref "RS422 1") (pin "S2") (pinfunction "SHIELD_S2") (pintype "passive"))
      (node (ref "RS422 1") (pin "S3") (pinfunction "SHIELD_S3") (pintype "passive"))
      (node (ref "R_REF") (pin "2") (pinfunction "2_2") (pintype "passive"))
      (node (ref "R_REF") (pin "3") (pinfunction "3_3") (pintype "passive"))
      (node (ref "S1") (pin "3") (pinfunction "3_3") (pintype "passive"))
      (node (ref "S1") (pin "4") (pinfunction "4_4") (pintype "passive"))
      (node (ref "SCSI") (pin "14") (pinfunction "14_14") (pintype "passive"))
      (node (ref "SCSI") (pin "16") (pinfunction "16_16") (pintype "passive"))
      (node (ref "SCSI") (pin "18") (pinfunction "18_18") (pintype "passive"))
      (node (ref "SCSI") (pin "24") (pinfunction "24_24") (pintype "passive"))
      (node (ref "SCSI") (pin "7") (pinfunction "7_7") (pintype "passive"))
      (node (ref "SCSI") (pin "9") (pinfunction "9_9") (pintype "passive"))
      (node (ref "SCSI") (pin "GND@1") (pinfunction "GND_GND@1") (pintype "power_in"))
      (node (ref "SCSI") (pin "GND@2") (pinfunction "GND_GND@2") (pintype "power_in"))
      (node (ref "SST_CFG") (pin "01") (pinfunction "01_01") (pintype "passive"))
      (node (ref "SST_EXP") (pin "1") (pinfunction "GND_1") (pintype "power_in"))
      (node (ref "SST_EXP") (pin "7") (pinfunction "GND_7") (pintype "power_in"))
      (node (ref "STPDIR") (pin "01") (pinfunction "01_01") (pintype "passive"))
      (node (ref "STPDIR") (pin "08") (pinfunction "08_08") (pintype "passive"))
      (node (ref "TERM_PWR") (pin "2A") (pinfunction "COM2_2A") (pintype "passive"))
      (node (ref "U1") (pin "11") (pinfunction "GND_2_11") (pintype "passive"))
      (node (ref "U1") (pin "32") (pinfunction "GND_4_32") (pintype "passive"))
      (node (ref "U1") (pin "62") (pinfunction "GND_3_62") (pintype "passive"))
      (node (ref "U1") (pin "81") (pinfunction "GND_5_81") (pintype "passive"))
      (node (ref "U1") (pin "99") (pinfunction "GND_99") (pintype "passive"))
      (node (ref "U11") (pin "2") (pinfunction "GND_2") (pintype "power_in"))
      (node (ref "U12") (pin "11") (pinfunction "TEST_11") (pintype "passive"))
      (node (ref "U12") (pin "37") (pinfunction "VSS_37") (pintype "power_in"))
      (node (ref "U13") (pin "2") (pinfunction "GND_2") (pintype "power_in"))
      (node (ref "U14") (pin "10") (pinfunction "GND_10") (pintype "power_in"))
      (node (ref "U14") (pin "11") (pinfunction "B8_11") (pintype "bidirectional"))
      (node (ref "U14") (pin "12") (pinfunction "B7_12") (pintype "bidirectional"))
      (node (ref "U14") (pin "13") (pinfunction "B6_13") (pintype "bidirectional"))
      (node (ref "U14") (pin "14") (pinfunction "B5_14") (pintype "bidirectional"))
      (node (ref "U14") (pin "19") (pinfunction "~{G}_19") (pintype "input"))
      (node (ref "U14") (pin "6") (pinfunction "A5_6") (pintype "bidirectional"))
      (node (ref "U14") (pin "7") (pinfunction "A6_7") (pintype "bidirectional"))
      (node (ref "U14") (pin "8") (pinfunction "A7_8") (pintype "bidirectional"))
      (node (ref "U14") (pin "9") (pinfunction "A8_9") (pintype "bidirectional"))
      (node (ref "U15") (pin "10") (pinfunction "GND_10") (pintype "power_in"))
      (node (ref "U15") (pin "11") (pinfunction "B8_11") (pintype "bidirectional"))
      (node (ref "U15") (pin "12") (pinfunction "B7_12") (pintype "bidirectional"))
      (node (ref "U15") (pin "13") (pinfunction "B6_13") (pintype "bidirectional"))
      (node (ref "U15") (pin "19") (pinfunction "~{G}_19") (pintype "input"))
      (node (ref "U15") (pin "7") (pinfunction "A6_7") (pintype "bidirectional"))
      (node (ref "U15") (pin "8") (pinfunction "A7_8") (pintype "bidirectional"))
      (node (ref "U15") (pin "9") (pinfunction "A8_9") (pintype "bidirectional"))
      (node (ref "U16") (pin "10") (pinfunction "GND_10") (pintype "power_in"))
      (node (ref "U16") (pin "11") (pinfunction "B8_11") (pintype "bidirectional"))
      (node (ref "U16") (pin "12") (pinfunction "B7_12") (pintype "bidirectional"))
      (node (ref "U16") (pin "13") (pinfunction "B6_13") (pintype "bidirectional"))
      (node (ref "U16") (pin "19") (pinfunction "~{G}_19") (pintype "input"))
      (node (ref "U16") (pin "7") (pinfunction "A6_7") (pintype "bidirectional"))
      (node (ref "U16") (pin "8") (pinfunction "A7_8") (pintype "bidirectional"))
      (node (ref "U16") (pin "9") (pinfunction "A8_9") (pintype "bidirectional"))
      (node (ref "U17") (pin "10") (pinfunction "GND_10") (pintype "power_in"))
      (node (ref "U17") (pin "11") (pinfunction "B8_11") (pintype "bidirectional"))
      (node (ref "U17") (pin "12") (pinfunction "B7_12") (pintype "bidirectional"))
      (node (ref "U17") (pin "13") (pinfunction "B6_13") (pintype "bidirectional"))
      (node (ref "U17") (pin "14") (pinfunction "B5_14") (pintype "bidirectional"))
      (node (ref "U17") (pin "19") (pinfunction "~{G}_19") (pintype "input"))
      (node (ref "U17") (pin "6") (pinfunction "A5_6") (pintype "bidirectional"))
      (node (ref "U17") (pin "7") (pinfunction "A6_7") (pintype "bidirectional"))
      (node (ref "U17") (pin "8") (pinfunction "A7_8") (pintype "bidirectional"))
      (node (ref "U17") (pin "9") (pinfunction "A8_9") (pintype "bidirectional"))
      (node (ref "U18") (pin "6") (pinfunction "GND_6") (pintype "power_in"))
      (node (ref "U19") (pin "2") (pinfunction "GND_2") (pintype "power_in"))
      (node (ref "U2") (pin "3") (pinfunction "GND_3") (pintype "power_in"))
      (node (ref "U3") (pin "1") (pinfunction "ADJ/GND_1") (pintype "power_in"))
      (node (ref "U4") (pin "1") (pinfunction "ADJ/GND_1") (pintype "power_in"))
      (node (ref "U5") (pin "11") (pinfunction "GND_11") (pintype "power_in"))
      (node (ref "U6") (pin "2") (pinfunction "GND_2") (pintype "power_in"))
      (node (ref "U7") (pin "22") (pinfunction "GND@2_22") (pintype "input"))
      (node (ref "U7") (pin "6") (pinfunction "TEST_6") (pintype "input"))
      (node (ref "U7") (pin "8") (pinfunction "GND@1_8") (pintype "input"))
      (node (ref "U8") (pin "22") (pinfunction "GND_22") (pintype "power_in"))
      (node (ref "U8") (pin "29") (pinfunction "GND_29") (pintype "power_in"))
      (node (ref "U8") (pin "6") (pinfunction "GND_6") (pintype "power_in"))
      (node (ref "U9") (pin "22") (pinfunction "GND_22") (pintype "power_in"))
      (node (ref "U9") (pin "29") (pinfunction "GND_29") (pintype "power_in"))
      (node (ref "U9") (pin "6") (pinfunction "GND_6") (pintype "power_in"))
      (node (ref "USBOUT1") (pin "4") (pinfunction "GND2_4") (pintype "passive"))
      (node (ref "USBOUT1") (pin "8") (pinfunction "GND1_8") (pintype "passive"))
      (node (ref "USBOUT2") (pin "4") (pinfunction "GND2_4") (pintype "passive"))
      (node (ref "USBOUT2") (pin "8") (pinfunction "GND1_8") (pintype "passive"))
      (node (ref "USBPi") (pin "4") (pinfunction "GND_4") (pintype "passive"))
      (node (ref "USBPi") (pin "SH1") (pinfunction "SHIELD_SH1") (pintype "passive"))
      (node (ref "USBPi") (pin "SH2") (pinfunction "SHIELD_SH2") (pintype "passive"))
      (node (ref "XY_CFG") (pin "07") (pinfunction "07_07") (pintype "passive"))
      (node (ref "XY_CFG") (pin "08") (pinfunction "08_08") (pintype "passive"))
      (node (ref "Y2") (pin "2") (pinfunction "GND_2") (pintype "power_in"))
    )
    (net (code "190") (name "Net-(D7-PadPOS)") (class "Default")
      (node (ref "D7") (pin "POS") (pinfunction "POS_POS") (pintype "passive"))
      (node (ref "R8") (pin "1") (pinfunction "1_1") (pintype "passive"))
    )
    (net (code "191") (name "Net-(D8-PadPOS)") (class "Default")
      (node (ref "D8") (pin "POS") (pinfunction "POS_POS") (pintype "passive"))
      (node (ref "R9") (pin "1") (pinfunction "1_1") (pintype "passive"))
    )
    (net (code "192") (name "Net-(D9-PadC)") (class "Default")
      (node (ref "D9") (pin "C") (pinfunction "C_C") (pintype "passive"))
      (node (ref "F2") (pin "1") (pinfunction "1_1") (pintype "passive"))
    )
    (net (code "193") (name "Net-(D10-PadPOS)") (class "Default")
      (node (ref "D10") (pin "POS") (pinfunction "POS_POS") (pintype "passive"))
      (node (ref "R31") (pin "1") (pinfunction "1_1") (pintype "passive"))
    )
    (net (code "194") (name "Net-(D11-PadPOS)") (class "Default")
      (node (ref "D11") (pin "POS") (pinfunction "POS_POS") (pintype "passive"))
      (node (ref "R32") (pin "1") (pinfunction "1_1") (pintype "passive"))
    )
    (net (code "195") (name "Net-(D14-PadPOS)") (class "Default")
      (node (ref "D14") (pin "POS") (pinfunction "POS_POS") (pintype "passive"))
      (node (ref "R42") (pin "1") (pinfunction "1_1") (pintype "passive"))
    )
    (net (code "196") (name "Net-(Q2-D)") (class "Default")
      (node (ref "Q2") (pin "3") (pinfunction "D_3") (pintype "passive"))
      (node (ref "USBOUT2") (pin "5") (pinfunction "VBUS1_5") (pintype "passive"))
    )
    (net (code "197") (name "Net-(Q3-D)") (class "Default")
      (node (ref "Q3") (pin "3") (pinfunction "D_3") (pintype "passive"))
      (node (ref "USBOUT2") (pin "1") (pinfunction "VBUS2_1") (pintype "passive"))
    )
    (net (code "198") (name "Net-(Q4-D)") (class "Default")
      (node (ref "Q4") (pin "3") (pinfunction "D_3") (pintype "passive"))
      (node (ref "USBOUT1") (pin "5") (pinfunction "VBUS1_5") (pintype "passive"))
    )
    (net (code "199") (name "Net-(Q5-D)") (class "Default")
      (node (ref "Q5") (pin "3") (pinfunction "D_3") (pintype "passive"))
      (node (ref "USBOUT1") (pin "1") (pinfunction "VBUS2_1") (pintype "passive"))
    )
    (net (code "200") (name "Net-(RX_AT-A2)") (class "Default")
      (node (ref "R35") (pin "1") (pinfunction "1_1") (pintype "passive"))
      (node (ref "RX_AT") (pin "2") (pinfunction "A2_2") (pintype "passive"))
    )
    (net (code "201") (name "Net-(TX_AT-A2)") (class "Default")
      (node (ref "R34") (pin "1") (pinfunction "1_1") (pintype "passive"))
      (node (ref "TX_AT") (pin "2") (pinfunction "A2_2") (pintype "passive"))
    )
    (net (code "202") (name "Net-(U1-(OC2B)_PH6)") (class "Default")
      (node (ref "PH") (pin "07") (pinfunction "07_07") (pintype "passive"))
      (node (ref "U1") (pin "18") (pinfunction "(OC2B)_PH6_18") (pintype "bidirectional"))
    )
    (net (code "203") (name "Net-(U1-(OC4A)_PH3)") (class "Default")
      (node (ref "PH") (pin "04") (pinfunction "04_04") (pintype "passive"))
      (node (ref "U1") (pin "15") (pinfunction "(OC4A)_PH3_15") (pintype "bidirectional"))
    )
    (net (code "204") (name "Net-(U1-(OC4B)_PH4)") (class "Default")
      (node (ref "PH") (pin "05") (pinfunction "05_05") (pintype "passive"))
      (node (ref "U1") (pin "16") (pinfunction "(OC4B)_PH4_16") (pintype "bidirectional"))
    )
    (net (code "205") (name "Net-(U1-(OC4C)_PH5)") (class "Default")
      (node (ref "PH") (pin "06") (pinfunction "06_06") (pintype "passive"))
      (node (ref "U1") (pin "17") (pinfunction "(OC4C)_PH5_17") (pintype "bidirectional"))
    )
    (net (code "206") (name "Net-(U1-(T4)_PH7)") (class "Default")
      (node (ref "PH") (pin "08") (pinfunction "08_08") (pintype "passive"))
      (node (ref "U1") (pin "27") (pinfunction "(T4)_PH7_27") (pintype "bidirectional"))
    )
    (net (code "207") (name "Net-(U1-(XCK2)_PH2)") (class "Default")
      (node (ref "PH") (pin "03") (pinfunction "03_03") (pintype "passive"))
      (node (ref "U1") (pin "14") (pinfunction "(XCK2)_PH2_14") (pintype "bidirectional"))
    )
    (net (code "208") (name "Net-(U1-PC0_(A8))") (class "Default")
      (node (ref "PC") (pin "01") (pinfunction "01_01") (pintype "passive"))
      (node (ref "U1") (pin "53") (pinfunction "PC0_(A8)_53") (pintype "bidirectional"))
    )
    (net (code "209") (name "Net-(U1-PC1_(A9))") (class "Default")
      (node (ref "PC") (pin "02") (pinfunction "02_02") (pintype "passive"))
      (node (ref "U1") (pin "54") (pinfunction "PC1_(A9)_54") (pintype "bidirectional"))
    )
    (net (code "210") (name "Net-(U1-PC2_(A10))") (class "Default")
      (node (ref "PC") (pin "03") (pinfunction "03_03") (pintype "passive"))
      (node (ref "U1") (pin "55") (pinfunction "PC2_(A10)_55") (pintype "bidirectional"))
    )
    (net (code "211") (name "Net-(U1-PC3_(A11))") (class "Default")
      (node (ref "PC") (pin "04") (pinfunction "04_04") (pintype "passive"))
      (node (ref "U1") (pin "56") (pinfunction "PC3_(A11)_56") (pintype "bidirectional"))
    )
    (net (code "212") (name "Net-(U1-PC4_(A12))") (class "Default")
      (node (ref "PC") (pin "05") (pinfunction "05_05") (pintype "passive"))
      (node (ref "U1") (pin "57") (pinfunction "PC4_(A12)_57") (pintype "bidirectional"))
    )
    (net (code "213") (name "Net-(U1-PC5_(A13))") (class "Default")
      (node (ref "PC") (pin "06") (pinfunction "06_06") (pintype "passive"))
      (node (ref "U1") (pin "58") (pinfunction "PC5_(A13)_58") (pintype "bidirectional"))
    )
    (net (code "214") (name "Net-(U1-PC6_(A14))") (class "Default")
      (node (ref "PC") (pin "07") (pinfunction "07_07") (pintype "passive"))
      (node (ref "U1") (pin "59") (pinfunction "PC6_(A14)_59") (pintype "bidirectional"))
    )
    (net (code "215") (name "Net-(U1-PC7_(A15))") (class "Default")
      (node (ref "PC") (pin "08") (pinfunction "08_08") (pintype "passive"))
      (node (ref "U1") (pin "60") (pinfunction "PC7_(A15)_60") (pintype "bidirectional"))
    )
    (net (code "216") (name "Net-(U1-PF0_(ADC0))") (class "Default")
      (node (ref "PF") (pin "01") (pinfunction "01_01") (pintype "passive"))
      (node (ref "U1") (pin "97") (pinfunction "PF0_(ADC0)_97") (pintype "bidirectional"))
    )
    (net (code "217") (name "Net-(U1-PF1_(ADC1))") (class "Default")
      (node (ref "PF") (pin "02") (pinfunction "02_02") (pintype "passive"))
      (node (ref "U1") (pin "96") (pinfunction "PF1_(ADC1)_96") (pintype "bidirectional"))
    )
    (net (code "218") (name "Net-(U1-PF2_(ADC2))") (class "Default")
      (node (ref "PF") (pin "03") (pinfunction "03_03") (pintype "passive"))
      (node (ref "U1") (pin "95") (pinfunction "PF2_(ADC2)_95") (pintype "bidirectional"))
    )
    (net (code "219") (name "Net-(U1-PF3_(ADC3))") (class "Default")
      (node (ref "PF") (pin "04") (pinfunction "04_04") (pintype "passive"))
      (node (ref "U1") (pin "94") (pinfunction "PF3_(ADC3)_94") (pintype "bidirectional"))
    )
    (net (code "220") (name "Net-(U1-PF4_(ADC4{slash}TCK))") (class "Default")
      (node (ref "PF") (pin "05") (pinfunction "05_05") (pintype "passive"))
      (node (ref "U1") (pin "93") (pinfunction "PF4_(ADC4/TCK)_93") (pintype "bidirectional"))
    )
    (net (code "221") (name "Net-(U1-PF5_(ADC5{slash}TMS))") (class "Default")
      (node (ref "PF") (pin "06") (pinfunction "06_06") (pintype "passive"))
      (node (ref "U1") (pin "92") (pinfunction "PF5_(ADC5/TMS)_92") (pintype "bidirectional"))
    )
    (net (code "222") (name "Net-(U1-PF6_(ADC6{slash}TDO))") (class "Default")
      (node (ref "PF") (pin "07") (pinfunction "07_07") (pintype "passive"))
      (node (ref "U1") (pin "91") (pinfunction "PF6_(ADC6/TDO)_91") (pintype "bidirectional"))
    )
    (net (code "223") (name "Net-(U1-PF7_(ADC7{slash}TDI))") (class "Default")
      (node (ref "PF") (pin "08") (pinfunction "08_08") (pintype "passive"))
      (node (ref "U1") (pin "90") (pinfunction "PF7_(ADC7/TDI)_90") (pintype "bidirectional"))
    )
    (net (code "224") (name "Net-(U6-BYPASS)") (class "Default")
      (node (ref "C10") (pin "2") (pinfunction "2_2") (pintype "passive"))
      (node (ref "U6") (pin "4") (pinfunction "BYPASS_4") (pintype "input"))
    )
    (net (code "225") (name "Net-(U7-V33)") (class "Default")
      (node (ref "C19") (pin "1") (pinfunction "1_1") (pintype "passive"))
      (node (ref "U7") (pin "21") (pinfunction "V33_21") (pintype "input"))
    )
    (net (code "226") (name "Net-(U8-CPI)") (class "Default")
      (node (ref "C22") (pin "2") (pinfunction "2_2") (pintype "passive"))
      (node (ref "U8") (pin "8") (pinfunction "CPI_8") (pintype "passive"))
    )
    (net (code "227") (name "Net-(U8-CPO)") (class "Default")
      (node (ref "C22") (pin "1") (pinfunction "1_1") (pintype "passive"))
      (node (ref "U8") (pin "7") (pinfunction "CPO_7") (pintype "passive"))
    )
    (net (code "228") (name "Net-(U8-STDBY)") (class "Default")
      (node (ref "R6") (pin "1") (pinfunction "1_1") (pintype "passive"))
      (node (ref "U8") (pin "24") (pinfunction "STDBY_24") (pintype "input"))
    )
    (net (code "229") (name "Net-(U8-VCP)") (class "Default")
      (node (ref "C26") (pin "2") (pinfunction "2_2") (pintype "passive"))
      (node (ref "U8") (pin "9") (pinfunction "VCP_9") (pintype "passive"))
    )
    (net (code "230") (name "Net-(U9-CPI)") (class "Default")
      (node (ref "C23") (pin "2") (pinfunction "2_2") (pintype "passive"))
      (node (ref "U9") (pin "8") (pinfunction "CPI_8") (pintype "passive"))
    )
    (net (code "231") (name "Net-(U9-CPO)") (class "Default")
      (node (ref "C23") (pin "1") (pinfunction "1_1") (pintype "passive"))
      (node (ref "U9") (pin "7") (pinfunction "CPO_7") (pintype "passive"))
    )
    (net (code "232") (name "Net-(U9-STDBY)") (class "Default")
      (node (ref "R7") (pin "1") (pinfunction "1_1") (pintype "passive"))
      (node (ref "U9") (pin "24") (pinfunction "STDBY_24") (pintype "input"))
    )
    (net (code "233") (name "Net-(U9-VCP)") (class "Default")
      (node (ref "C27") (pin "2") (pinfunction "2_2") (pintype "passive"))
      (node (ref "U9") (pin "9") (pinfunction "VCP_9") (pintype "passive"))
    )
    (net (code "234") (name "Net-(U12-CRFILT)") (class "Default")
      (node (ref "C43") (pin "2") (pinfunction "2_2") (pintype "passive"))
      (node (ref "U12") (pin "14") (pinfunction "CRFILT_14") (pintype "passive"))
    )
    (net (code "235") (name "Net-(U12-PLLFILT)") (class "Default")
      (node (ref "C44") (pin "2") (pinfunction "2_2") (pintype "passive"))
      (node (ref "U12") (pin "34") (pinfunction "PLLFILT_34") (pintype "passive"))
    )
    (net (code "236") (name "Net-(U12-RBIAS)") (class "Default")
      (node (ref "R10") (pin "2") (pinfunction "2_2") (pintype "passive"))
      (node (ref "U12") (pin "35") (pinfunction "RBIAS_35") (pintype "passive"))
    )
    (net (code "237") (name "Net-(U12-SUSP_IND{slash}LOCAL_PWR{slash}NON_REM0)") (class "Default")
      (node (ref "R11") (pin "1") (pinfunction "1_1") (pintype "passive"))
      (node (ref "U12") (pin "28") (pinfunction "SUSP_IND/LOCAL_PWR/NON_REM0_28") (pintype "bidirectional"))
    )
    (net (code "238") (name "Net-(U12-XTALIN{slash}CLKIN)") (class "Default")
      (node (ref "C45") (pin "1") (pinfunction "1_1") (pintype "passive"))
      (node (ref "R12") (pin "2") (pinfunction "2_2") (pintype "passive"))
      (node (ref "U12") (pin "33") (pinfunction "XTALIN/CLKIN_33") (pintype "input"))
      (node (ref "Y3") (pin "2") (pinfunction "2_2") (pintype "passive"))
    )
    (net (code "239") (name "Net-(U12-XTALOUT)") (class "Default")
      (node (ref "C46") (pin "1") (pinfunction "1_1") (pintype "passive"))
      (node (ref "R12") (pin "1") (pinfunction "1_1") (pintype "passive"))
      (node (ref "U12") (pin "32") (pinfunction "XTALOUT_32") (pintype "output"))
      (node (ref "Y3") (pin "1") (pinfunction "1_1") (pintype "passive"))
    )
    (net (code "240") (name "unconnected-(RN2-Pad2)") (class "Default")
      (node (ref "RN2") (pin "2") (pinfunction "2_2") (pintype "passive"))
    )
    (net (code "241") (name "unconnected-(RN2-Pad3)") (class "Default")
      (node (ref "RN2") (pin "3") (pinfunction "3_3") (pintype "passive"))
    )
    (net (code "242") (name "unconnected-(RN2-Pad6)") (class "Default")
      (node (ref "RN2") (pin "6") (pinfunction "6_6") (pintype "passive"))
    )
    (net (code "243") (name "unconnected-(RN2-Pad7)") (class "Default")
      (node (ref "RN2") (pin "7") (pinfunction "7_7") (pintype "passive"))
    )
    (net (code "244") (name "unconnected-(RN4-Pad2)") (class "Default")
      (node (ref "RN4") (pin "2") (pinfunction "2_2") (pintype "passive"))
    )
    (net (code "245") (name "unconnected-(RN4-Pad3)") (class "Default")
      (node (ref "RN4") (pin "3") (pinfunction "3_3") (pintype "passive"))
    )
    (net (code "246") (name "unconnected-(RN4-Pad6)") (class "Default")
      (node (ref "RN4") (pin "6") (pinfunction "6_6") (pintype "passive"))
    )
    (net (code "247") (name "unconnected-(RN4-Pad7)") (class "Default")
      (node (ref "RN4") (pin "7") (pinfunction "7_7") (pintype "passive"))
    )
    (net (code "248") (name "unconnected-(RN7-Pad2)") (class "Default")
      (node (ref "RN7") (pin "2") (pinfunction "2_2") (pintype "passive"))
    )
    (net (code "249") (name "unconnected-(RN7-Pad3)") (class "Default")
      (node (ref "RN7") (pin "3") (pinfunction "3_3") (pintype "passive"))
    )
    (net (code "250") (name "unconnected-(RN7-Pad6)") (class "Default")
      (node (ref "RN7") (pin "6") (pinfunction "6_6") (pintype "passive"))
    )
    (net (code "251") (name "unconnected-(RN7-Pad7)") (class "Default")
      (node (ref "RN7") (pin "7") (pinfunction "7_7") (pintype "passive"))
    )
    (net (code "252") (name "unconnected-(RPi-TR00-Pad42)") (class "Default")
      (node (ref "RPi") (pin "42") (pinfunction "TR00_42") (pintype "bidirectional+no_connect"))
    )
    (net (code "253") (name "unconnected-(RPi-TR01-Pad41)") (class "Default")
      (node (ref "RPi") (pin "41") (pinfunction "TR01_41") (pintype "bidirectional+no_connect"))
    )
    (net (code "254") (name "unconnected-(RPi-TR02-Pad44)") (class "Default")
      (node (ref "RPi") (pin "44") (pinfunction "TR02_44") (pintype "bidirectional+no_connect"))
    )
    (net (code "255") (name "unconnected-(RPi-TR03-Pad43)") (class "Default")
      (node (ref "RPi") (pin "43") (pinfunction "TR03_43") (pintype "bidirectional+no_connect"))
    )
    (net (code "256") (name "unconnected-(RS422 1-Pad1)") (class "Default")
      (node (ref "RS422 1") (pin "1") (pinfunction "1_1") (pintype "passive+no_connect"))
    )
    (net (code "257") (name "unconnected-(RS422 1-Pad2)") (class "Default")
      (node (ref "RS422 1") (pin "2") (pinfunction "2_2") (pintype "passive+no_connect"))
    )
    (net (code "258") (name "unconnected-(RS422 1-Pad7)") (class "Default")
      (node (ref "RS422 1") (pin "7") (pinfunction "7_7") (pintype "passive+no_connect"))
    )
    (net (code "259") (name "unconnected-(U1-(ICP1)_PD4-Pad47)") (class "Default")
      (node (ref "U1") (pin "47") (pinfunction "(ICP1)_PD4_47") (pintype "bidirectional"))
    )
    (net (code "260") (name "unconnected-(U1-(OC0A{slash}OC1C{slash}PCINT7)_PB7-Pad26)") (class "Default")
      (node (ref "U1") (pin "26") (pinfunction "(OC0A/OC1C/PCINT7)_PB7_26") (pintype "bidirectional"))
    )
    (net (code "261") (name "unconnected-(U1-(OC0B)_PG5-Pad1)") (class "Default")
      (node (ref "U1") (pin "1") (pinfunction "(OC0B)_PG5_1") (pintype "bidirectional"))
    )
    (net (code "262") (name "unconnected-(U1-(OC1A{slash}PCINT5)_PB5-Pad24)") (class "Default")
      (node (ref "U1") (pin "24") (pinfunction "(OC1A/PCINT5)_PB5_24") (pintype "bidirectional"))
    )
    (net (code "263") (name "unconnected-(U1-(OC1B{slash}PCINT6)_PB6-Pad25)") (class "Default")
      (node (ref "U1") (pin "25") (pinfunction "(OC1B/PCINT6)_PB6_25") (pintype "bidirectional"))
    )
    (net (code "264") (name "unconnected-(U1-(OC2A{slash}PCINT4)_PB4-Pad23)") (class "Default")
      (node (ref "U1") (pin "23") (pinfunction "(OC2A/PCINT4)_PB4_23") (pintype "bidirectional"))
    )
    (net (code "265") (name "unconnected-(U1-(OC3A{slash}AIN1)_PE3-Pad5)") (class "Default")
      (node (ref "U1") (pin "5") (pinfunction "(OC3A/AIN1)_PE3_5") (pintype "bidirectional"))
    )
    (net (code "266") (name "unconnected-(U1-(OC3B{slash}INT4)_PE4-Pad6)") (class "Default")
      (node (ref "U1") (pin "6") (pinfunction "(OC3B/INT4)_PE4_6") (pintype "bidirectional"))
    )
    (net (code "267") (name "unconnected-(U1-(OC3C{slash}INT5)_PE5-Pad7)") (class "Default")
      (node (ref "U1") (pin "7") (pinfunction "(OC3C/INT5)_PE5_7") (pintype "bidirectional"))
    )
    (net (code "268") (name "unconnected-(U1-(T0)_PD7-Pad50)") (class "Default")
      (node (ref "U1") (pin "50") (pinfunction "(T0)_PD7_50") (pintype "bidirectional"))
    )
    (net (code "269") (name "unconnected-(U1-(T1)_PD6-Pad49)") (class "Default")
      (node (ref "U1") (pin "49") (pinfunction "(T1)_PD6_49") (pintype "bidirectional"))
    )
    (net (code "270") (name "unconnected-(U1-(T3{slash}INT6)_PE6-Pad8)") (class "Default")
      (node (ref "U1") (pin "8") (pinfunction "(T3/INT6)_PE6_8") (pintype "bidirectional"))
    )
    (net (code "271") (name "unconnected-(U1-(TOSC1)_PG4-Pad29)") (class "Default")
      (node (ref "U1") (pin "29") (pinfunction "(TOSC1)_PG4_29") (pintype "bidirectional"))
    )
    (net (code "272") (name "unconnected-(U1-(TOSC2)_PG3-Pad28)") (class "Default")
      (node (ref "U1") (pin "28") (pinfunction "(TOSC2)_PG3_28") (pintype "bidirectional"))
    )
    (net (code "273") (name "unconnected-(U1-(XCK0{slash}AIN0)_PE2-Pad4)") (class "Default")
      (node (ref "U1") (pin "4") (pinfunction "(XCK0/AIN0)_PE2_4") (pintype "bidirectional"))
    )
    (net (code "274") (name "unconnected-(U1-(XCK1)_PD5-Pad48)") (class "Default")
      (node (ref "U1") (pin "48") (pinfunction "(XCK1)_PD5_48") (pintype "bidirectional"))
    )
    (net (code "275") (name "unconnected-(U1-PA0_(AD0)-Pad78)") (class "Default")
      (node (ref "U1") (pin "78") (pinfunction "PA0_(AD0)_78") (pintype "bidirectional"))
    )
    (net (code "276") (name "unconnected-(U1-PA1_(AD1)-Pad77)") (class "Default")
      (node (ref "U1") (pin "77") (pinfunction "PA1_(AD1)_77") (pintype "bidirectional"))
    )
    (net (code "277") (name "unconnected-(U1-PA2_(AD2)-Pad76)") (class "Default")
      (node (ref "U1") (pin "76") (pinfunction "PA2_(AD2)_76") (pintype "bidirectional"))
    )
    (net (code "278") (name "unconnected-(U1-PA3_(AD3)-Pad75)") (class "Default")
      (node (ref "U1") (pin "75") (pinfunction "PA3_(AD3)_75") (pintype "bidirectional"))
    )
    (net (code "279") (name "unconnected-(U1-PA4_(AD4)-Pad74)") (class "Default")
      (node (ref "U1") (pin "74") (pinfunction "PA4_(AD4)_74") (pintype "bidirectional"))
    )
    (net (code "280") (name "unconnected-(U1-PA5_(AD5)-Pad73)") (class "Default")
      (node (ref "U1") (pin "73") (pinfunction "PA5_(AD5)_73") (pintype "bidirectional"))
    )
    (net (code "281") (name "unconnected-(U1-PA6_(AD6)-Pad72)") (class "Default")
      (node (ref "U1") (pin "72") (pinfunction "PA6_(AD6)_72") (pintype "bidirectional"))
    )
    (net (code "282") (name "unconnected-(U1-PA7_(AD7)-Pad71)") (class "Default")
      (node (ref "U1") (pin "71") (pinfunction "PA7_(AD7)_71") (pintype "bidirectional"))
    )
    (net (code "283") (name "unconnected-(U1-PG0_(~WR)-Pad51)") (class "Default")
      (node (ref "U1") (pin "51") (pinfunction "PG0_(~WR)_51") (pintype "bidirectional"))
    )
    (net (code "284") (name "unconnected-(U1-PG1_(~RD)-Pad52)") (class "Default")
      (node (ref "U1") (pin "52") (pinfunction "PG1_(~RD)_52") (pintype "bidirectional"))
    )
    (net (code "285") (name "unconnected-(U1-PG2_(ALE)-Pad70)") (class "Default")
      (node (ref "U1") (pin "70") (pinfunction "PG2_(ALE)_70") (pintype "bidirectional"))
    )
    (net (code "286") (name "unconnected-(U1-PJ2_(XCK3{slash}PCINT11)-Pad65)") (class "Default")
      (node (ref "U1") (pin "65") (pinfunction "PJ2_(XCK3/PCINT11)_65") (pintype "bidirectional"))
    )
    (net (code "287") (name "unconnected-(U1-PJ3_(PCINT12)-Pad66)") (class "Default")
      (node (ref "U1") (pin "66") (pinfunction "PJ3_(PCINT12)_66") (pintype "bidirectional"))
    )
    (net (code "288") (name "unconnected-(U1-PJ4_(PCINT13)-Pad67)") (class "Default")
      (node (ref "U1") (pin "67") (pinfunction "PJ4_(PCINT13)_67") (pintype "bidirectional"))
    )
    (net (code "289") (name "unconnected-(U1-PJ5_(PCINT14)-Pad68)") (class "Default")
      (node (ref "U1") (pin "68") (pinfunction "PJ5_(PCINT14)_68") (pintype "bidirectional"))
    )
    (net (code "290") (name "unconnected-(U1-PJ6_(PCINT15)-Pad69)") (class "Default")
      (node (ref "U1") (pin "69") (pinfunction "PJ6_(PCINT15)_69") (pintype "bidirectional"))
    )
    (net (code "291") (name "unconnected-(U1-PJ7-Pad79)") (class "Default")
      (node (ref "U1") (pin "79") (pinfunction "PJ7_79") (pintype "bidirectional"))
    )
    (net (code "292") (name "unconnected-(U1-PK0_(ADC8{slash}PCINT16)-Pad89)") (class "Default")
      (node (ref "U1") (pin "89") (pinfunction "PK0_(ADC8/PCINT16)_89") (pintype "bidirectional"))
    )
    (net (code "293") (name "unconnected-(U1-PK1_(ADC9{slash}PCINT17)-Pad88)") (class "Default")
      (node (ref "U1") (pin "88") (pinfunction "PK1_(ADC9/PCINT17)_88") (pintype "bidirectional"))
    )
    (net (code "294") (name "unconnected-(U1-PK2_(ADC10{slash}PCINT18)-Pad87)") (class "Default")
      (node (ref "U1") (pin "87") (pinfunction "PK2_(ADC10/PCINT18)_87") (pintype "bidirectional"))
    )
    (net (code "295") (name "unconnected-(U1-PK3_(ADC11{slash}PCINT19)-Pad86)") (class "Default")
      (node (ref "U1") (pin "86") (pinfunction "PK3_(ADC11/PCINT19)_86") (pintype "bidirectional"))
    )
    (net (code "296") (name "unconnected-(U1-PK4_(ADC12{slash}PCINT20)-Pad85)") (class "Default")
      (node (ref "U1") (pin "85") (pinfunction "PK4_(ADC12/PCINT20)_85") (pintype "bidirectional"))
    )
    (net (code "297") (name "unconnected-(U1-PK5_(ADC13{slash}PCINT21)-Pad84)") (class "Default")
      (node (ref "U1") (pin "84") (pinfunction "PK5_(ADC13/PCINT21)_84") (pintype "bidirectional"))
    )
    (net (code "298") (name "unconnected-(U1-PK6_(ADC14{slash}PCINT22)-Pad83)") (class "Default")
      (node (ref "U1") (pin "83") (pinfunction "PK6_(ADC14/PCINT22)_83") (pintype "bidirectional"))
    )
    (net (code "299") (name "unconnected-(U1-PK7_(ADC15{slash}PCINT23)-Pad82)") (class "Default")
      (node (ref "U1") (pin "82") (pinfunction "PK7_(ADC15/PCINT23)_82") (pintype "bidirectional"))
    )
    (net (code "300") (name "unconnected-(U2-(AIN0_{slash}_INT1)_PD1-Pad7)") (class "Default")
      (node (ref "U2") (pin "7") (pinfunction "(AIN0_/_INT1)_PD1_7") (pintype "input+no_connect"))
    )
    (net (code "301") (name "unconnected-(U2-(OC.0B_{slash}_INT0)_PD0-Pad6)") (class "Default")
      (node (ref "U2") (pin "6") (pinfunction "(OC.0B_/_INT0)_PD0_6") (pintype "input+no_connect"))
    )
    (net (code "302") (name "unconnected-(U2-(PCINT11_{slash}AIN2_)_PC2-Pad5)") (class "Default")
      (node (ref "U2") (pin "5") (pinfunction "(PCINT11_/AIN2_)_PC2_5") (pintype "input+no_connect"))
    )
    (net (code "303") (name "unconnected-(U2-(RTS_{slash}_AIN5_{slash}_INT6)_PD6-Pad12)") (class "Default")
      (node (ref "U2") (pin "12") (pinfunction "(RTS_/_AIN5_/_INT6)_PD6_12") (pintype "input+no_connect"))
    )
    (net (code "304") (name "unconnected-(U2-(~SS_{slash}_PCINT0)_PB0-Pad14)") (class "Default")
      (node (ref "U2") (pin "14") (pinfunction "(~SS_/_PCINT0)_PB0_14") (pintype "input+no_connect"))
    )
    (net (code "305") (name "unconnected-(U2-PB4_(T1_{slash}_PCINT4)-Pad18)") (class "Default")
      (node (ref "U2") (pin "18") (pinfunction "PB4_(T1_/_PCINT4)_18") (pintype "input+no_connect"))
    )
    (net (code "306") (name "unconnected-(U2-PB5_(PCINT5)-Pad19)") (class "Default")
      (node (ref "U2") (pin "19") (pinfunction "PB5_(PCINT5)_19") (pintype "input+no_connect"))
    )
    (net (code "307") (name "unconnected-(U2-PB6_(PCINT6)-Pad20)") (class "Default")
      (node (ref "U2") (pin "20") (pinfunction "PB6_(PCINT6)_20") (pintype "input+no_connect"))
    )
    (net (code "308") (name "unconnected-(U2-PB7_(PCINT7_{slash}_OC.0A_{slash}_OC.1C)-Pad21)") (class "Default")
      (node (ref "U2") (pin "21") (pinfunction "PB7_(PCINT7_/_OC.0A_/_OC.1C)_21") (pintype "input+no_connect"))
    )
    (net (code "309") (name "unconnected-(U2-PC4_(PCINT10)-Pad26)") (class "Default")
      (node (ref "U2") (pin "26") (pinfunction "PC4_(PCINT10)_26") (pintype "input+no_connect"))
    )
    (net (code "310") (name "unconnected-(U2-PC5_(_PCINT9{slash}_OC.1B)-Pad25)") (class "Default")
      (node (ref "U2") (pin "25") (pinfunction "PC5_(_PCINT9/_OC.1B)_25") (pintype "input+no_connect"))
    )
    (net (code "311") (name "unconnected-(U2-PC6_(OC.1A_{slash}_PCINT8)-Pad23)") (class "Default")
      (node (ref "U2") (pin "23") (pinfunction "PC6_(OC.1A_/_PCINT8)_23") (pintype "input+no_connect"))
    )
    (net (code "312") (name "unconnected-(U2-PC7_(INT4_{slash}_ICP1_{slash}_CLKO)-Pad22)") (class "Default")
      (node (ref "U2") (pin "22") (pinfunction "PC7_(INT4_/_ICP1_/_CLKO)_22") (pintype "input+no_connect"))
    )
    (net (code "313") (name "unconnected-(U3-OUTPUT_2-Pad2)") (class "Default")
      (node (ref "U3") (pin "2") (pinfunction "OUTPUT_2_2") (pintype "output+no_connect"))
    )
    (net (code "314") (name "unconnected-(U4-OUTPUT_2-Pad2)") (class "Default")
      (node (ref "U4") (pin "2") (pinfunction "OUTPUT_2_2") (pintype "output+no_connect"))
    )
    (net (code "315") (name "unconnected-(U7-SDOZ_C-Pad12)") (class "Default")
      (node (ref "U7") (pin "12") (pinfunction "SDOZ_C_12") (pintype "input+no_connect"))
    )
    (net (code "316") (name "unconnected-(U8-NC-Pad13)") (class "Default")
      (node (ref "U8") (pin "13") (pinfunction "NC_13") (pintype "passive+no_connect"))
    )
    (net (code "317") (name "unconnected-(U9-NC-Pad13)") (class "Default")
      (node (ref "U9") (pin "13") (pinfunction "NC_13") (pintype "passive+no_connect"))
    )
    (net (code "318") (name "unconnected-(U12-OCS_N1-Pad13)") (class "Default")
      (node (ref "U12") (pin "13") (pinfunction "OCS_N1_13") (pintype "input+no_connect"))
    )
    (net (code "319") (name "unconnected-(U12-OCS_N3-Pad19)") (class "Default")
      (node (ref "U12") (pin "19") (pinfunction "OCS_N3_19") (pintype "input+no_connect"))
    )
    (net (code "320") (name "unconnected-(U12-OCS_N4-Pad21)") (class "Default")
      (node (ref "U12") (pin "21") (pinfunction "OCS_N4_21") (pintype "input+no_connect"))
    )
    (net (code "321") (name "unconnected-(U12-OSC_N2-Pad17)") (class "Default")
      (node (ref "U12") (pin "17") (pinfunction "OSC_N2_17") (pintype "input+no_connect"))
    )
    (net (code "322") (name "unconnected-(U12-SCL{slash}SMBCLK{slash}CFG_SEL0-Pad24)") (class "Default")
      (node (ref "U12") (pin "24") (pinfunction "SCL/SMBCLK/CFG_SEL0_24") (pintype "bidirectional+no_connect"))
    )
    (net (code "323") (name "unconnected-(U12-SDA{slash}SMBDATA{slash}NON_REM1-Pad22)") (class "Default")
      (node (ref "U12") (pin "22") (pinfunction "SDA/SMBDATA/NON_REM1_22") (pintype "bidirectional+no_connect"))
    )
    (net (code "324") (name "unconnected-(USBOUT1-SHIELD-PadP1)") (class "Default")
      (node (ref "USBOUT1") (pin "P1") (pinfunction "SHIELD_P1") (pintype "passive"))
    )
    (net (code "325") (name "unconnected-(USBOUT1-SHIELD-PadP2)") (class "Default")
      (node (ref "USBOUT1") (pin "P2") (pinfunction "SHIELD_P2") (pintype "passive"))
    )
    (net (code "326") (name "unconnected-(USBOUT1-SHIELD-PadP3)") (class "Default")
      (node (ref "USBOUT1") (pin "P3") (pinfunction "SHIELD_P3") (pintype "passive"))
    )
    (net (code "327") (name "unconnected-(USBOUT1-SHIELD-PadP4)") (class "Default")
      (node (ref "USBOUT1") (pin "P4") (pinfunction "SHIELD_P4") (pintype "passive"))
    )
    (net (code "328") (name "unconnected-(USBOUT2-SHIELD-PadP1)") (class "Default")
      (node (ref "USBOUT2") (pin "P1") (pinfunction "SHIELD_P1") (pintype "passive"))
    )
    (net (code "329") (name "unconnected-(USBOUT2-SHIELD-PadP2)") (class "Default")
      (node (ref "USBOUT2") (pin "P2") (pinfunction "SHIELD_P2") (pintype "passive"))
    )
    (net (code "330") (name "unconnected-(USBOUT2-SHIELD-PadP3)") (class "Default")
      (node (ref "USBOUT2") (pin "P3") (pinfunction "SHIELD_P3") (pintype "passive"))
    )
    (net (code "331") (name "unconnected-(USBOUT2-SHIELD-PadP4)") (class "Default")
      (node (ref "USBOUT2") (pin "P4") (pinfunction "SHIELD_P4") (pintype "passive"))
    )
  )
)
